# qo-100-gpsdo.net
KiCad netlist of a schematic drawn in EAGLE
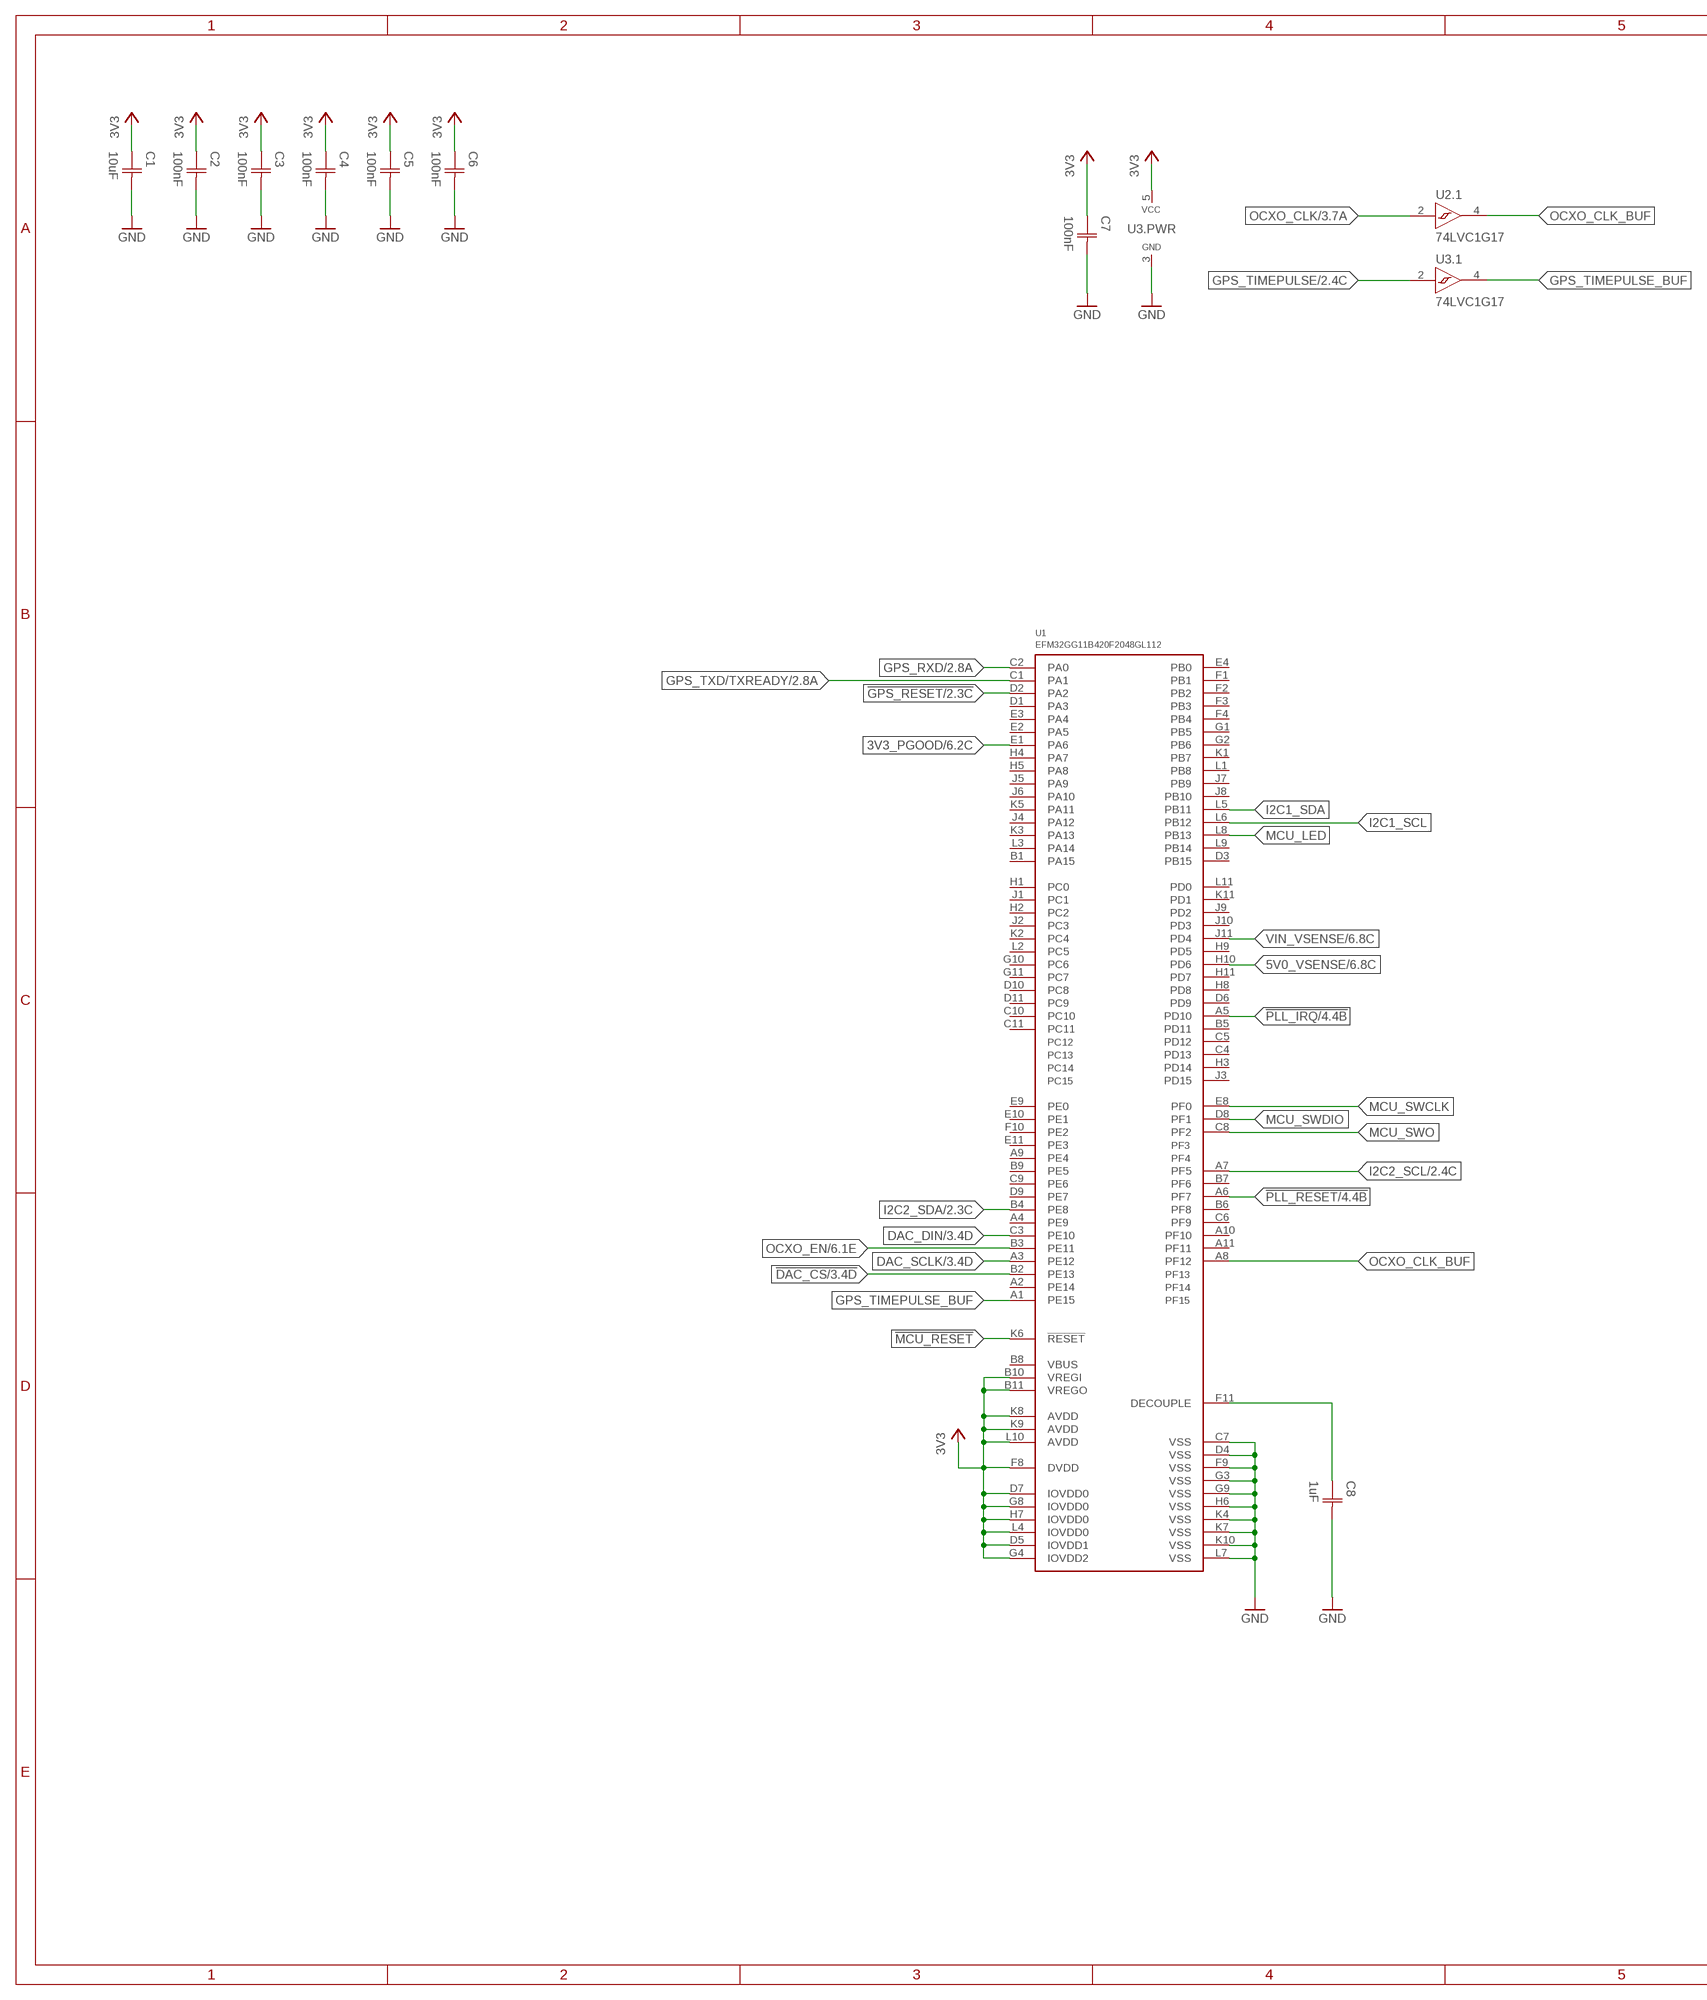
[diagram p0: schematic, sheet 1, part 1 of 2]
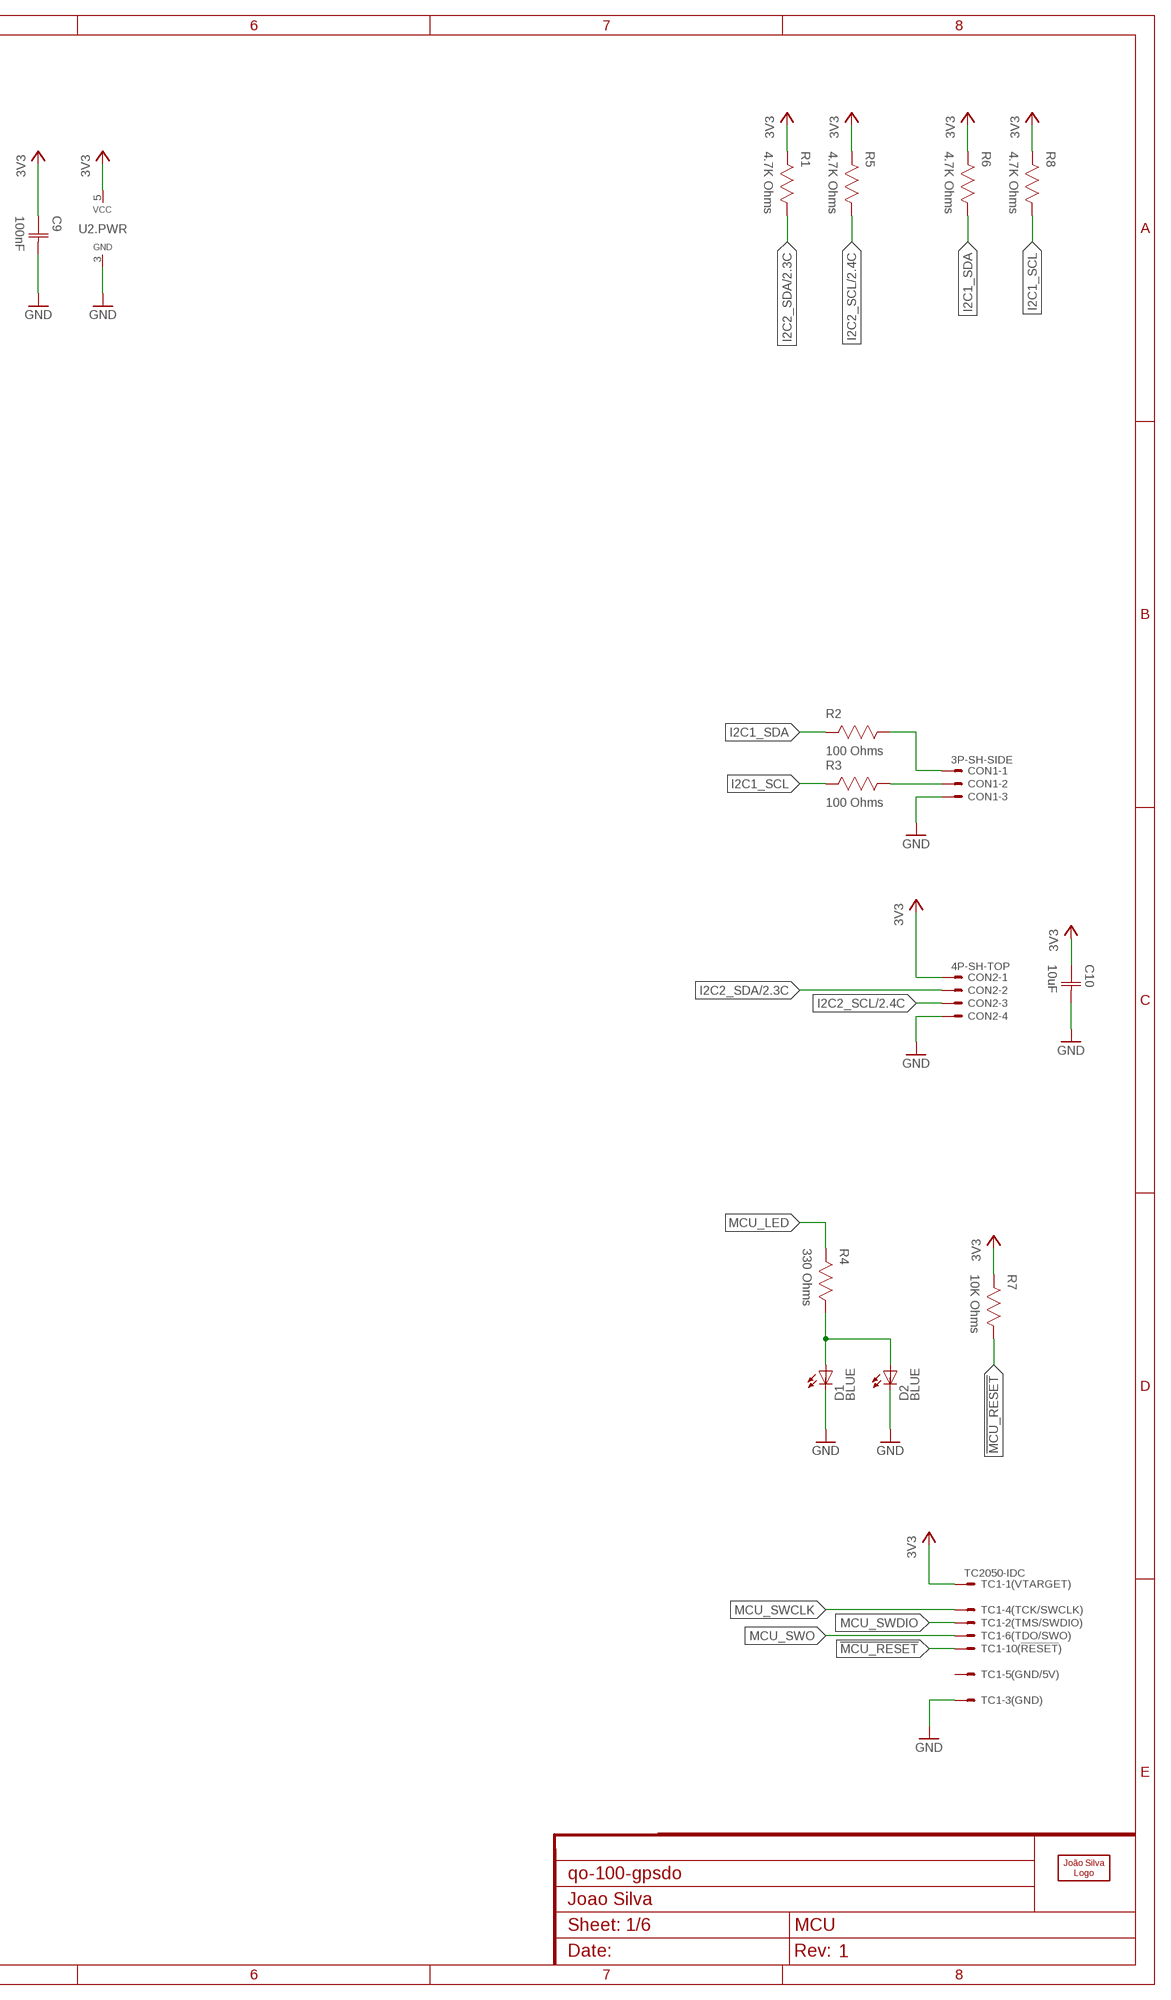
[diagram p1: schematic, sheet 1, part 2 of 2]
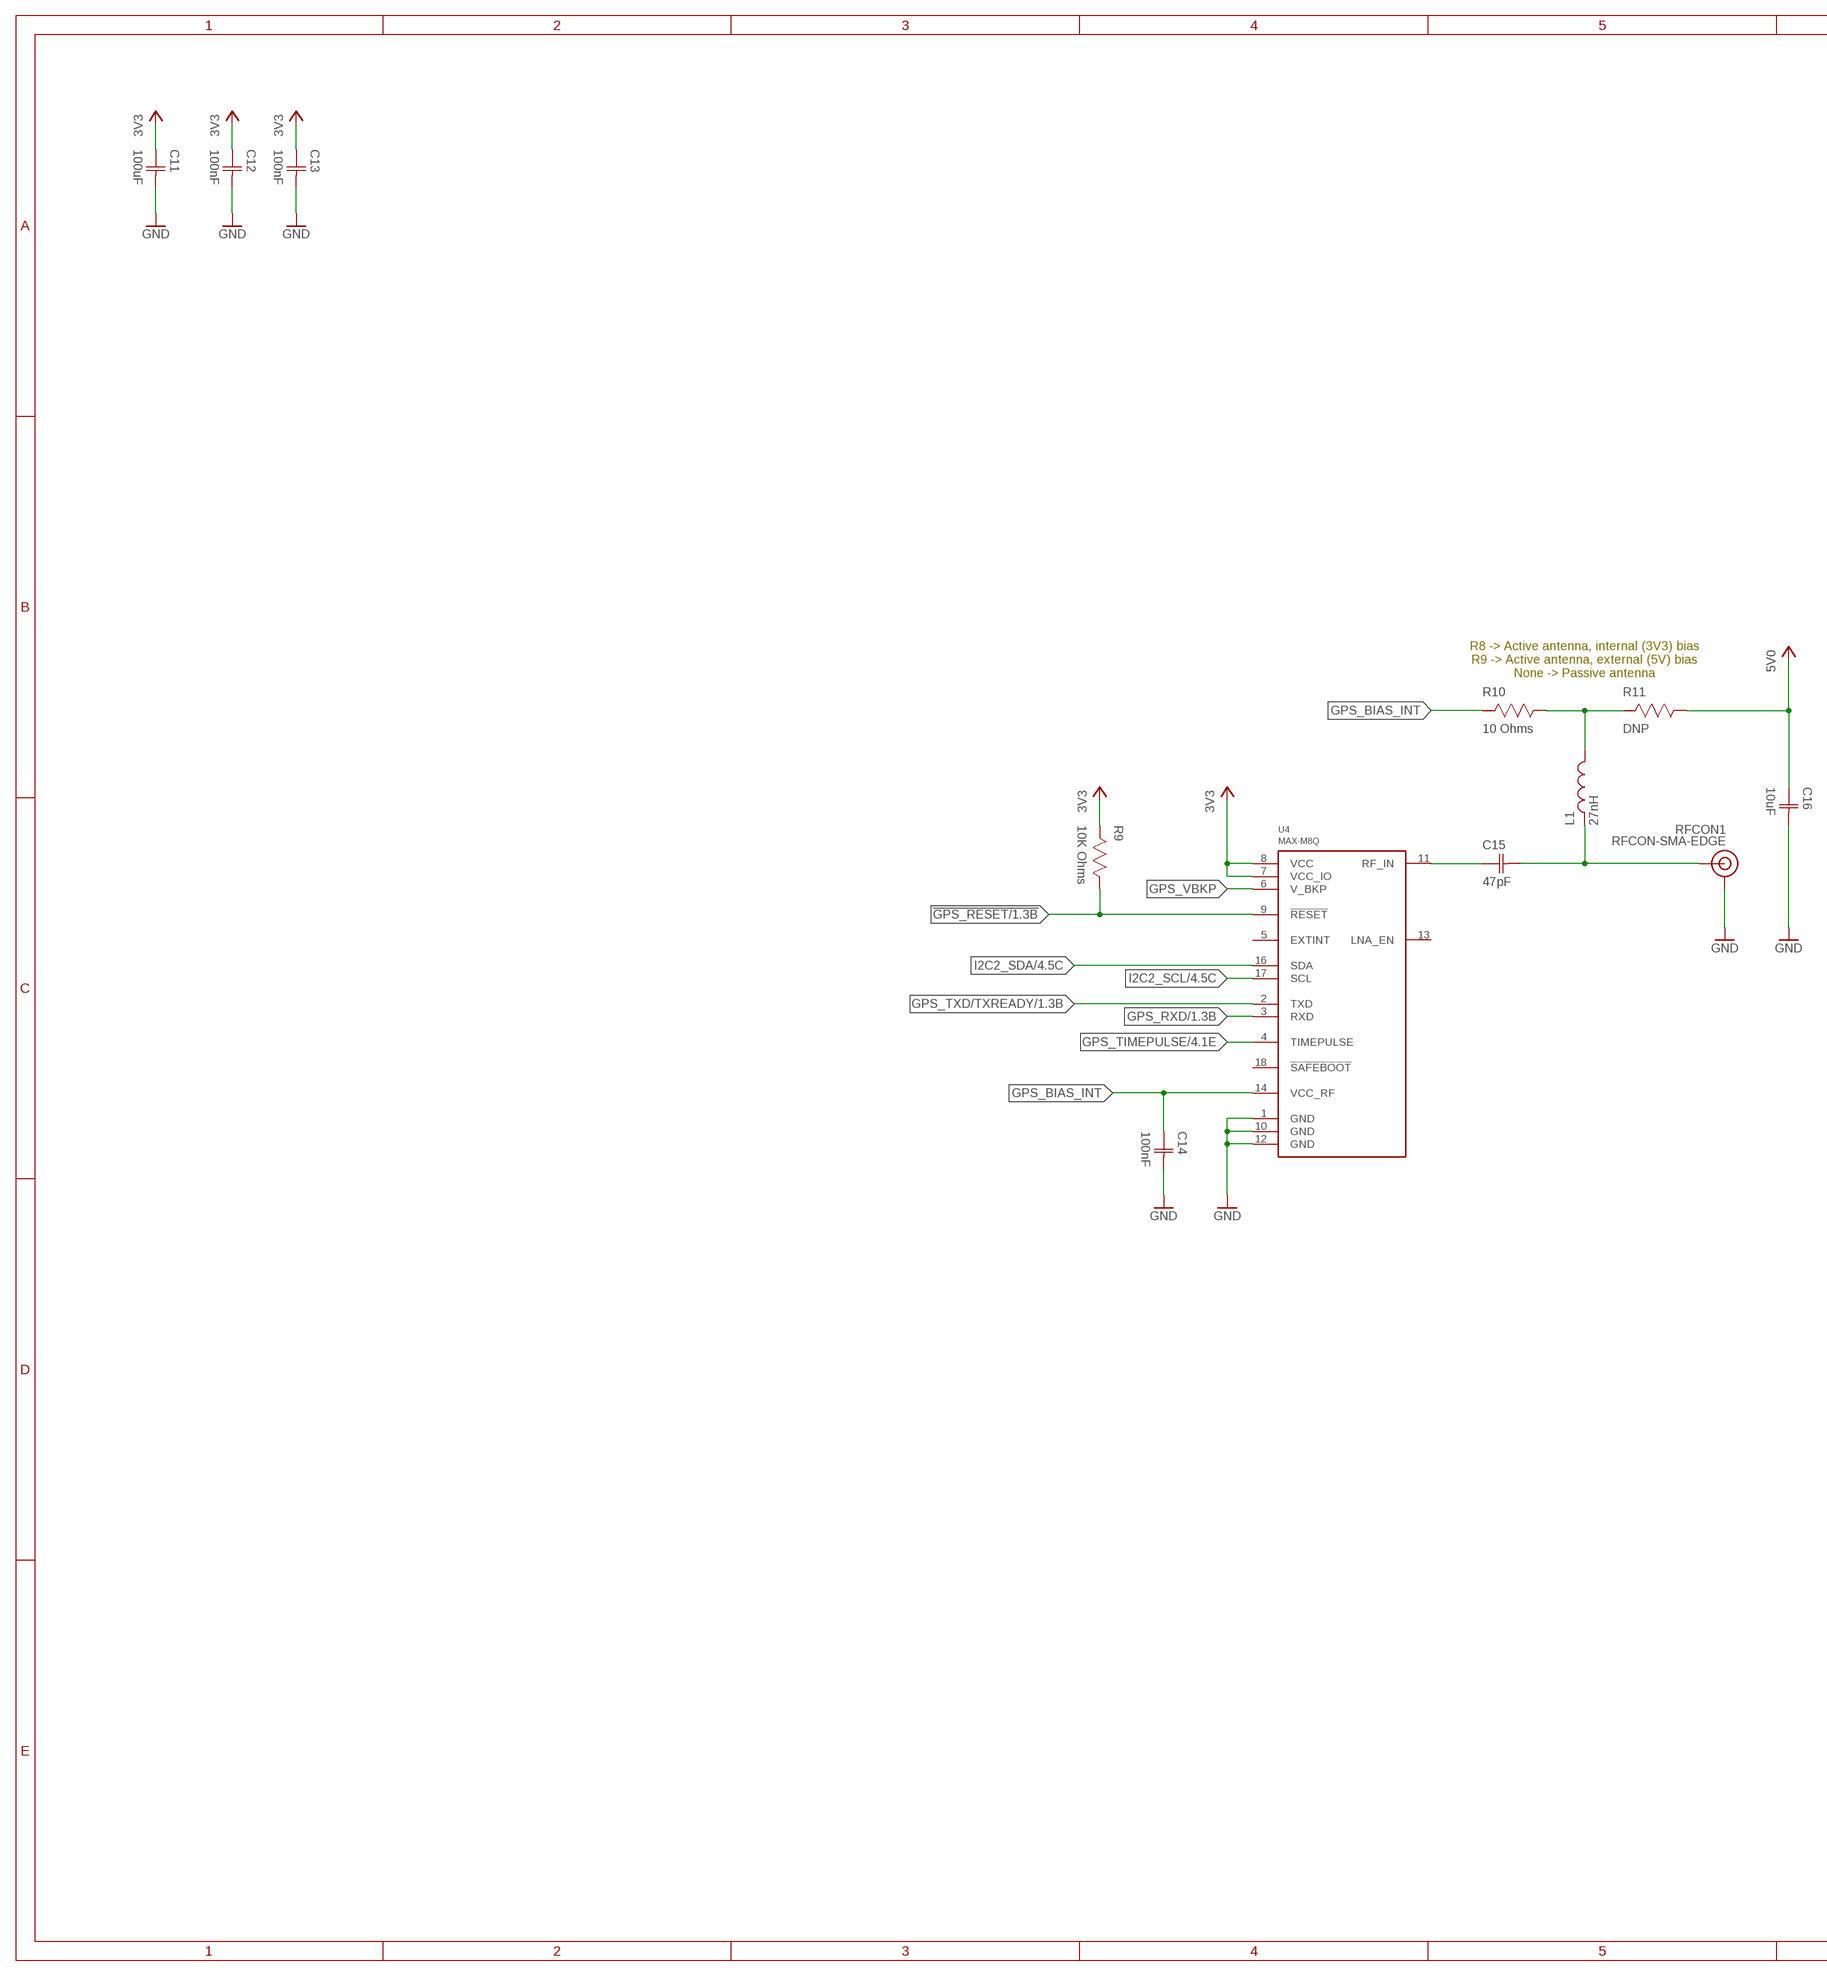
[diagram p2: schematic, sheet 2, part 1 of 2]
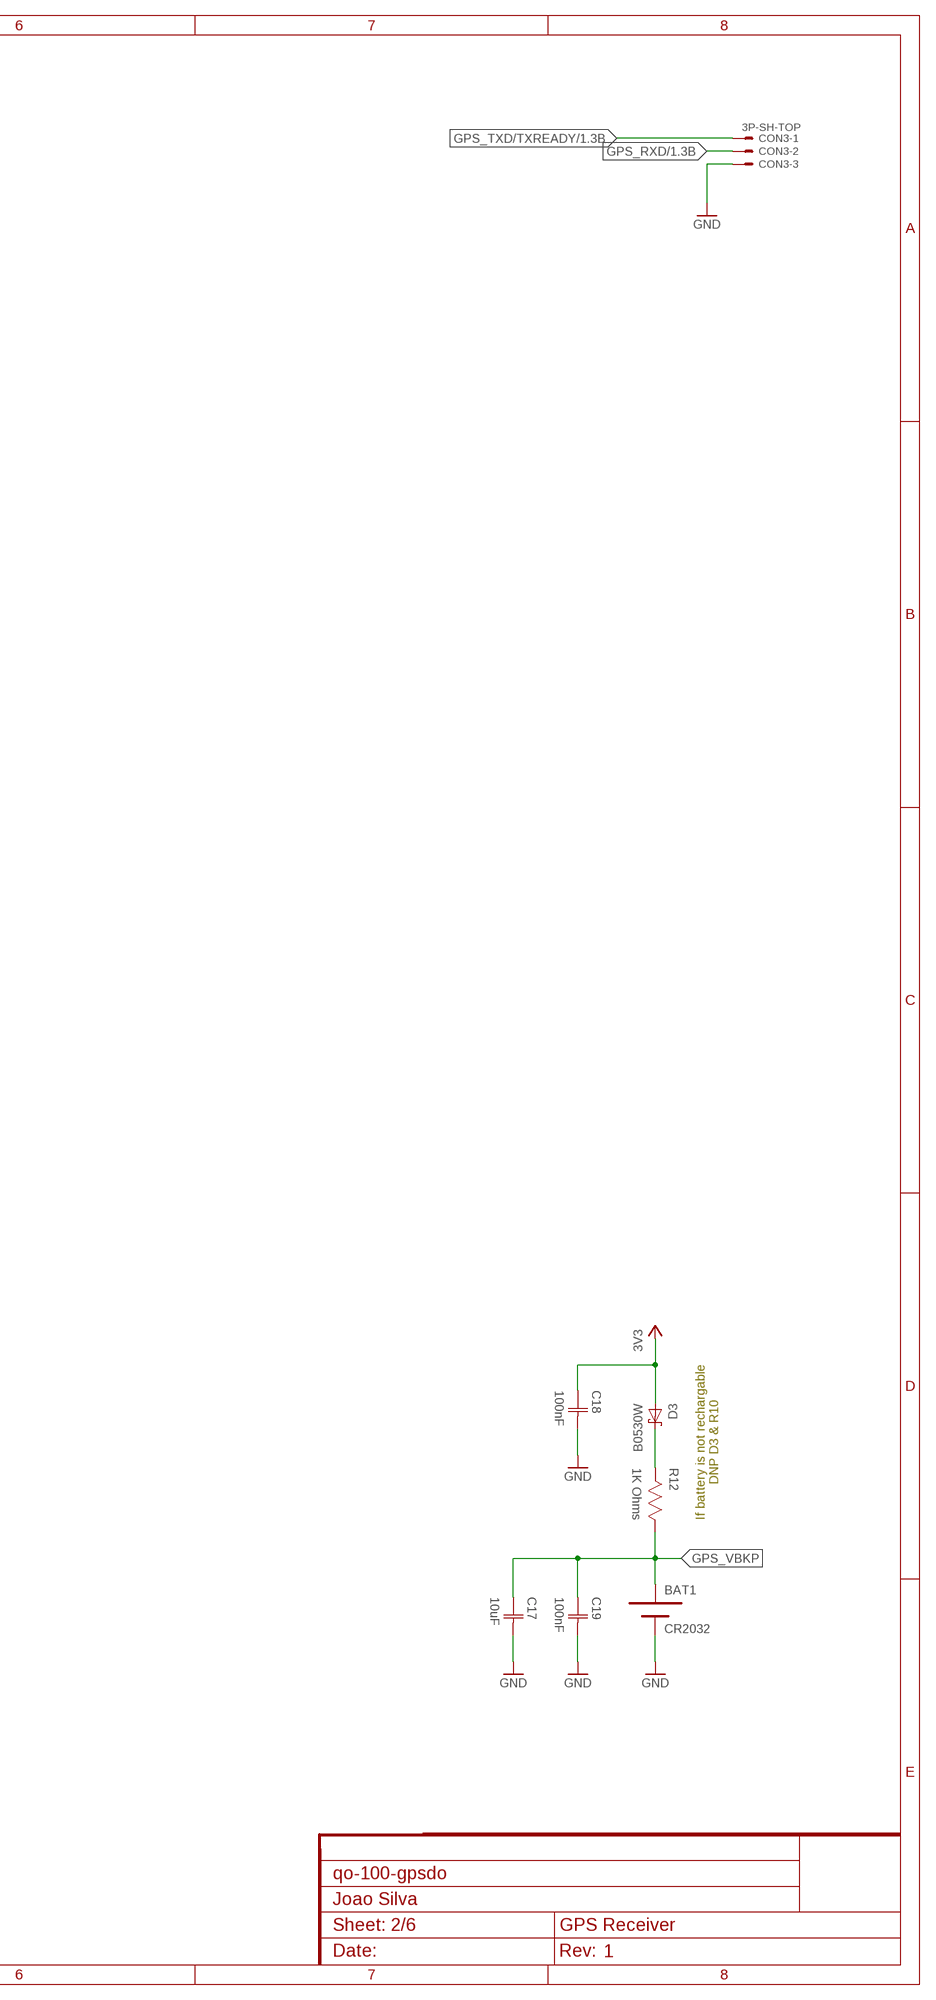
[diagram p3: schematic, sheet 2, part 2 of 2]
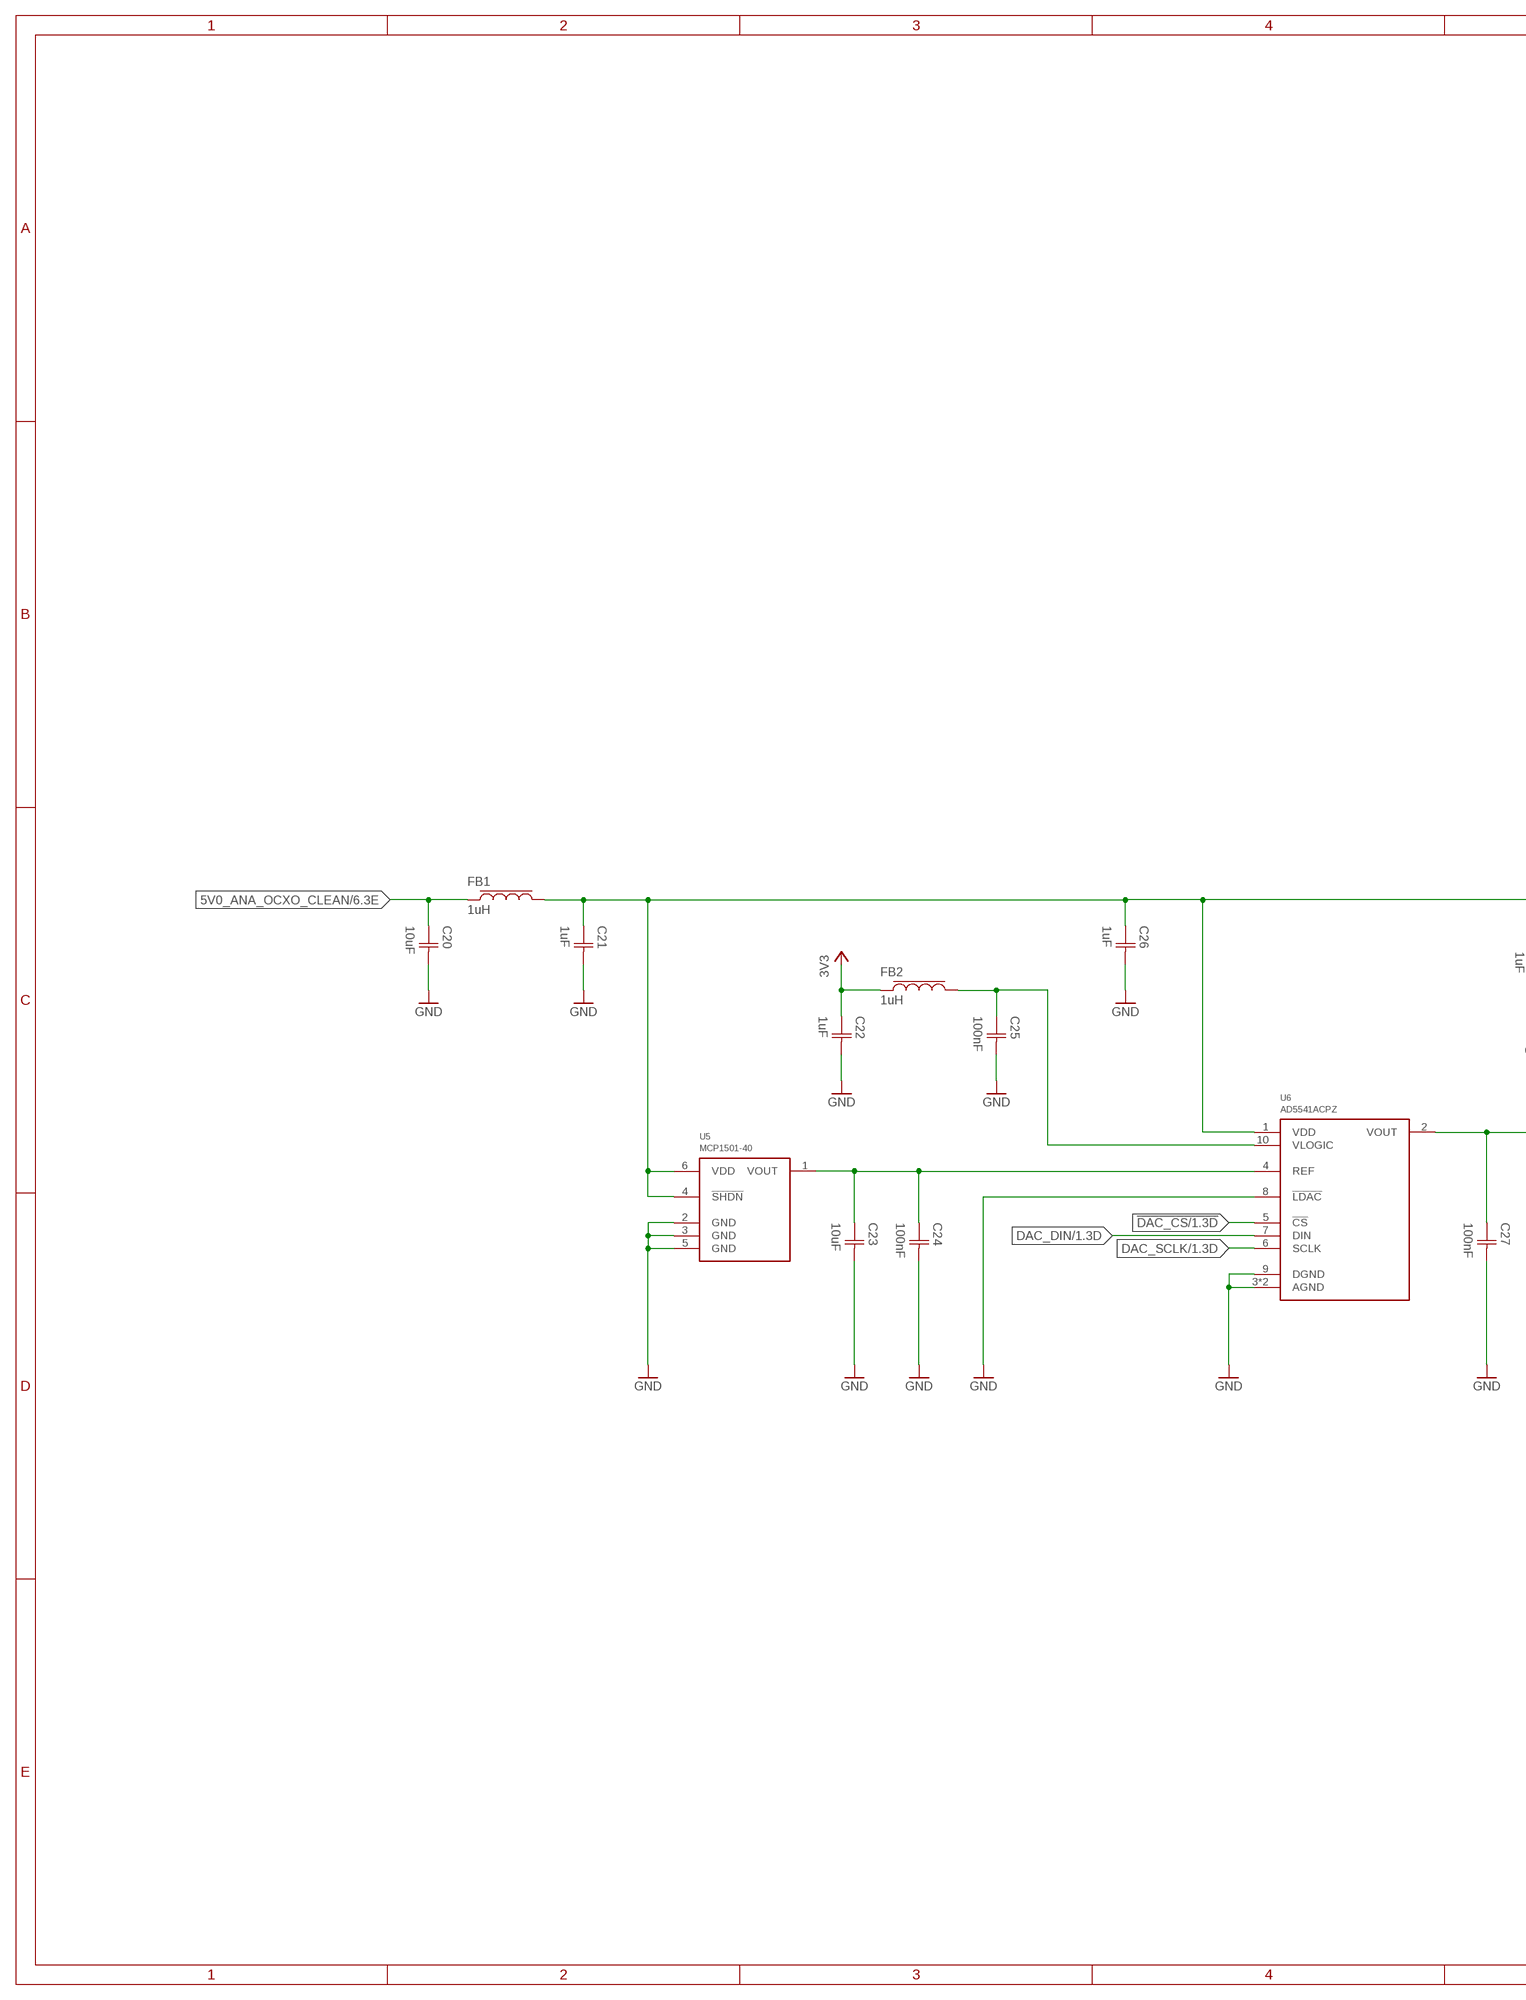
[diagram p4: schematic, sheet 3, part 1 of 2]
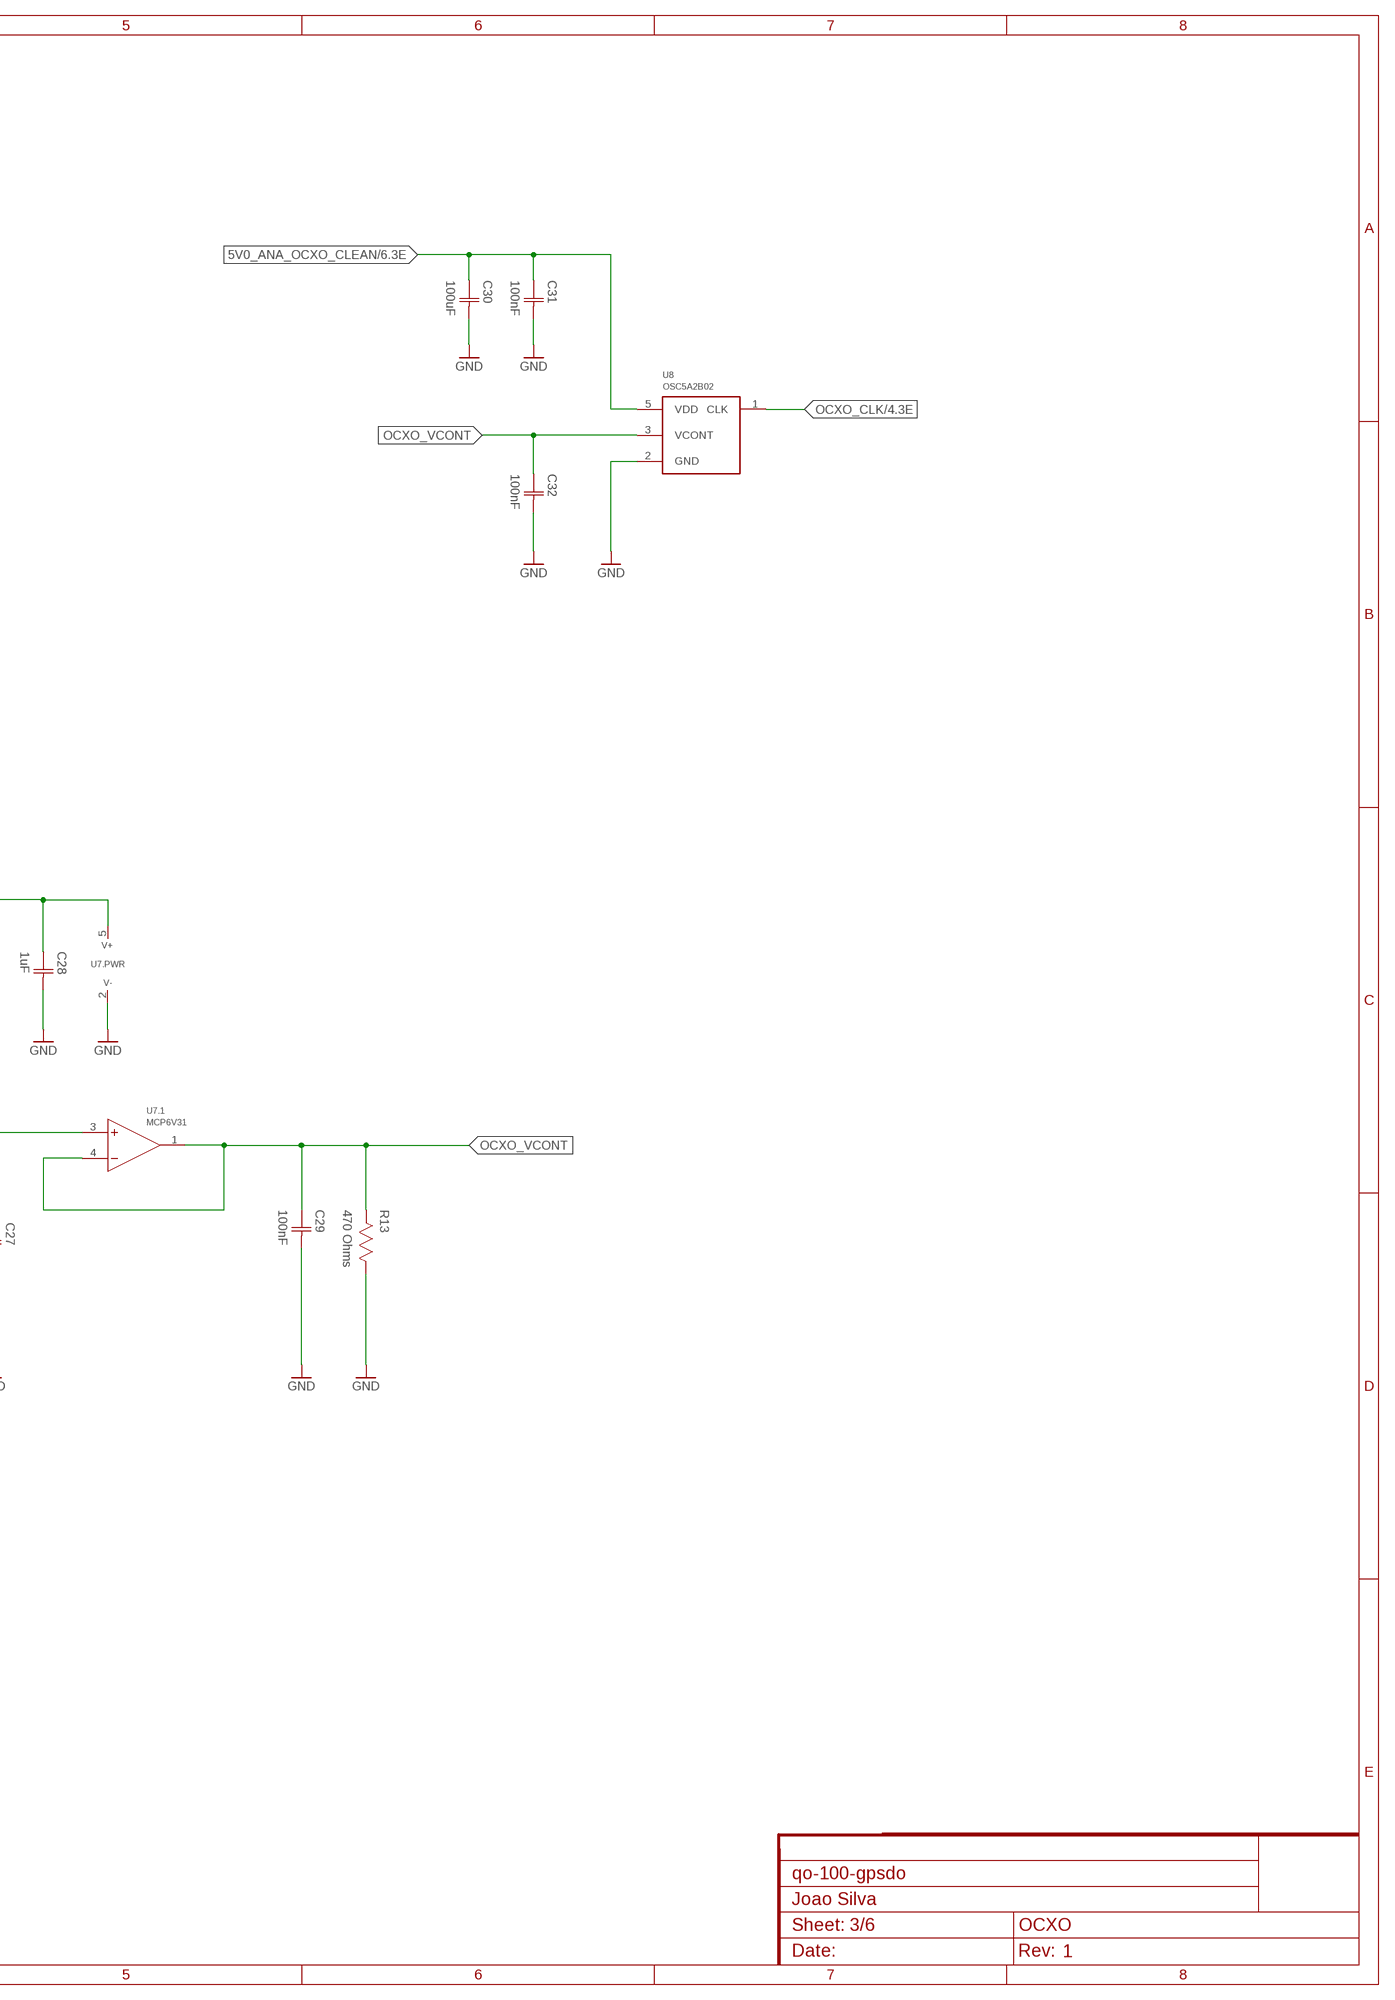
[diagram p5: schematic, sheet 3, part 2 of 2]
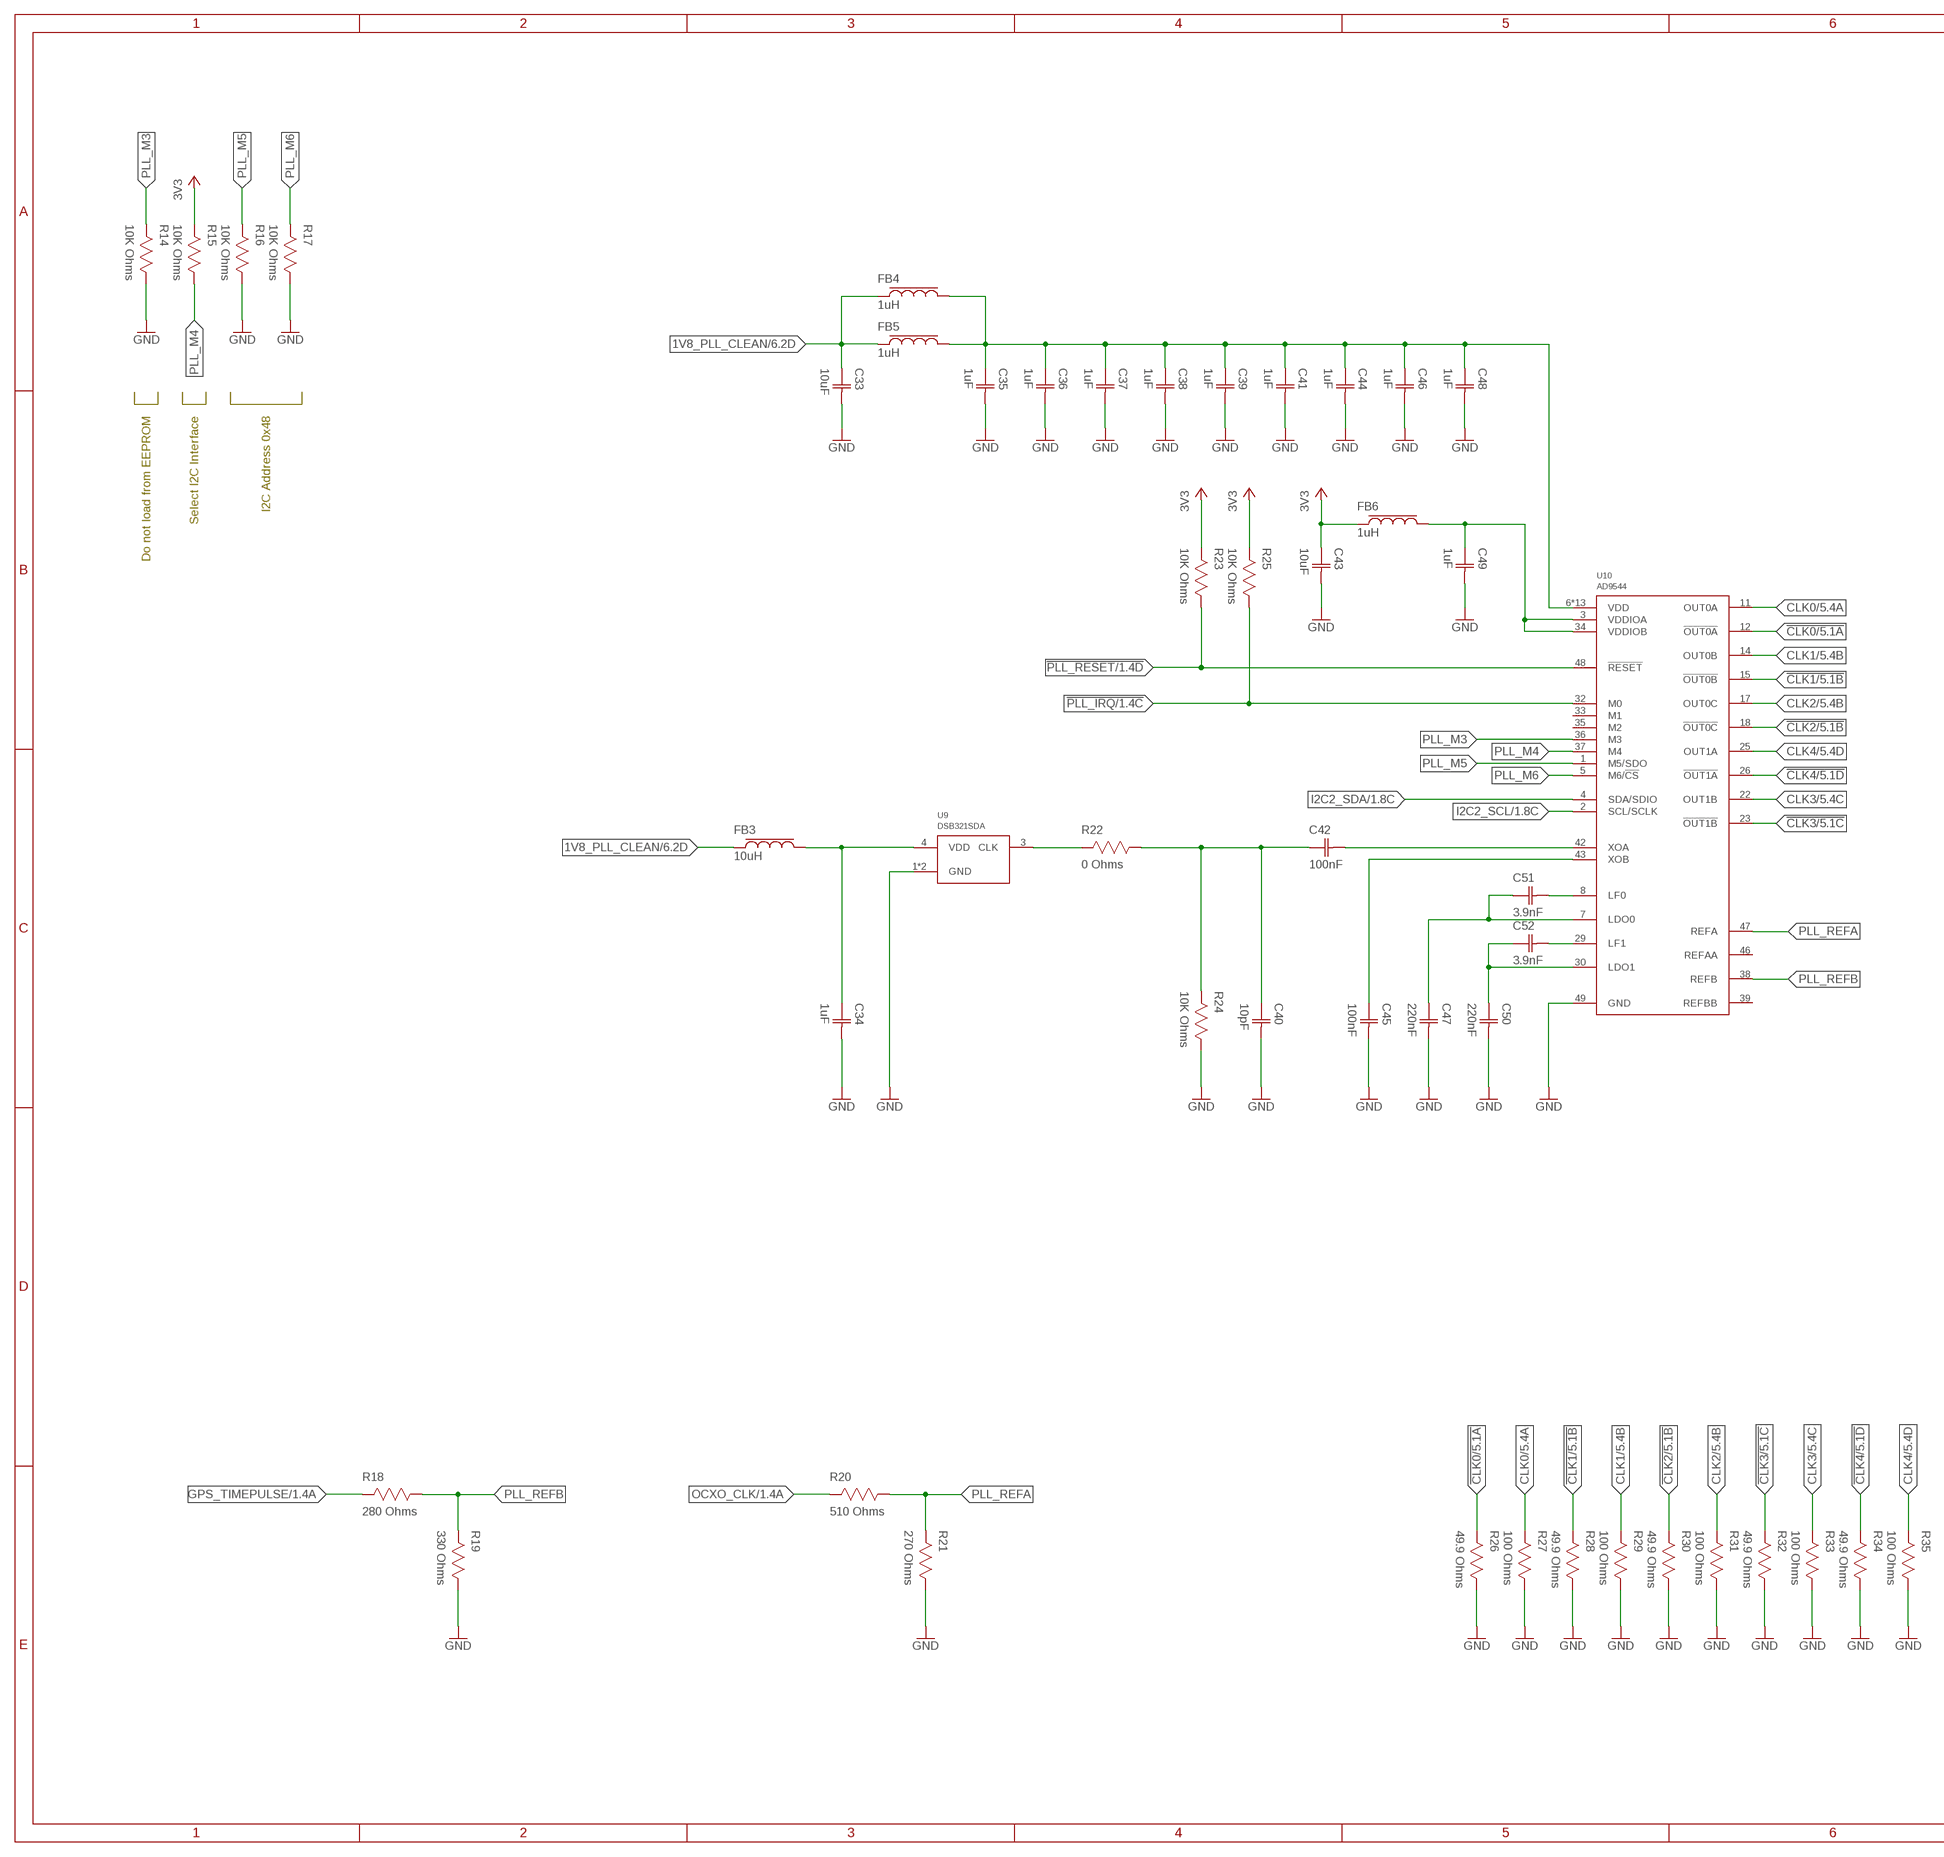
[diagram p6: schematic, sheet 4, part 1 of 2]
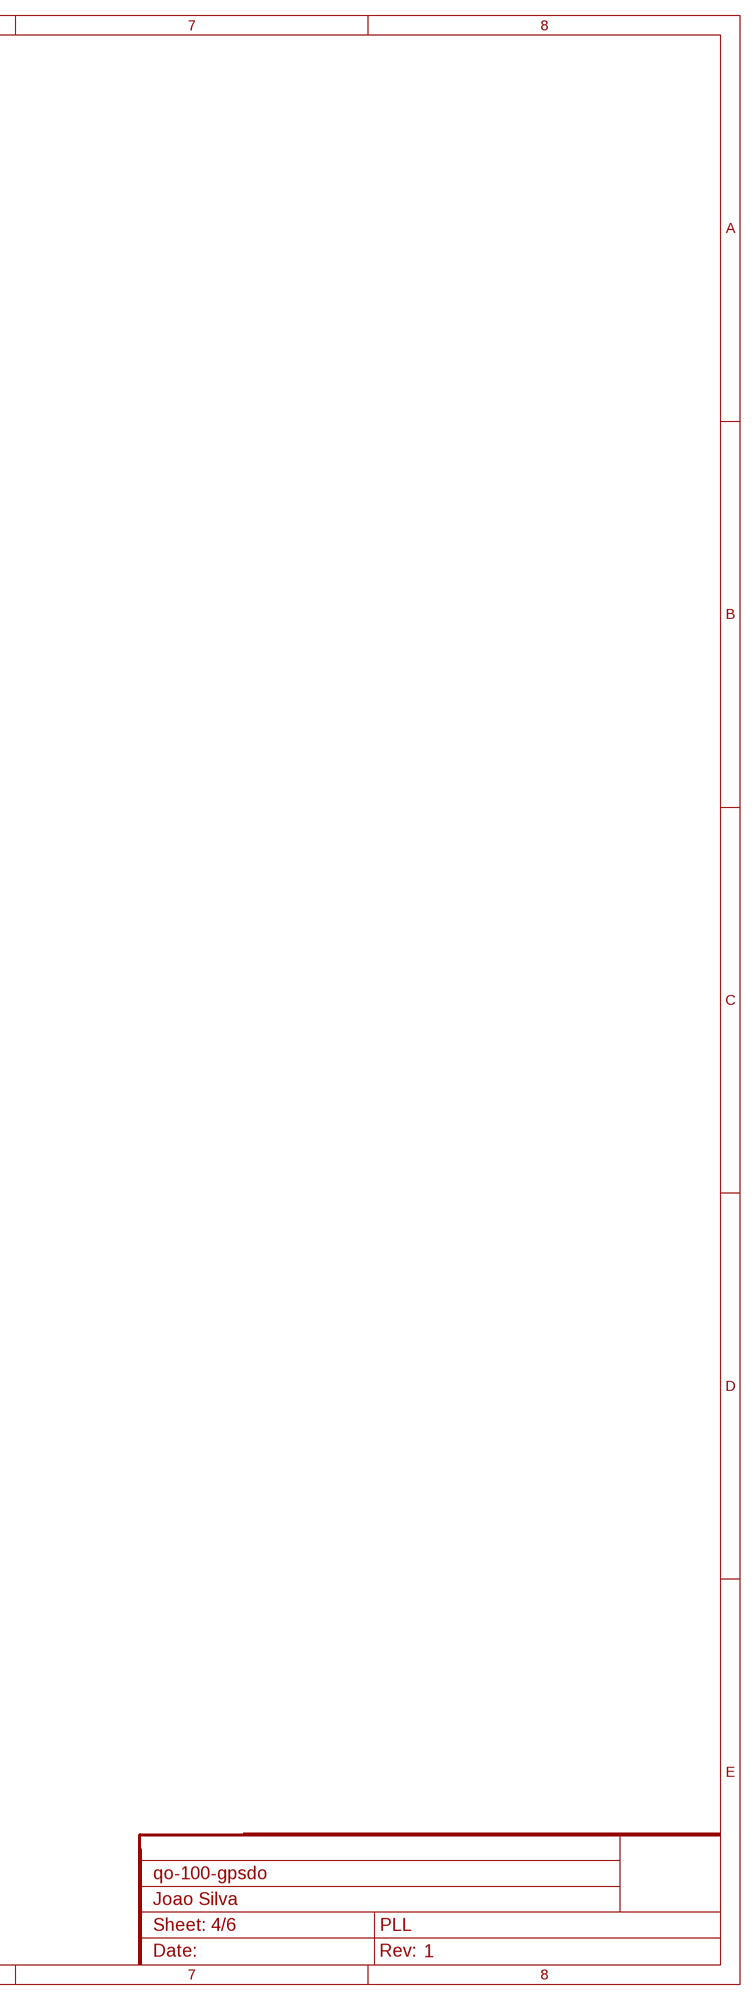
[diagram p7: schematic, sheet 4, part 2 of 2]
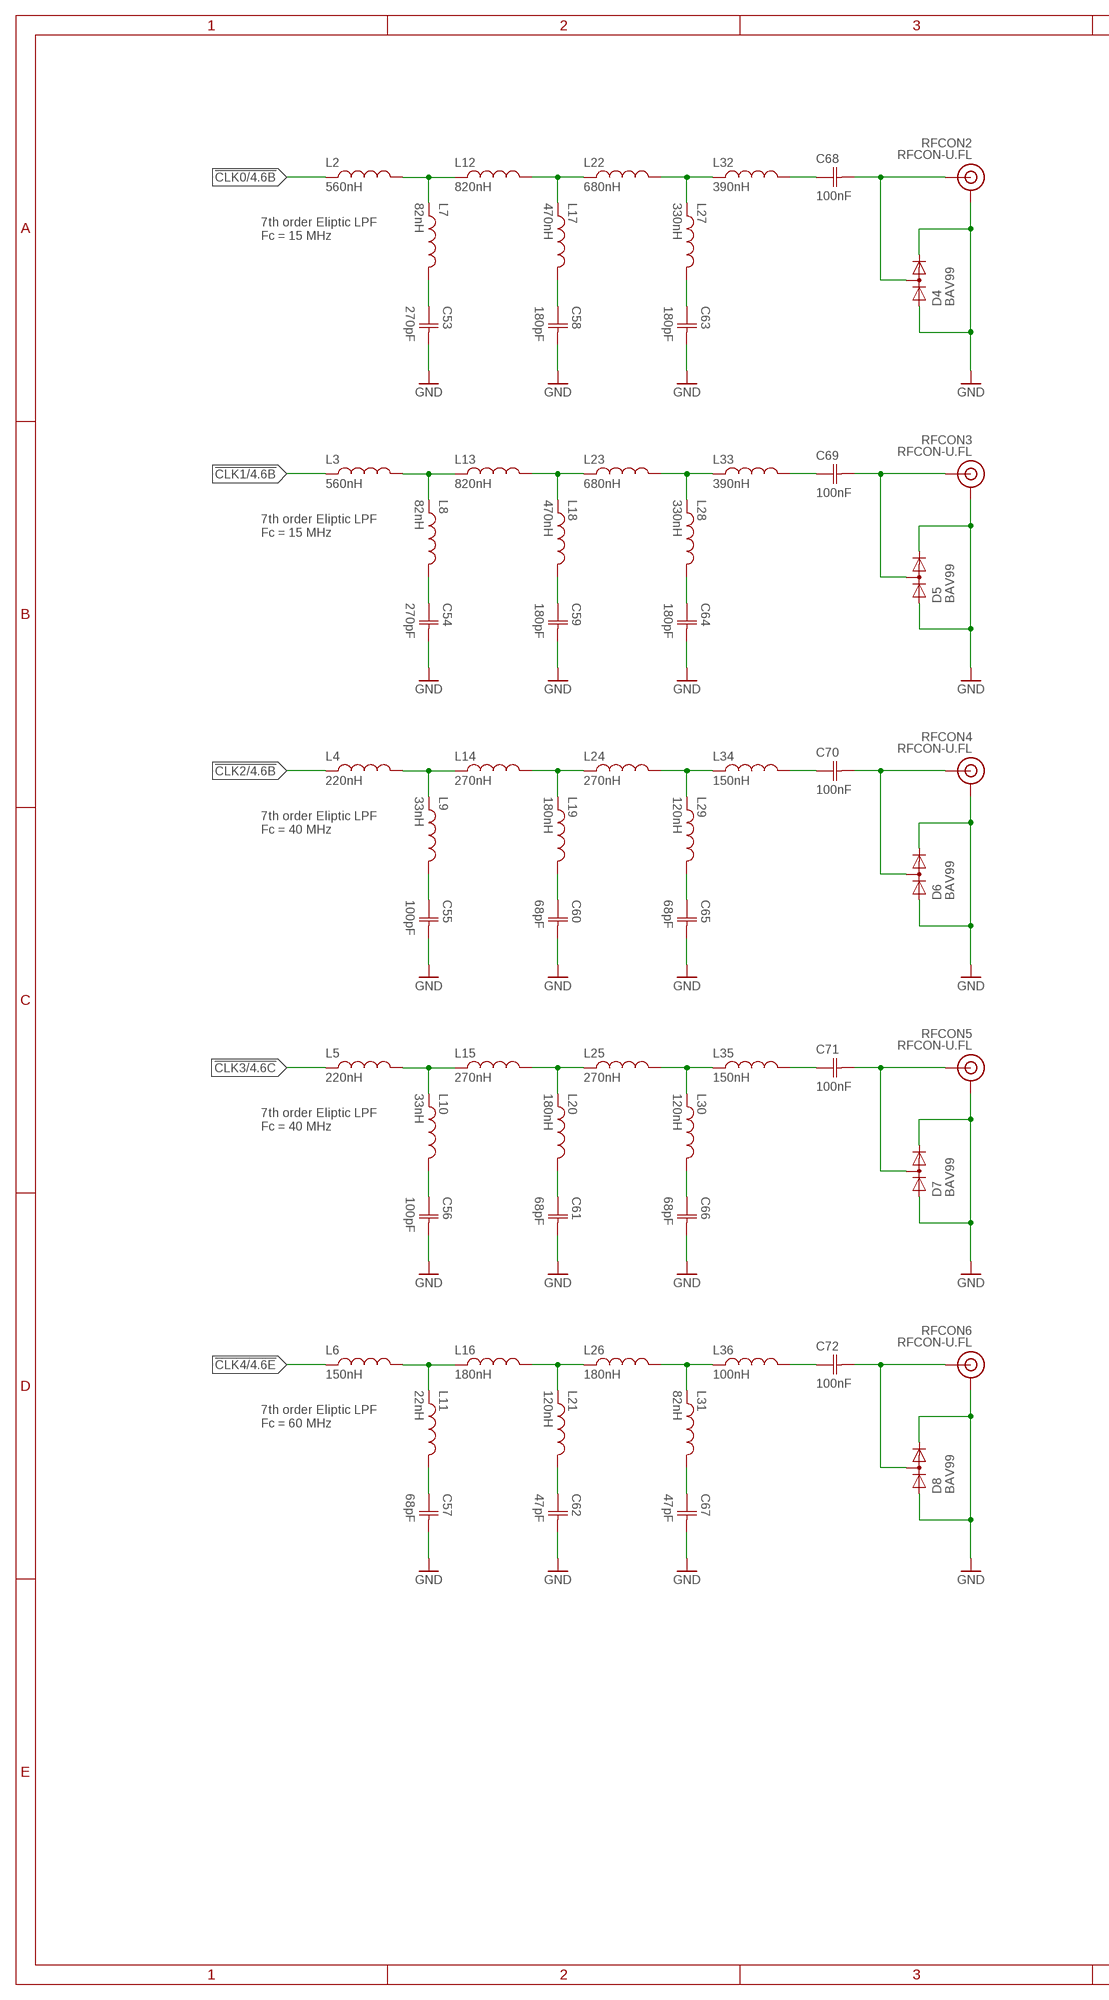
[diagram p8: schematic, sheet 5, part 1 of 2]
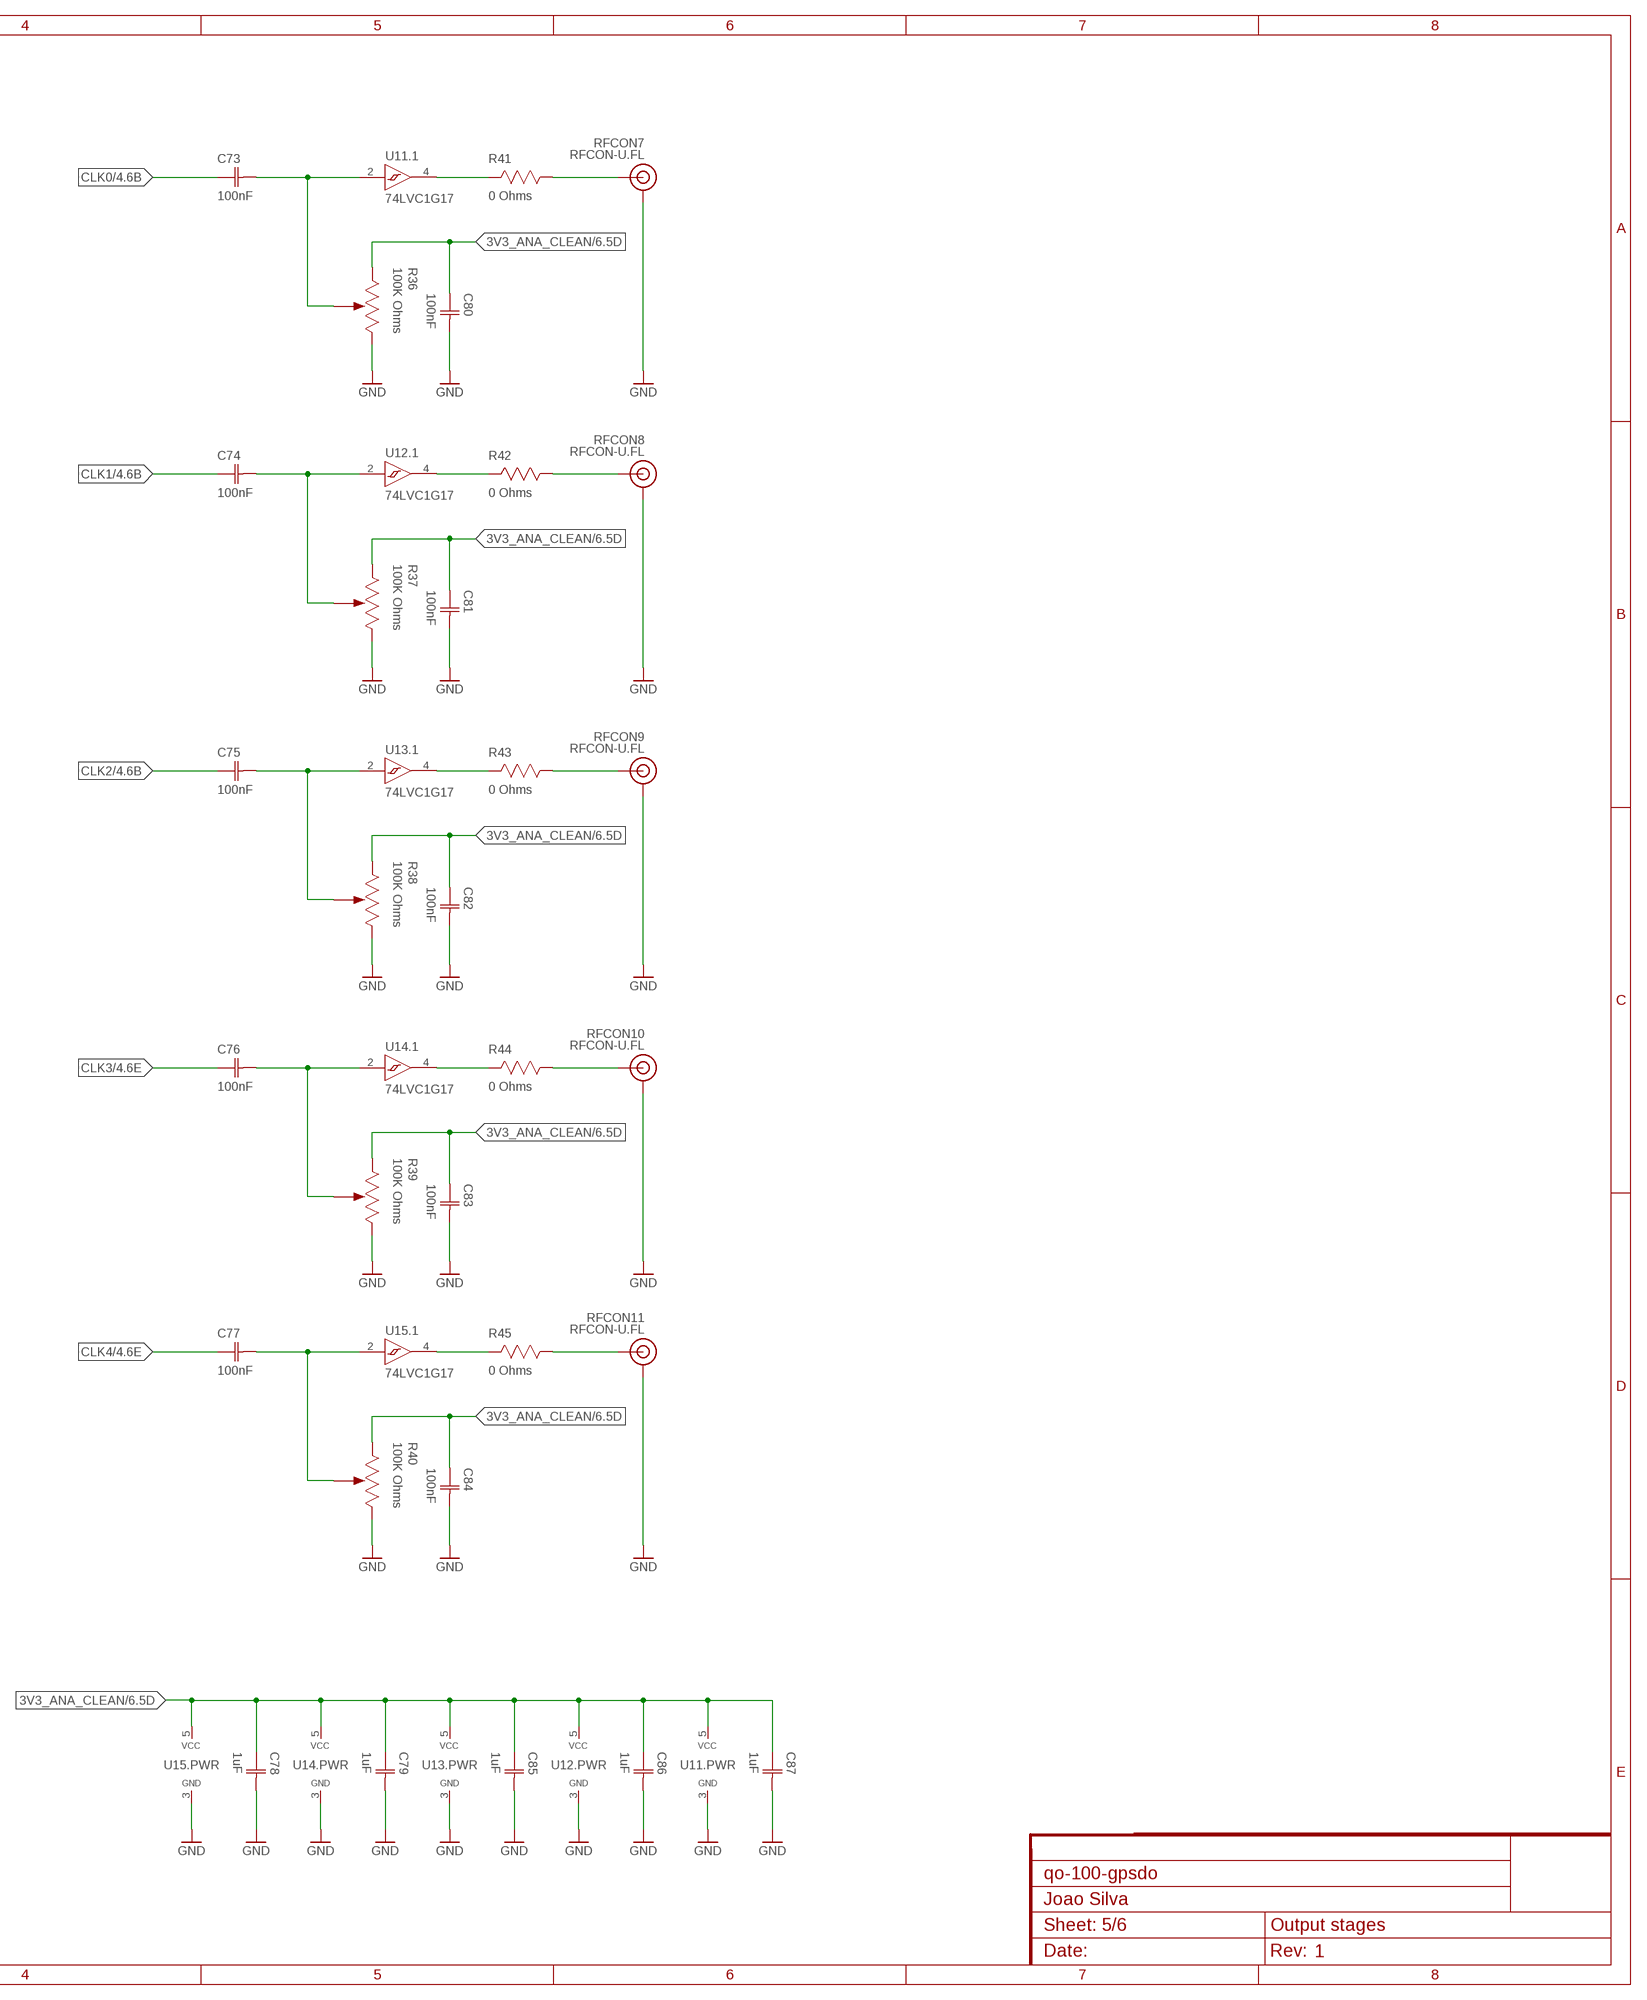
[diagram p9: schematic, sheet 5, part 2 of 2]
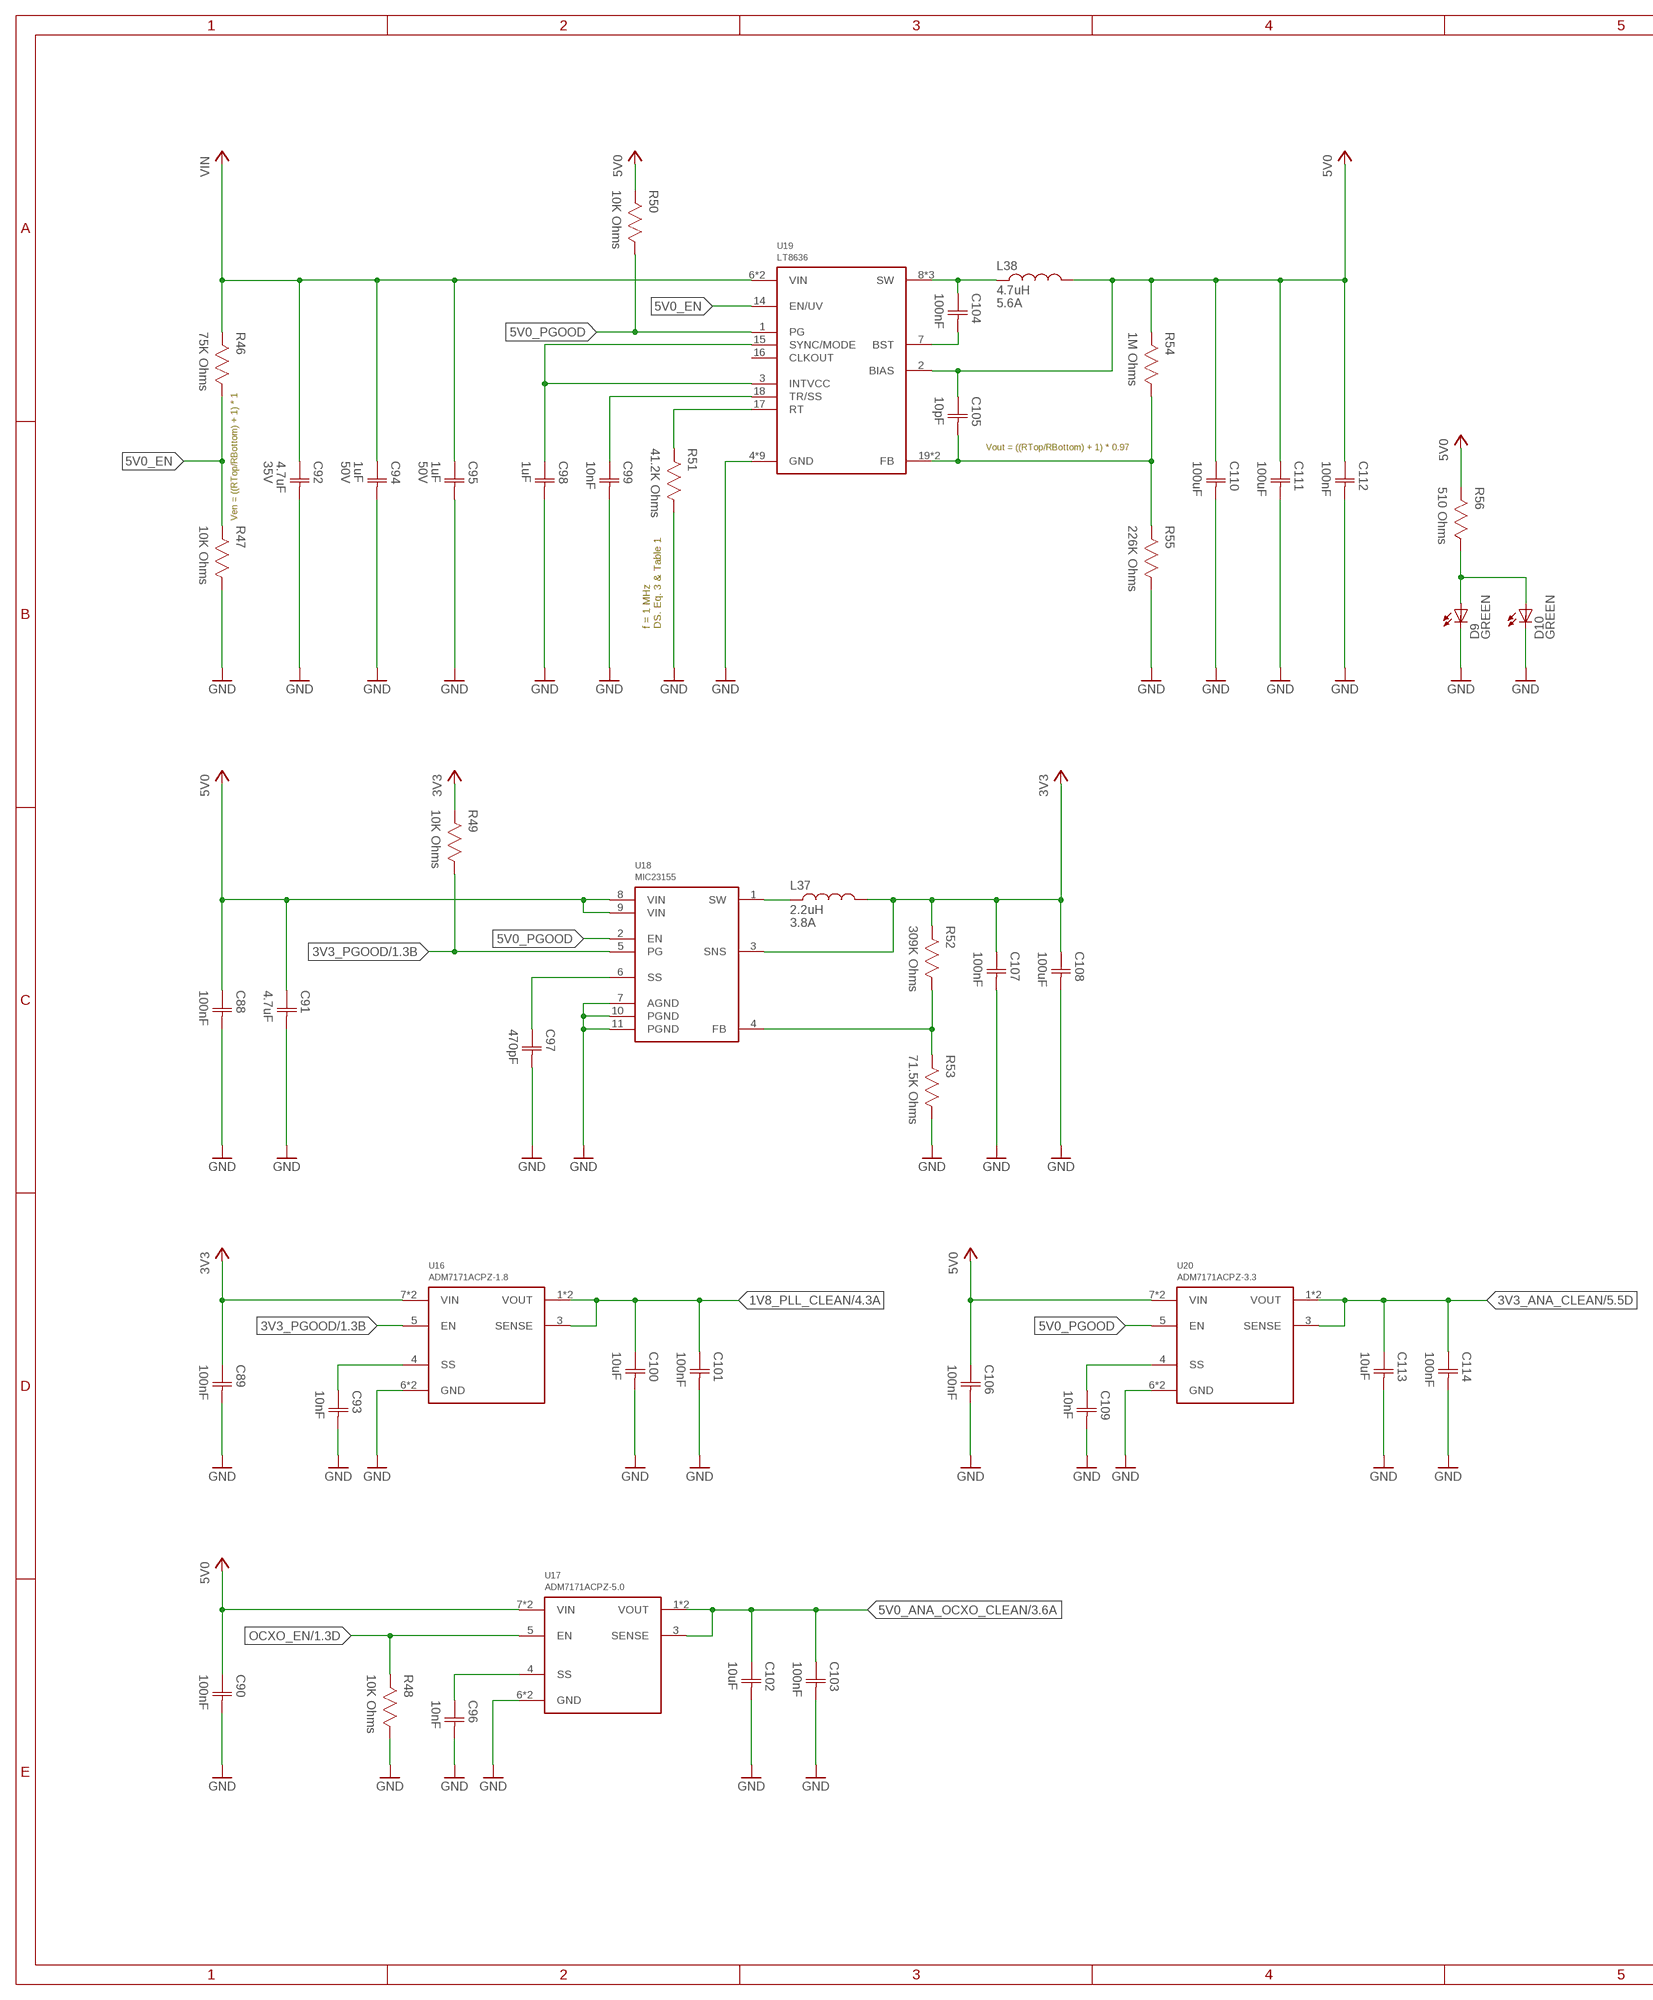
[diagram p10: schematic, sheet 6, part 1 of 2]
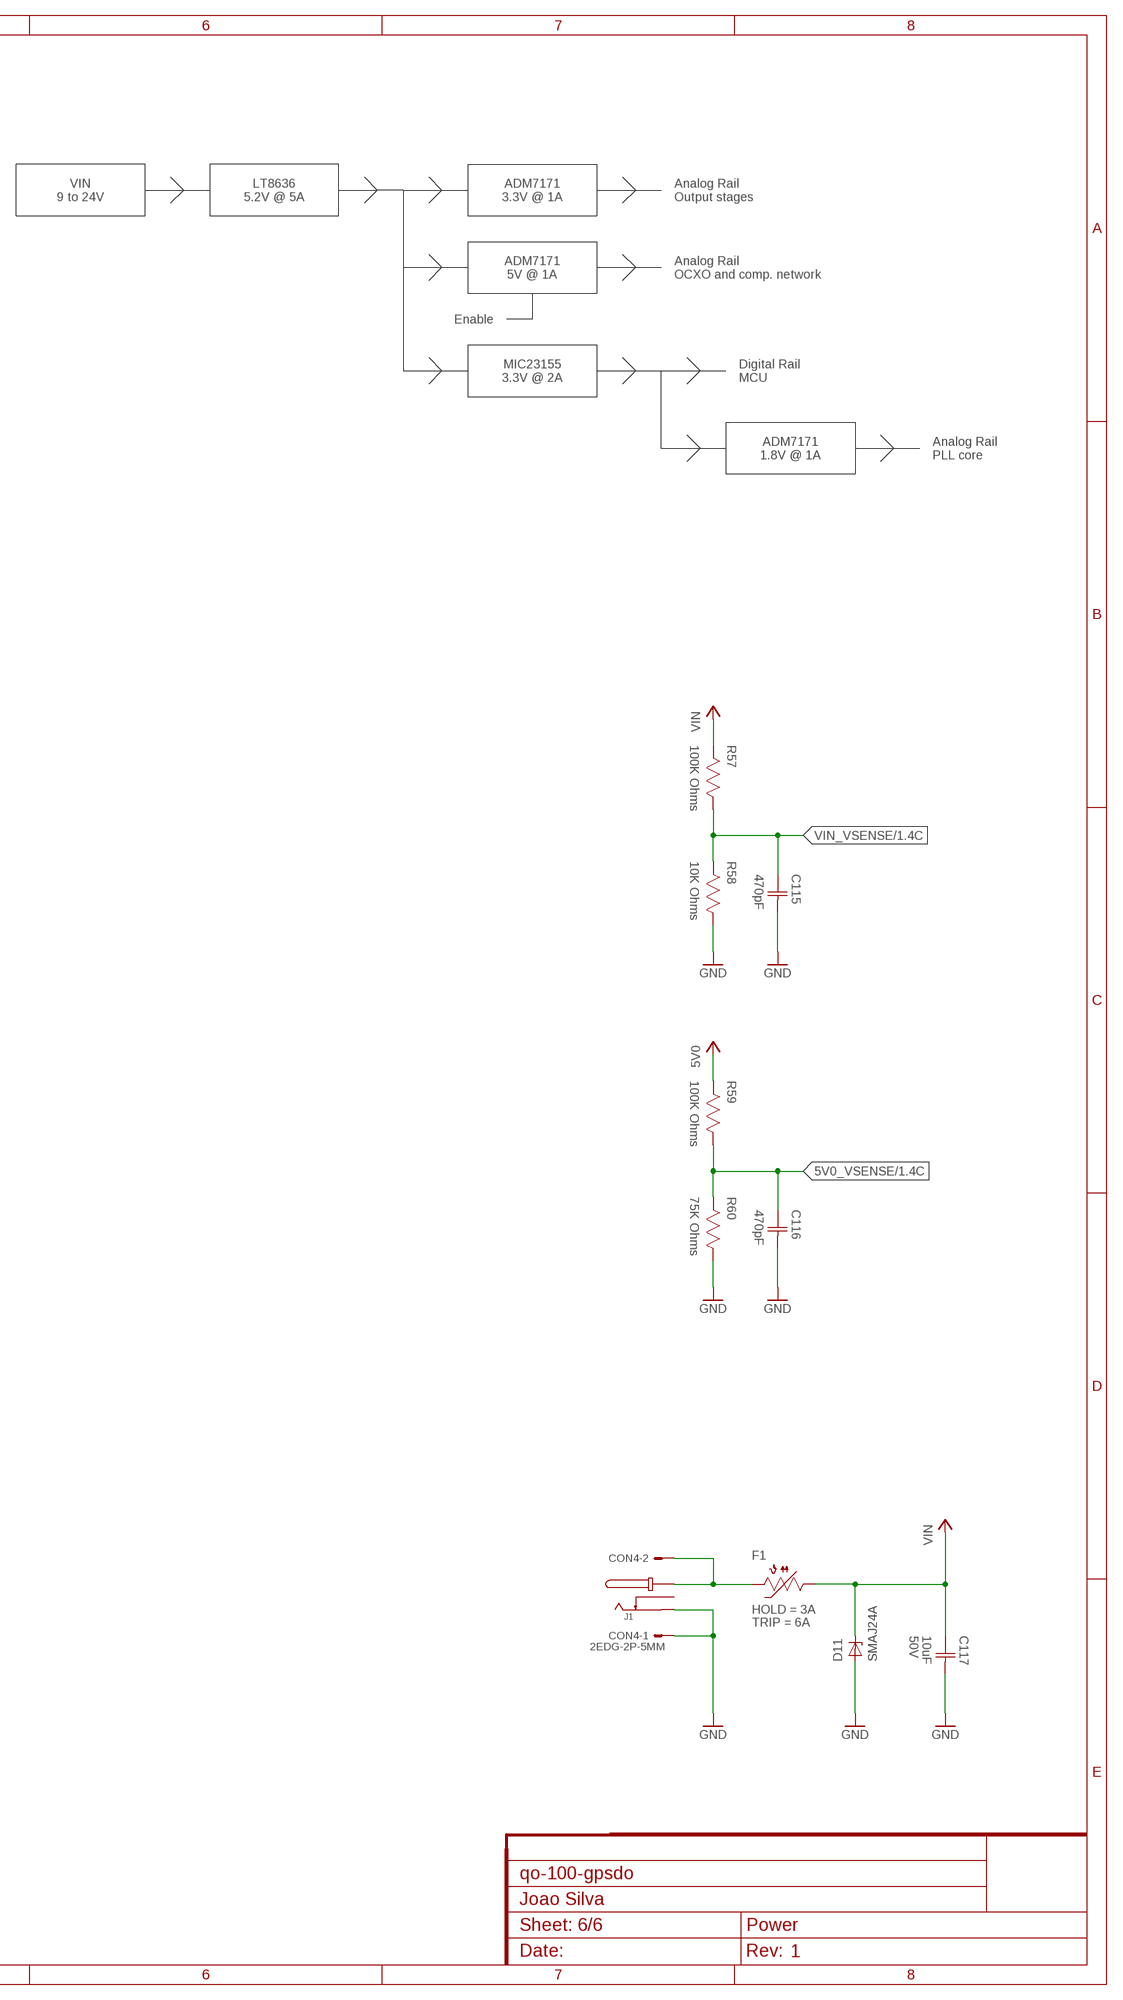
[diagram p11: schematic, sheet 6, part 2 of 2]

(export (version "E")
  (design (tool "Eeschema 10.0.6"))
  (components
    (comp (ref "C1")
      (value "10uF")
      (footprint "eagle-import:CAP0603")
      (libsource (lib "eagle-import") (part "CAPACITOR-0603"))
    )
    (comp (ref "C2")
      (value "100nF")
      (footprint "eagle-import:CAP0402")
      (libsource (lib "eagle-import") (part "CAPACITOR-0402"))
    )
    (comp (ref "C3")
      (value "100nF")
      (footprint "eagle-import:CAP0402")
      (libsource (lib "eagle-import") (part "CAPACITOR-0402"))
    )
    (comp (ref "C4")
      (value "100nF")
      (footprint "eagle-import:CAP0402")
      (libsource (lib "eagle-import") (part "CAPACITOR-0402"))
    )
    (comp (ref "C5")
      (value "100nF")
      (footprint "eagle-import:CAP0402")
      (libsource (lib "eagle-import") (part "CAPACITOR-0402"))
    )
    (comp (ref "C6")
      (value "100nF")
      (footprint "eagle-import:CAP0402")
      (libsource (lib "eagle-import") (part "CAPACITOR-0402"))
    )
    (comp (ref "C7")
      (value "100nF")
      (footprint "eagle-import:CAP0402")
      (libsource (lib "eagle-import") (part "CAPACITOR-0402"))
    )
    (comp (ref "C8")
      (value "1uF")
      (footprint "eagle-import:CAP0402")
      (libsource (lib "eagle-import") (part "CAPACITOR-0402"))
    )
    (comp (ref "C9")
      (value "100nF")
      (footprint "eagle-import:CAP0402")
      (libsource (lib "eagle-import") (part "CAPACITOR-0402"))
    )
    (comp (ref "C10")
      (value "10uF")
      (footprint "eagle-import:CAP0603")
      (libsource (lib "eagle-import") (part "CAPACITOR-0603"))
    )
    (comp (ref "CON1")
      (value "3P-SH-SIDE")
      (footprint "eagle-import:SH-03-SIDE")
      (libsource (lib "eagle-import") (part "3P-SH-SIDE"))
    )
    (comp (ref "CON2")
      (value "4P-SH-TOP")
      (footprint "eagle-import:SH-04-TOP")
      (libsource (lib "eagle-import") (part "4P-SH-TOP"))
    )
    (comp (ref "D1")
      (value "LED0603")
      (footprint "eagle-import:0603")
      (fields (field (name "COLOR") "BLUE"))
      (libsource (lib "eagle-import") (part "LED0603"))
    )
    (comp (ref "D2")
      (value "LEDTH3MM")
      (footprint "eagle-import:LED_3MM")
      (fields (field (name "COLOR") "BLUE"))
      (libsource (lib "eagle-import") (part "LEDTH3MM"))
    )
    (comp (ref "LOGO1")
      (value "JS-5MM")
      (footprint "eagle-import:JS_5MM")
      (libsource (lib "eagle-import") (part "JS-5MM"))
    )
    (comp (ref "R1")
      (value "4.7K Ohms")
      (footprint "eagle-import:RES0402")
      (libsource (lib "eagle-import") (part "RESISTOR-0402"))
    )
    (comp (ref "R2")
      (value "100 Ohms")
      (footprint "eagle-import:RES0402")
      (libsource (lib "eagle-import") (part "RESISTOR-0402"))
    )
    (comp (ref "R3")
      (value "100 Ohms")
      (footprint "eagle-import:RES0402")
      (libsource (lib "eagle-import") (part "RESISTOR-0402"))
    )
    (comp (ref "R4")
      (value "330 Ohms")
      (footprint "eagle-import:RES0402")
      (libsource (lib "eagle-import") (part "RESISTOR-0402"))
    )
    (comp (ref "R5")
      (value "4.7K Ohms")
      (footprint "eagle-import:RES0402")
      (libsource (lib "eagle-import") (part "RESISTOR-0402"))
    )
    (comp (ref "R6")
      (value "4.7K Ohms")
      (footprint "eagle-import:RES0402")
      (libsource (lib "eagle-import") (part "RESISTOR-0402"))
    )
    (comp (ref "R7")
      (value "10K Ohms")
      (footprint "eagle-import:RES0402")
      (libsource (lib "eagle-import") (part "RESISTOR-0402"))
    )
    (comp (ref "R8")
      (value "4.7K Ohms")
      (footprint "eagle-import:RES0402")
      (libsource (lib "eagle-import") (part "RESISTOR-0402"))
    )
    (comp (ref "TC1")
      (value "TC2050-IDC")
      (footprint "eagle-import:TC2050-IDC")
      (libsource (lib "eagle-import") (part "TC2050-IDC"))
    )
    (comp (ref "U1")
      (value "EFM32GG11B420F2048GL112")
      (footprint "eagle-import:BGA112")
      (libsource (lib "eagle-import") (part "EFM32GG11B4L11220F2048G"))
    )
    (comp (ref "U2")
      (value "74LVC1G17")
      (footprint "eagle-import:SC70-5")
      (libsource (lib "eagle-import") (part "74LVC1G17"))
    )
    (comp (ref "U3")
      (value "74LVC1G17")
      (footprint "eagle-import:SC70-5")
      (libsource (lib "eagle-import") (part "74LVC1G17"))
    )
    (comp (ref "C33")
      (value "10uF")
      (footprint "eagle-import:CAP0603")
      (libsource (lib "eagle-import") (part "CAPACITOR-0603"))
    )
    (comp (ref "C34")
      (value "1uF")
      (footprint "eagle-import:CAP0402")
      (libsource (lib "eagle-import") (part "CAPACITOR-0402"))
    )
    (comp (ref "C35")
      (value "1uF")
      (footprint "eagle-import:CAP0402")
      (libsource (lib "eagle-import") (part "CAPACITOR-0402"))
    )
    (comp (ref "C36")
      (value "1uF")
      (footprint "eagle-import:CAP0402")
      (libsource (lib "eagle-import") (part "CAPACITOR-0402"))
    )
    (comp (ref "C37")
      (value "1uF")
      (footprint "eagle-import:CAP0402")
      (libsource (lib "eagle-import") (part "CAPACITOR-0402"))
    )
    (comp (ref "C38")
      (value "1uF")
      (footprint "eagle-import:CAP0402")
      (libsource (lib "eagle-import") (part "CAPACITOR-0402"))
    )
    (comp (ref "C39")
      (value "1uF")
      (footprint "eagle-import:CAP0402")
      (libsource (lib "eagle-import") (part "CAPACITOR-0402"))
    )
    (comp (ref "C40")
      (value "10pF")
      (footprint "eagle-import:CAP0402")
      (libsource (lib "eagle-import") (part "CAPACITOR-0402"))
    )
    (comp (ref "C41")
      (value "1uF")
      (footprint "eagle-import:CAP0402")
      (libsource (lib "eagle-import") (part "CAPACITOR-0402"))
    )
    (comp (ref "C42")
      (value "100nF")
      (footprint "eagle-import:CAP0402")
      (libsource (lib "eagle-import") (part "CAPACITOR-0402"))
    )
    (comp (ref "C43")
      (value "10uF")
      (footprint "eagle-import:CAP0603")
      (libsource (lib "eagle-import") (part "CAPACITOR-0603"))
    )
    (comp (ref "C44")
      (value "1uF")
      (footprint "eagle-import:CAP0402")
      (libsource (lib "eagle-import") (part "CAPACITOR-0402"))
    )
    (comp (ref "C45")
      (value "100nF")
      (footprint "eagle-import:CAP0402")
      (libsource (lib "eagle-import") (part "CAPACITOR-0402"))
    )
    (comp (ref "C46")
      (value "1uF")
      (footprint "eagle-import:CAP0402")
      (libsource (lib "eagle-import") (part "CAPACITOR-0402"))
    )
    (comp (ref "C47")
      (value "220nF")
      (footprint "eagle-import:CAP0402")
      (libsource (lib "eagle-import") (part "CAPACITOR-0402"))
    )
    (comp (ref "C48")
      (value "1uF")
      (footprint "eagle-import:CAP0402")
      (libsource (lib "eagle-import") (part "CAPACITOR-0402"))
    )
    (comp (ref "C49")
      (value "1uF")
      (footprint "eagle-import:CAP0402")
      (libsource (lib "eagle-import") (part "CAPACITOR-0402"))
    )
    (comp (ref "C50")
      (value "220nF")
      (footprint "eagle-import:CAP0402")
      (libsource (lib "eagle-import") (part "CAPACITOR-0402"))
    )
    (comp (ref "C51")
      (value "3.9nF")
      (footprint "eagle-import:CAP0402")
      (libsource (lib "eagle-import") (part "CAPACITOR-0402"))
    )
    (comp (ref "C52")
      (value "3.9nF")
      (footprint "eagle-import:CAP0402")
      (libsource (lib "eagle-import") (part "CAPACITOR-0402"))
    )
    (comp (ref "FB3")
      (value "10uH")
      (footprint "eagle-import:IND0603")
      (libsource (lib "eagle-import") (part "FERRITE-0603"))
    )
    (comp (ref "FB4")
      (value "1uH")
      (footprint "eagle-import:IND0603")
      (libsource (lib "eagle-import") (part "FERRITE-0603"))
    )
    (comp (ref "FB5")
      (value "1uH")
      (footprint "eagle-import:IND0603")
      (libsource (lib "eagle-import") (part "FERRITE-0603"))
    )
    (comp (ref "FB6")
      (value "1uH")
      (footprint "eagle-import:IND0603")
      (libsource (lib "eagle-import") (part "FERRITE-0603"))
    )
    (comp (ref "R14")
      (value "10K Ohms")
      (footprint "eagle-import:RES0402")
      (libsource (lib "eagle-import") (part "RESISTOR-0402"))
    )
    (comp (ref "R15")
      (value "10K Ohms")
      (footprint "eagle-import:RES0402")
      (libsource (lib "eagle-import") (part "RESISTOR-0402"))
    )
    (comp (ref "R16")
      (value "10K Ohms")
      (footprint "eagle-import:RES0402")
      (libsource (lib "eagle-import") (part "RESISTOR-0402"))
    )
    (comp (ref "R17")
      (value "10K Ohms")
      (footprint "eagle-import:RES0402")
      (libsource (lib "eagle-import") (part "RESISTOR-0402"))
    )
    (comp (ref "R18")
      (value "280 Ohms")
      (footprint "eagle-import:RES0402")
      (libsource (lib "eagle-import") (part "RESISTOR-0402"))
    )
    (comp (ref "R19")
      (value "330 Ohms")
      (footprint "eagle-import:RES0402")
      (libsource (lib "eagle-import") (part "RESISTOR-0402"))
    )
    (comp (ref "R20")
      (value "510 Ohms")
      (footprint "eagle-import:RES0402")
      (libsource (lib "eagle-import") (part "RESISTOR-0402"))
    )
    (comp (ref "R21")
      (value "270 Ohms")
      (footprint "eagle-import:RES0402")
      (libsource (lib "eagle-import") (part "RESISTOR-0402"))
    )
    (comp (ref "R22")
      (value "0 Ohms")
      (footprint "eagle-import:RES0402")
      (libsource (lib "eagle-import") (part "RESISTOR-0402"))
    )
    (comp (ref "R23")
      (value "10K Ohms")
      (footprint "eagle-import:RES0402")
      (libsource (lib "eagle-import") (part "RESISTOR-0402"))
    )
    (comp (ref "R24")
      (value "10K Ohms")
      (footprint "eagle-import:RES0402")
      (libsource (lib "eagle-import") (part "RESISTOR-0402"))
    )
    (comp (ref "R25")
      (value "10K Ohms")
      (footprint "eagle-import:RES0402")
      (libsource (lib "eagle-import") (part "RESISTOR-0402"))
    )
    (comp (ref "R26")
      (value "49.9 Ohms")
      (footprint "eagle-import:RES0402")
      (libsource (lib "eagle-import") (part "RESISTOR-0402"))
    )
    (comp (ref "R27")
      (value "100 Ohms")
      (footprint "eagle-import:RES0402")
      (libsource (lib "eagle-import") (part "RESISTOR-0402"))
    )
    (comp (ref "R28")
      (value "49.9 Ohms")
      (footprint "eagle-import:RES0402")
      (libsource (lib "eagle-import") (part "RESISTOR-0402"))
    )
    (comp (ref "R29")
      (value "100 Ohms")
      (footprint "eagle-import:RES0402")
      (libsource (lib "eagle-import") (part "RESISTOR-0402"))
    )
    (comp (ref "R30")
      (value "49.9 Ohms")
      (footprint "eagle-import:RES0402")
      (libsource (lib "eagle-import") (part "RESISTOR-0402"))
    )
    (comp (ref "R31")
      (value "100 Ohms")
      (footprint "eagle-import:RES0402")
      (libsource (lib "eagle-import") (part "RESISTOR-0402"))
    )
    (comp (ref "R32")
      (value "49.9 Ohms")
      (footprint "eagle-import:RES0402")
      (libsource (lib "eagle-import") (part "RESISTOR-0402"))
    )
    (comp (ref "R33")
      (value "100 Ohms")
      (footprint "eagle-import:RES0402")
      (libsource (lib "eagle-import") (part "RESISTOR-0402"))
    )
    (comp (ref "R34")
      (value "49.9 Ohms")
      (footprint "eagle-import:RES0402")
      (libsource (lib "eagle-import") (part "RESISTOR-0402"))
    )
    (comp (ref "R35")
      (value "100 Ohms")
      (footprint "eagle-import:RES0402")
      (libsource (lib "eagle-import") (part "RESISTOR-0402"))
    )
    (comp (ref "U9")
      (value "DSB321SDA")
      (footprint "eagle-import:TCXO-3225")
      (libsource (lib "eagle-import") (part "DSB321SDA"))
    )
    (comp (ref "U10")
      (value "AD9544")
      (footprint "eagle-import:QFN48_2")
      (libsource (lib "eagle-import") (part "AD9544"))
    )
    (comp (ref "C53")
      (value "270pF")
      (footprint "eagle-import:CAP0402")
      (libsource (lib "eagle-import") (part "CAPACITOR-0402"))
    )
    (comp (ref "C54")
      (value "270pF")
      (footprint "eagle-import:CAP0402")
      (libsource (lib "eagle-import") (part "CAPACITOR-0402"))
    )
    (comp (ref "C55")
      (value "100pF")
      (footprint "eagle-import:CAP0402")
      (libsource (lib "eagle-import") (part "CAPACITOR-0402"))
    )
    (comp (ref "C56")
      (value "100pF")
      (footprint "eagle-import:CAP0402")
      (libsource (lib "eagle-import") (part "CAPACITOR-0402"))
    )
    (comp (ref "C57")
      (value "68pF")
      (footprint "eagle-import:CAP0402")
      (libsource (lib "eagle-import") (part "CAPACITOR-0402"))
    )
    (comp (ref "C58")
      (value "180pF")
      (footprint "eagle-import:CAP0402")
      (libsource (lib "eagle-import") (part "CAPACITOR-0402"))
    )
    (comp (ref "C59")
      (value "180pF")
      (footprint "eagle-import:CAP0402")
      (libsource (lib "eagle-import") (part "CAPACITOR-0402"))
    )
    (comp (ref "C60")
      (value "68pF")
      (footprint "eagle-import:CAP0402")
      (libsource (lib "eagle-import") (part "CAPACITOR-0402"))
    )
    (comp (ref "C61")
      (value "68pF")
      (footprint "eagle-import:CAP0402")
      (libsource (lib "eagle-import") (part "CAPACITOR-0402"))
    )
    (comp (ref "C62")
      (value "47pF")
      (footprint "eagle-import:CAP0402")
      (libsource (lib "eagle-import") (part "CAPACITOR-0402"))
    )
    (comp (ref "C63")
      (value "180pF")
      (footprint "eagle-import:CAP0402")
      (libsource (lib "eagle-import") (part "CAPACITOR-0402"))
    )
    (comp (ref "C64")
      (value "180pF")
      (footprint "eagle-import:CAP0402")
      (libsource (lib "eagle-import") (part "CAPACITOR-0402"))
    )
    (comp (ref "C65")
      (value "68pF")
      (footprint "eagle-import:CAP0402")
      (libsource (lib "eagle-import") (part "CAPACITOR-0402"))
    )
    (comp (ref "C66")
      (value "68pF")
      (footprint "eagle-import:CAP0402")
      (libsource (lib "eagle-import") (part "CAPACITOR-0402"))
    )
    (comp (ref "C67")
      (value "47pF")
      (footprint "eagle-import:CAP0402")
      (libsource (lib "eagle-import") (part "CAPACITOR-0402"))
    )
    (comp (ref "C68")
      (value "100nF")
      (footprint "eagle-import:CAP0402")
      (libsource (lib "eagle-import") (part "CAPACITOR-0402"))
    )
    (comp (ref "C69")
      (value "100nF")
      (footprint "eagle-import:CAP0402")
      (libsource (lib "eagle-import") (part "CAPACITOR-0402"))
    )
    (comp (ref "C70")
      (value "100nF")
      (footprint "eagle-import:CAP0402")
      (libsource (lib "eagle-import") (part "CAPACITOR-0402"))
    )
    (comp (ref "C71")
      (value "100nF")
      (footprint "eagle-import:CAP0402")
      (libsource (lib "eagle-import") (part "CAPACITOR-0402"))
    )
    (comp (ref "C72")
      (value "100nF")
      (footprint "eagle-import:CAP0402")
      (libsource (lib "eagle-import") (part "CAPACITOR-0402"))
    )
    (comp (ref "C73")
      (value "100nF")
      (footprint "eagle-import:CAP0402")
      (libsource (lib "eagle-import") (part "CAPACITOR-0402"))
    )
    (comp (ref "C74")
      (value "100nF")
      (footprint "eagle-import:CAP0402")
      (libsource (lib "eagle-import") (part "CAPACITOR-0402"))
    )
    (comp (ref "C75")
      (value "100nF")
      (footprint "eagle-import:CAP0402")
      (libsource (lib "eagle-import") (part "CAPACITOR-0402"))
    )
    (comp (ref "C76")
      (value "100nF")
      (footprint "eagle-import:CAP0402")
      (libsource (lib "eagle-import") (part "CAPACITOR-0402"))
    )
    (comp (ref "C77")
      (value "100nF")
      (footprint "eagle-import:CAP0402")
      (libsource (lib "eagle-import") (part "CAPACITOR-0402"))
    )
    (comp (ref "C78")
      (value "1uF")
      (footprint "eagle-import:CAP0402")
      (libsource (lib "eagle-import") (part "CAPACITOR-0402"))
    )
    (comp (ref "C79")
      (value "1uF")
      (footprint "eagle-import:CAP0402")
      (libsource (lib "eagle-import") (part "CAPACITOR-0402"))
    )
    (comp (ref "C80")
      (value "100nF")
      (footprint "eagle-import:CAP0402")
      (libsource (lib "eagle-import") (part "CAPACITOR-0402"))
    )
    (comp (ref "C81")
      (value "100nF")
      (footprint "eagle-import:CAP0402")
      (libsource (lib "eagle-import") (part "CAPACITOR-0402"))
    )
    (comp (ref "C82")
      (value "100nF")
      (footprint "eagle-import:CAP0402")
      (libsource (lib "eagle-import") (part "CAPACITOR-0402"))
    )
    (comp (ref "C83")
      (value "100nF")
      (footprint "eagle-import:CAP0402")
      (libsource (lib "eagle-import") (part "CAPACITOR-0402"))
    )
    (comp (ref "C84")
      (value "100nF")
      (footprint "eagle-import:CAP0402")
      (libsource (lib "eagle-import") (part "CAPACITOR-0402"))
    )
    (comp (ref "C85")
      (value "1uF")
      (footprint "eagle-import:CAP0402")
      (libsource (lib "eagle-import") (part "CAPACITOR-0402"))
    )
    (comp (ref "C86")
      (value "1uF")
      (footprint "eagle-import:CAP0402")
      (libsource (lib "eagle-import") (part "CAPACITOR-0402"))
    )
    (comp (ref "C87")
      (value "1uF")
      (footprint "eagle-import:CAP0402")
      (libsource (lib "eagle-import") (part "CAPACITOR-0402"))
    )
    (comp (ref "D4")
      (value "BAV99")
      (footprint "eagle-import:SOT23")
      (libsource (lib "eagle-import") (part "BAV99"))
    )
    (comp (ref "D5")
      (value "BAV99")
      (footprint "eagle-import:SOT23")
      (libsource (lib "eagle-import") (part "BAV99"))
    )
    (comp (ref "D6")
      (value "BAV99")
      (footprint "eagle-import:SOT23")
      (libsource (lib "eagle-import") (part "BAV99"))
    )
    (comp (ref "D7")
      (value "BAV99")
      (footprint "eagle-import:SOT23")
      (libsource (lib "eagle-import") (part "BAV99"))
    )
    (comp (ref "D8")
      (value "BAV99")
      (footprint "eagle-import:SOT23")
      (libsource (lib "eagle-import") (part "BAV99"))
    )
    (comp (ref "L2")
      (value "560nH")
      (footprint "eagle-import:IND0402")
      (libsource (lib "eagle-import") (part "INDUCTOR-0402"))
    )
    (comp (ref "L3")
      (value "560nH")
      (footprint "eagle-import:IND0402")
      (libsource (lib "eagle-import") (part "INDUCTOR-0402"))
    )
    (comp (ref "L4")
      (value "220nH")
      (footprint "eagle-import:IND0402")
      (libsource (lib "eagle-import") (part "INDUCTOR-0402"))
    )
    (comp (ref "L5")
      (value "220nH")
      (footprint "eagle-import:IND0402")
      (libsource (lib "eagle-import") (part "INDUCTOR-0402"))
    )
    (comp (ref "L6")
      (value "150nH")
      (footprint "eagle-import:IND0402")
      (libsource (lib "eagle-import") (part "INDUCTOR-0402"))
    )
    (comp (ref "L7")
      (value "82nH")
      (footprint "eagle-import:IND0402")
      (libsource (lib "eagle-import") (part "INDUCTOR-0402"))
    )
    (comp (ref "L8")
      (value "82nH")
      (footprint "eagle-import:IND0402")
      (libsource (lib "eagle-import") (part "INDUCTOR-0402"))
    )
    (comp (ref "L9")
      (value "33nH")
      (footprint "eagle-import:IND0402")
      (libsource (lib "eagle-import") (part "INDUCTOR-0402"))
    )
    (comp (ref "L10")
      (value "33nH")
      (footprint "eagle-import:IND0402")
      (libsource (lib "eagle-import") (part "INDUCTOR-0402"))
    )
    (comp (ref "L11")
      (value "22nH")
      (footprint "eagle-import:IND0402")
      (libsource (lib "eagle-import") (part "INDUCTOR-0402"))
    )
    (comp (ref "L12")
      (value "820nH")
      (footprint "eagle-import:IND0402")
      (libsource (lib "eagle-import") (part "INDUCTOR-0402"))
    )
    (comp (ref "L13")
      (value "820nH")
      (footprint "eagle-import:IND0402")
      (libsource (lib "eagle-import") (part "INDUCTOR-0402"))
    )
    (comp (ref "L14")
      (value "270nH")
      (footprint "eagle-import:IND0402")
      (libsource (lib "eagle-import") (part "INDUCTOR-0402"))
    )
    (comp (ref "L15")
      (value "270nH")
      (footprint "eagle-import:IND0402")
      (libsource (lib "eagle-import") (part "INDUCTOR-0402"))
    )
    (comp (ref "L16")
      (value "180nH")
      (footprint "eagle-import:IND0402")
      (libsource (lib "eagle-import") (part "INDUCTOR-0402"))
    )
    (comp (ref "L17")
      (value "470nH")
      (footprint "eagle-import:IND0402")
      (libsource (lib "eagle-import") (part "INDUCTOR-0402"))
    )
    (comp (ref "L18")
      (value "470nH")
      (footprint "eagle-import:IND0402")
      (libsource (lib "eagle-import") (part "INDUCTOR-0402"))
    )
    (comp (ref "L19")
      (value "180nH")
      (footprint "eagle-import:IND0402")
      (libsource (lib "eagle-import") (part "INDUCTOR-0402"))
    )
    (comp (ref "L20")
      (value "180nH")
      (footprint "eagle-import:IND0402")
      (libsource (lib "eagle-import") (part "INDUCTOR-0402"))
    )
    (comp (ref "L21")
      (value "120nH")
      (footprint "eagle-import:IND0402")
      (libsource (lib "eagle-import") (part "INDUCTOR-0402"))
    )
    (comp (ref "L22")
      (value "680nH")
      (footprint "eagle-import:IND0402")
      (libsource (lib "eagle-import") (part "INDUCTOR-0402"))
    )
    (comp (ref "L23")
      (value "680nH")
      (footprint "eagle-import:IND0402")
      (libsource (lib "eagle-import") (part "INDUCTOR-0402"))
    )
    (comp (ref "L24")
      (value "270nH")
      (footprint "eagle-import:IND0402")
      (libsource (lib "eagle-import") (part "INDUCTOR-0402"))
    )
    (comp (ref "L25")
      (value "270nH")
      (footprint "eagle-import:IND0402")
      (libsource (lib "eagle-import") (part "INDUCTOR-0402"))
    )
    (comp (ref "L26")
      (value "180nH")
      (footprint "eagle-import:IND0402")
      (libsource (lib "eagle-import") (part "INDUCTOR-0402"))
    )
    (comp (ref "L27")
      (value "330nH")
      (footprint "eagle-import:IND0402")
      (libsource (lib "eagle-import") (part "INDUCTOR-0402"))
    )
    (comp (ref "L28")
      (value "330nH")
      (footprint "eagle-import:IND0402")
      (libsource (lib "eagle-import") (part "INDUCTOR-0402"))
    )
    (comp (ref "L29")
      (value "120nH")
      (footprint "eagle-import:IND0402")
      (libsource (lib "eagle-import") (part "INDUCTOR-0402"))
    )
    (comp (ref "L30")
      (value "120nH")
      (footprint "eagle-import:IND0402")
      (libsource (lib "eagle-import") (part "INDUCTOR-0402"))
    )
    (comp (ref "L31")
      (value "82nH")
      (footprint "eagle-import:IND0402")
      (libsource (lib "eagle-import") (part "INDUCTOR-0402"))
    )
    (comp (ref "L32")
      (value "390nH")
      (footprint "eagle-import:IND0402")
      (libsource (lib "eagle-import") (part "INDUCTOR-0402"))
    )
    (comp (ref "L33")
      (value "390nH")
      (footprint "eagle-import:IND0402")
      (libsource (lib "eagle-import") (part "INDUCTOR-0402"))
    )
    (comp (ref "L34")
      (value "150nH")
      (footprint "eagle-import:IND0402")
      (libsource (lib "eagle-import") (part "INDUCTOR-0402"))
    )
    (comp (ref "L35")
      (value "150nH")
      (footprint "eagle-import:IND0402")
      (libsource (lib "eagle-import") (part "INDUCTOR-0402"))
    )
    (comp (ref "L36")
      (value "100nH")
      (footprint "eagle-import:IND0402")
      (libsource (lib "eagle-import") (part "INDUCTOR-0402"))
    )
    (comp (ref "R36")
      (value "100K Ohms")
      (footprint "eagle-import:POT3MM")
      (libsource (lib "eagle-import") (part "POTENTIOMETER-SMD-3X3"))
    )
    (comp (ref "R37")
      (value "100K Ohms")
      (footprint "eagle-import:POT3MM")
      (libsource (lib "eagle-import") (part "POTENTIOMETER-SMD-3X3"))
    )
    (comp (ref "R38")
      (value "100K Ohms")
      (footprint "eagle-import:POT3MM")
      (libsource (lib "eagle-import") (part "POTENTIOMETER-SMD-3X3"))
    )
    (comp (ref "R39")
      (value "100K Ohms")
      (footprint "eagle-import:POT3MM")
      (libsource (lib "eagle-import") (part "POTENTIOMETER-SMD-3X3"))
    )
    (comp (ref "R40")
      (value "100K Ohms")
      (footprint "eagle-import:POT3MM")
      (libsource (lib "eagle-import") (part "POTENTIOMETER-SMD-3X3"))
    )
    (comp (ref "R41")
      (value "0 Ohms")
      (footprint "eagle-import:RES0402")
      (libsource (lib "eagle-import") (part "RESISTOR-0402"))
    )
    (comp (ref "R42")
      (value "0 Ohms")
      (footprint "eagle-import:RES0402")
      (libsource (lib "eagle-import") (part "RESISTOR-0402"))
    )
    (comp (ref "R43")
      (value "0 Ohms")
      (footprint "eagle-import:RES0402")
      (libsource (lib "eagle-import") (part "RESISTOR-0402"))
    )
    (comp (ref "R44")
      (value "0 Ohms")
      (footprint "eagle-import:RES0402")
      (libsource (lib "eagle-import") (part "RESISTOR-0402"))
    )
    (comp (ref "R45")
      (value "0 Ohms")
      (footprint "eagle-import:RES0402")
      (libsource (lib "eagle-import") (part "RESISTOR-0402"))
    )
    (comp (ref "RFCON2")
      (value "RFCON-U.FL")
      (footprint "eagle-import:U.FL")
      (libsource (lib "eagle-import") (part "RFCON-U.FL"))
    )
    (comp (ref "RFCON3")
      (value "RFCON-U.FL")
      (footprint "eagle-import:U.FL")
      (libsource (lib "eagle-import") (part "RFCON-U.FL"))
    )
    (comp (ref "RFCON4")
      (value "RFCON-U.FL")
      (footprint "eagle-import:U.FL")
      (libsource (lib "eagle-import") (part "RFCON-U.FL"))
    )
    (comp (ref "RFCON5")
      (value "RFCON-U.FL")
      (footprint "eagle-import:U.FL")
      (libsource (lib "eagle-import") (part "RFCON-U.FL"))
    )
    (comp (ref "RFCON6")
      (value "RFCON-U.FL")
      (footprint "eagle-import:U.FL")
      (libsource (lib "eagle-import") (part "RFCON-U.FL"))
    )
    (comp (ref "RFCON7")
      (value "RFCON-U.FL")
      (footprint "eagle-import:U.FL")
      (libsource (lib "eagle-import") (part "RFCON-U.FL"))
    )
    (comp (ref "RFCON8")
      (value "RFCON-U.FL")
      (footprint "eagle-import:U.FL")
      (libsource (lib "eagle-import") (part "RFCON-U.FL"))
    )
    (comp (ref "RFCON9")
      (value "RFCON-U.FL")
      (footprint "eagle-import:U.FL")
      (libsource (lib "eagle-import") (part "RFCON-U.FL"))
    )
    (comp (ref "RFCON10")
      (value "RFCON-U.FL")
      (footprint "eagle-import:U.FL")
      (libsource (lib "eagle-import") (part "RFCON-U.FL"))
    )
    (comp (ref "RFCON11")
      (value "RFCON-U.FL")
      (footprint "eagle-import:U.FL")
      (libsource (lib "eagle-import") (part "RFCON-U.FL"))
    )
    (comp (ref "U11")
      (value "74LVC1G17")
      (footprint "eagle-import:SC70-5")
      (libsource (lib "eagle-import") (part "74LVC1G17"))
    )
    (comp (ref "U12")
      (value "74LVC1G17")
      (footprint "eagle-import:SC70-5")
      (libsource (lib "eagle-import") (part "74LVC1G17"))
    )
    (comp (ref "U13")
      (value "74LVC1G17")
      (footprint "eagle-import:SC70-5")
      (libsource (lib "eagle-import") (part "74LVC1G17"))
    )
    (comp (ref "U14")
      (value "74LVC1G17")
      (footprint "eagle-import:SC70-5")
      (libsource (lib "eagle-import") (part "74LVC1G17"))
    )
    (comp (ref "U15")
      (value "74LVC1G17")
      (footprint "eagle-import:SC70-5")
      (libsource (lib "eagle-import") (part "74LVC1G17"))
    )
    (comp (ref "C20")
      (value "10uF")
      (footprint "eagle-import:CAP0603")
      (libsource (lib "eagle-import") (part "CAPACITOR-0603"))
    )
    (comp (ref "C21")
      (value "1uF")
      (footprint "eagle-import:CAP0402")
      (libsource (lib "eagle-import") (part "CAPACITOR-0402"))
    )
    (comp (ref "C22")
      (value "1uF")
      (footprint "eagle-import:CAP0402")
      (libsource (lib "eagle-import") (part "CAPACITOR-0402"))
    )
    (comp (ref "C23")
      (value "10uF")
      (footprint "eagle-import:CAP0603")
      (libsource (lib "eagle-import") (part "CAPACITOR-0603"))
    )
    (comp (ref "C24")
      (value "100nF")
      (footprint "eagle-import:CAP0402")
      (libsource (lib "eagle-import") (part "CAPACITOR-0402"))
    )
    (comp (ref "C25")
      (value "100nF")
      (footprint "eagle-import:CAP0402")
      (libsource (lib "eagle-import") (part "CAPACITOR-0402"))
    )
    (comp (ref "C26")
      (value "1uF")
      (footprint "eagle-import:CAP0402")
      (libsource (lib "eagle-import") (part "CAPACITOR-0402"))
    )
    (comp (ref "C27")
      (value "100nF")
      (footprint "eagle-import:CAP0402")
      (libsource (lib "eagle-import") (part "CAPACITOR-0402"))
    )
    (comp (ref "C28")
      (value "1uF")
      (footprint "eagle-import:CAP0402")
      (libsource (lib "eagle-import") (part "CAPACITOR-0402"))
    )
    (comp (ref "C29")
      (value "100nF")
      (footprint "eagle-import:CAP0402")
      (libsource (lib "eagle-import") (part "CAPACITOR-0402"))
    )
    (comp (ref "C30")
      (value "100uF")
      (footprint "eagle-import:CAP1206")
      (libsource (lib "eagle-import") (part "CAPACITOR-1206"))
    )
    (comp (ref "C31")
      (value "100nF")
      (footprint "eagle-import:CAP0402")
      (libsource (lib "eagle-import") (part "CAPACITOR-0402"))
    )
    (comp (ref "C32")
      (value "100nF")
      (footprint "eagle-import:CAP0402")
      (libsource (lib "eagle-import") (part "CAPACITOR-0402"))
    )
    (comp (ref "FB1")
      (value "1uH")
      (footprint "eagle-import:IND0603")
      (libsource (lib "eagle-import") (part "FERRITE-0603"))
    )
    (comp (ref "FB2")
      (value "1uH")
      (footprint "eagle-import:IND0603")
      (libsource (lib "eagle-import") (part "FERRITE-0603"))
    )
    (comp (ref "R13")
      (value "470 Ohms")
      (footprint "eagle-import:RES0402")
      (libsource (lib "eagle-import") (part "RESISTOR-0402"))
    )
    (comp (ref "U5")
      (value "MCP1501-40")
      (footprint "eagle-import:SOT23-6")
      (libsource (lib "eagle-import") (part "MCP1501-40"))
    )
    (comp (ref "U6")
      (value "AD5541ACPZ")
      (footprint "eagle-import:DFN10")
      (libsource (lib "eagle-import") (part "AD5541A?CPZ"))
    )
    (comp (ref "U7")
      (value "MCP6V31")
      (footprint "eagle-import:SOT23-5")
      (libsource (lib "eagle-import") (part "MCP6V31"))
    )
    (comp (ref "U8")
      (value "OSC5A2B02")
      (footprint "eagle-import:OSC5A2B02")
      (libsource (lib "eagle-import") (part "OSC5A2B02"))
    )
    (comp (ref "BAT1")
      (value "CR2032")
      (footprint "eagle-import:CR2032")
      (libsource (lib "eagle-import") (part "CR2032"))
    )
    (comp (ref "C11")
      (value "100uF")
      (footprint "eagle-import:CAP1206")
      (libsource (lib "eagle-import") (part "CAPACITOR-1206"))
    )
    (comp (ref "C12")
      (value "100nF")
      (footprint "eagle-import:CAP0402")
      (libsource (lib "eagle-import") (part "CAPACITOR-0402"))
    )
    (comp (ref "C13")
      (value "100nF")
      (footprint "eagle-import:CAP0402")
      (libsource (lib "eagle-import") (part "CAPACITOR-0402"))
    )
    (comp (ref "C14")
      (value "100nF")
      (footprint "eagle-import:CAP0402")
      (libsource (lib "eagle-import") (part "CAPACITOR-0402"))
    )
    (comp (ref "C15")
      (value "47pF")
      (footprint "eagle-import:CAP0402")
      (libsource (lib "eagle-import") (part "CAPACITOR-0402"))
    )
    (comp (ref "C16")
      (value "10uF")
      (footprint "eagle-import:CAP0603")
      (libsource (lib "eagle-import") (part "CAPACITOR-0603"))
    )
    (comp (ref "C17")
      (value "10uF")
      (footprint "eagle-import:CAP0603")
      (libsource (lib "eagle-import") (part "CAPACITOR-0603"))
    )
    (comp (ref "C18")
      (value "100nF")
      (footprint "eagle-import:CAP0402")
      (libsource (lib "eagle-import") (part "CAPACITOR-0402"))
    )
    (comp (ref "C19")
      (value "100nF")
      (footprint "eagle-import:CAP0402")
      (libsource (lib "eagle-import") (part "CAPACITOR-0402"))
    )
    (comp (ref "CON3")
      (value "3P-SH-TOP")
      (footprint "eagle-import:SH-03-TOP")
      (libsource (lib "eagle-import") (part "3P-SH-TOP"))
    )
    (comp (ref "D3")
      (value "B0530W")
      (footprint "eagle-import:SOD-123")
      (libsource (lib "eagle-import") (part "B0530W"))
    )
    (comp (ref "L1")
      (value "27nH")
      (footprint "eagle-import:IND0805")
      (libsource (lib "eagle-import") (part "INDUCTOR-0805"))
    )
    (comp (ref "R9")
      (value "10K Ohms")
      (footprint "eagle-import:RES0402")
      (libsource (lib "eagle-import") (part "RESISTOR-0402"))
    )
    (comp (ref "R10")
      (value "10 Ohms")
      (footprint "eagle-import:RES0603")
      (libsource (lib "eagle-import") (part "RESISTOR-0603"))
    )
    (comp (ref "R11")
      (value "DNP")
      (footprint "eagle-import:RES0603")
      (libsource (lib "eagle-import") (part "RESISTOR-0603"))
    )
    (comp (ref "R12")
      (value "1K Ohms")
      (footprint "eagle-import:RES0402")
      (libsource (lib "eagle-import") (part "RESISTOR-0402"))
    )
    (comp (ref "RFCON1")
      (value "RFCON-SMA-EDGE")
      (footprint "eagle-import:SMA-EDGE")
      (libsource (lib "eagle-import") (part "RFCON-SMA-EDGE"))
    )
    (comp (ref "U4")
      (value "MAX-M8Q")
      (footprint "eagle-import:MAX-M8")
      (libsource (lib "eagle-import") (part "MAX-M8Q"))
    )
    (comp (ref "C88")
      (value "100nF")
      (footprint "eagle-import:CAP0402")
      (libsource (lib "eagle-import") (part "CAPACITOR-0402"))
    )
    (comp (ref "C89")
      (value "100nF")
      (footprint "eagle-import:CAP0402")
      (libsource (lib "eagle-import") (part "CAPACITOR-0402"))
    )
    (comp (ref "C90")
      (value "100nF")
      (footprint "eagle-import:CAP0402")
      (libsource (lib "eagle-import") (part "CAPACITOR-0402"))
    )
    (comp (ref "C91")
      (value "4.7uF")
      (footprint "eagle-import:CAP0603")
      (libsource (lib "eagle-import") (part "CAPACITOR-0603"))
    )
    (comp (ref "C92")
      (value "4.7uF")
      (footprint "eagle-import:CAP0603")
      (fields (field (name "VOLTAGE") "35V"))
      (libsource (lib "eagle-import") (part "CAPACITOR-0603"))
    )
    (comp (ref "C93")
      (value "10nF")
      (footprint "eagle-import:CAP0402")
      (libsource (lib "eagle-import") (part "CAPACITOR-0402"))
    )
    (comp (ref "C94")
      (value "1uF")
      (footprint "eagle-import:CAP0603")
      (fields (field (name "VOLTAGE") "50V"))
      (libsource (lib "eagle-import") (part "CAPACITOR-0603"))
    )
    (comp (ref "C95")
      (value "1uF")
      (footprint "eagle-import:CAP0603")
      (fields (field (name "VOLTAGE") "50V"))
      (libsource (lib "eagle-import") (part "CAPACITOR-0603"))
    )
    (comp (ref "C96")
      (value "10nF")
      (footprint "eagle-import:CAP0402")
      (libsource (lib "eagle-import") (part "CAPACITOR-0402"))
    )
    (comp (ref "C97")
      (value "470pF")
      (footprint "eagle-import:CAP0402")
      (libsource (lib "eagle-import") (part "CAPACITOR-0402"))
    )
    (comp (ref "C98")
      (value "1uF")
      (footprint "eagle-import:CAP0402")
      (libsource (lib "eagle-import") (part "CAPACITOR-0402"))
    )
    (comp (ref "C99")
      (value "10nF")
      (footprint "eagle-import:CAP0402")
      (libsource (lib "eagle-import") (part "CAPACITOR-0402"))
    )
    (comp (ref "C100")
      (value "10uF")
      (footprint "eagle-import:CAP0603")
      (libsource (lib "eagle-import") (part "CAPACITOR-0603"))
    )
    (comp (ref "C101")
      (value "100nF")
      (footprint "eagle-import:CAP0402")
      (libsource (lib "eagle-import") (part "CAPACITOR-0402"))
    )
    (comp (ref "C102")
      (value "10uF")
      (footprint "eagle-import:CAP0603")
      (libsource (lib "eagle-import") (part "CAPACITOR-0603"))
    )
    (comp (ref "C103")
      (value "100nF")
      (footprint "eagle-import:CAP0402")
      (libsource (lib "eagle-import") (part "CAPACITOR-0402"))
    )
    (comp (ref "C104")
      (value "100nF")
      (footprint "eagle-import:CAP0402")
      (libsource (lib "eagle-import") (part "CAPACITOR-0402"))
    )
    (comp (ref "C105")
      (value "10pF")
      (footprint "eagle-import:CAP0402")
      (libsource (lib "eagle-import") (part "CAPACITOR-0402"))
    )
    (comp (ref "C106")
      (value "100nF")
      (footprint "eagle-import:CAP0402")
      (libsource (lib "eagle-import") (part "CAPACITOR-0402"))
    )
    (comp (ref "C107")
      (value "100nF")
      (footprint "eagle-import:CAP0402")
      (libsource (lib "eagle-import") (part "CAPACITOR-0402"))
    )
    (comp (ref "C108")
      (value "100uF")
      (footprint "eagle-import:CAP1206")
      (libsource (lib "eagle-import") (part "CAPACITOR-1206"))
    )
    (comp (ref "C109")
      (value "10nF")
      (footprint "eagle-import:CAP0402")
      (libsource (lib "eagle-import") (part "CAPACITOR-0402"))
    )
    (comp (ref "C110")
      (value "100uF")
      (footprint "eagle-import:CAP1206")
      (libsource (lib "eagle-import") (part "CAPACITOR-1206"))
    )
    (comp (ref "C111")
      (value "100uF")
      (footprint "eagle-import:CAP1206")
      (libsource (lib "eagle-import") (part "CAPACITOR-1206"))
    )
    (comp (ref "C112")
      (value "100nF")
      (footprint "eagle-import:CAP0402")
      (libsource (lib "eagle-import") (part "CAPACITOR-0402"))
    )
    (comp (ref "C113")
      (value "10uF")
      (footprint "eagle-import:CAP0603")
      (libsource (lib "eagle-import") (part "CAPACITOR-0603"))
    )
    (comp (ref "C114")
      (value "100nF")
      (footprint "eagle-import:CAP0402")
      (libsource (lib "eagle-import") (part "CAPACITOR-0402"))
    )
    (comp (ref "C115")
      (value "470pF")
      (footprint "eagle-import:CAP0402")
      (libsource (lib "eagle-import") (part "CAPACITOR-0402"))
    )
    (comp (ref "C116")
      (value "470pF")
      (footprint "eagle-import:CAP0402")
      (libsource (lib "eagle-import") (part "CAPACITOR-0402"))
    )
    (comp (ref "C117")
      (value "10uF")
      (footprint "eagle-import:CAP1206")
      (fields (field (name "VOLTAGE") "50V"))
      (libsource (lib "eagle-import") (part "CAPACITOR-1206"))
    )
    (comp (ref "CON4")
      (value "2EDG-2P-5MM")
      (footprint "eagle-import:2EDG-2P-5MM")
      (libsource (lib "eagle-import") (part "2EDG-2P-5MM"))
    )
    (comp (ref "D9")
      (value "LED0603")
      (footprint "eagle-import:0603")
      (fields (field (name "COLOR") "GREEN"))
      (libsource (lib "eagle-import") (part "LED0603"))
    )
    (comp (ref "D10")
      (value "LEDTH3MM")
      (footprint "eagle-import:LED_3MM")
      (fields (field (name "COLOR") "GREEN"))
      (libsource (lib "eagle-import") (part "LEDTH3MM"))
    )
    (comp (ref "D11")
      (value "SMAJ24A")
      (footprint "eagle-import:DO214AC")
      (fields (field (name "MF") "Littelfuse"))
      (libsource (lib "eagle-import") (part "SMAJA24"))
    )
    (comp (ref "F1")
      (value "2.6A Hold")
      (footprint "eagle-import:1206")
      (fields (field (name "HOLD") "3A") (field (name "TRIP") "6A"))
      (libsource (lib "eagle-import") (part "PTC1206"))
    )
    (comp (ref "J1")
      (value "DCJACK")
      (footprint "eagle-import:DC-050")
      (libsource (lib "eagle-import") (part "DCJACK"))
    )
    (comp (ref "L37")
      (value "2.2uH")
      (footprint "eagle-import:IND3515")
      (fields (field (name "CURRENT") "3.8A"))
      (libsource (lib "eagle-import") (part "INDUCTOR-3.2X3.5X1.5MM"))
    )
    (comp (ref "L38")
      (value "4.7uH")
      (footprint "eagle-import:IND0404")
      (fields (field (name "CURRENT") "5.6A"))
      (libsource (lib "eagle-import") (part "INDUCTOR-4X4MM"))
    )
    (comp (ref "R46")
      (value "75K Ohms")
      (footprint "eagle-import:RES0402")
      (libsource (lib "eagle-import") (part "RESISTOR-0402"))
    )
    (comp (ref "R47")
      (value "10K Ohms")
      (footprint "eagle-import:RES0402")
      (libsource (lib "eagle-import") (part "RESISTOR-0402"))
    )
    (comp (ref "R48")
      (value "10K Ohms")
      (footprint "eagle-import:RES0402")
      (libsource (lib "eagle-import") (part "RESISTOR-0402"))
    )
    (comp (ref "R49")
      (value "10K Ohms")
      (footprint "eagle-import:RES0402")
      (libsource (lib "eagle-import") (part "RESISTOR-0402"))
    )
    (comp (ref "R50")
      (value "10K Ohms")
      (footprint "eagle-import:RES0402")
      (libsource (lib "eagle-import") (part "RESISTOR-0402"))
    )
    (comp (ref "R51")
      (value "41.2K Ohms")
      (footprint "eagle-import:RES0402")
      (libsource (lib "eagle-import") (part "RESISTOR-0402"))
    )
    (comp (ref "R52")
      (value "309K Ohms")
      (footprint "eagle-import:RES0402")
      (libsource (lib "eagle-import") (part "RESISTOR-0402"))
    )
    (comp (ref "R53")
      (value "71.5K Ohms")
      (footprint "eagle-import:RES0402")
      (libsource (lib "eagle-import") (part "RESISTOR-0402"))
    )
    (comp (ref "R54")
      (value "1M Ohms")
      (footprint "eagle-import:RES0402")
      (libsource (lib "eagle-import") (part "RESISTOR-0402"))
    )
    (comp (ref "R55")
      (value "226K Ohms")
      (footprint "eagle-import:RES0402")
      (libsource (lib "eagle-import") (part "RESISTOR-0402"))
    )
    (comp (ref "R56")
      (value "510 Ohms")
      (footprint "eagle-import:RES0402")
      (libsource (lib "eagle-import") (part "RESISTOR-0402"))
    )
    (comp (ref "R57")
      (value "100K Ohms")
      (footprint "eagle-import:RES0402")
      (libsource (lib "eagle-import") (part "RESISTOR-0402"))
    )
    (comp (ref "R58")
      (value "10K Ohms")
      (footprint "eagle-import:RES0402")
      (libsource (lib "eagle-import") (part "RESISTOR-0402"))
    )
    (comp (ref "R59")
      (value "100K Ohms")
      (footprint "eagle-import:RES0402")
      (libsource (lib "eagle-import") (part "RESISTOR-0402"))
    )
    (comp (ref "R60")
      (value "75K Ohms")
      (footprint "eagle-import:RES0402")
      (libsource (lib "eagle-import") (part "RESISTOR-0402"))
    )
    (comp (ref "U16")
      (value "ADM7171ACPZ-1.8")
      (footprint "eagle-import:LFCSP8_3X3")
      (libsource (lib "eagle-import") (part "ADM7171ACPZ-1.8"))
    )
    (comp (ref "U17")
      (value "ADM7171ACPZ-5.0")
      (footprint "eagle-import:LFCSP8_3X3")
      (libsource (lib "eagle-import") (part "ADM7171ACPZ-5.0"))
    )
    (comp (ref "U18")
      (value "MIC23155")
      (footprint "eagle-import:DFN10")
      (libsource (lib "eagle-import") (part "MIC23155"))
    )
    (comp (ref "U19")
      (value "LT8636")
      (footprint "eagle-import:QFN20_ASYM_3X4_CORNER")
      (libsource (lib "eagle-import") (part "LT8636"))
    )
    (comp (ref "U20")
      (value "ADM7171ACPZ-3.3")
      (footprint "eagle-import:LFCSP8_3X3")
      (libsource (lib "eagle-import") (part "ADM7171ACPZ-3.3"))
    )
  )
  (nets
    (net (code "1") (name "1V8_PLL_CLEAN") (class "Default")
      (node (ref "C100") (pin "1") (pinfunction "C1_1") (pintype "passive"))
      (node (ref "C101") (pin "1") (pinfunction "C1_1") (pintype "passive"))
      (node (ref "C33") (pin "1") (pinfunction "C1_1") (pintype "passive"))
      (node (ref "FB3") (pin "1") (pinfunction "1_1") (pintype "passive"))
      (node (ref "FB4") (pin "1") (pinfunction "1_1") (pintype "passive"))
      (node (ref "FB5") (pin "1") (pinfunction "1_1") (pintype "passive"))
      (node (ref "U16") (pin "1") (pinfunction "VOUT_1") (pintype "bidirectional"))
      (node (ref "U16") (pin "2") (pinfunction "VOUT_2") (pintype "bidirectional"))
      (node (ref "U16") (pin "3") (pinfunction "SENSE_3") (pintype "bidirectional"))
    )
    (net (code "2") (name "3V3") (class "Default")
      (node (ref "C1") (pin "1") (pinfunction "C1_1") (pintype "passive"))
      (node (ref "C10") (pin "1") (pinfunction "C1_1") (pintype "passive"))
      (node (ref "C107") (pin "1") (pinfunction "C1_1") (pintype "passive"))
      (node (ref "C108") (pin "1") (pinfunction "C1_1") (pintype "passive"))
      (node (ref "C11") (pin "1") (pinfunction "C1_1") (pintype "passive"))
      (node (ref "C12") (pin "1") (pinfunction "C1_1") (pintype "passive"))
      (node (ref "C13") (pin "1") (pinfunction "C1_1") (pintype "passive"))
      (node (ref "C18") (pin "1") (pinfunction "C1_1") (pintype "passive"))
      (node (ref "C2") (pin "1") (pinfunction "C1_1") (pintype "passive"))
      (node (ref "C22") (pin "1") (pinfunction "C1_1") (pintype "passive"))
      (node (ref "C3") (pin "1") (pinfunction "C1_1") (pintype "passive"))
      (node (ref "C4") (pin "1") (pinfunction "C1_1") (pintype "passive"))
      (node (ref "C43") (pin "1") (pinfunction "C1_1") (pintype "passive"))
      (node (ref "C5") (pin "1") (pinfunction "C1_1") (pintype "passive"))
      (node (ref "C6") (pin "1") (pinfunction "C1_1") (pintype "passive"))
      (node (ref "C7") (pin "1") (pinfunction "C1_1") (pintype "passive"))
      (node (ref "C89") (pin "1") (pinfunction "C1_1") (pintype "passive"))
      (node (ref "C9") (pin "1") (pinfunction "C1_1") (pintype "passive"))
      (node (ref "CON2") (pin "1") (pinfunction "S_1") (pintype "passive"))
      (node (ref "D3") (pin "A") (pinfunction "A_A") (pintype "passive"))
      (node (ref "FB2") (pin "1") (pinfunction "1_1") (pintype "passive"))
      (node (ref "FB6") (pin "1") (pinfunction "1_1") (pintype "passive"))
      (node (ref "L37") (pin "2") (pinfunction "2_2") (pintype "passive"))
      (node (ref "R1") (pin "2") (pinfunction "2_2") (pintype "passive"))
      (node (ref "R15") (pin "2") (pinfunction "2_2") (pintype "passive"))
      (node (ref "R23") (pin "2") (pinfunction "2_2") (pintype "passive"))
      (node (ref "R25") (pin "2") (pinfunction "2_2") (pintype "passive"))
      (node (ref "R49") (pin "2") (pinfunction "2_2") (pintype "passive"))
      (node (ref "R5") (pin "2") (pinfunction "2_2") (pintype "passive"))
      (node (ref "R52") (pin "2") (pinfunction "2_2") (pintype "passive"))
      (node (ref "R6") (pin "2") (pinfunction "2_2") (pintype "passive"))
      (node (ref "R7") (pin "2") (pinfunction "2_2") (pintype "passive"))
      (node (ref "R8") (pin "2") (pinfunction "2_2") (pintype "passive"))
      (node (ref "R9") (pin "2") (pinfunction "2_2") (pintype "passive"))
      (node (ref "TC1") (pin "1") (pinfunction "S_1") (pintype "passive"))
      (node (ref "U1") (pin "B10") (pinfunction "VREGI_B10") (pintype "bidirectional"))
      (node (ref "U1") (pin "B11") (pinfunction "VREGO_B11") (pintype "bidirectional"))
      (node (ref "U1") (pin "D5") (pinfunction "IOVDD1_D5") (pintype "bidirectional"))
      (node (ref "U1") (pin "D7") (pinfunction "IOVDD0_D7") (pintype "bidirectional"))
      (node (ref "U1") (pin "F8") (pinfunction "DVDD_F8") (pintype "bidirectional"))
      (node (ref "U1") (pin "G4") (pinfunction "IOVDD2_G4") (pintype "bidirectional"))
      (node (ref "U1") (pin "G8") (pinfunction "IOVDD0_G8") (pintype "bidirectional"))
      (node (ref "U1") (pin "H7") (pinfunction "IOVDD0_H7") (pintype "bidirectional"))
      (node (ref "U1") (pin "K8") (pinfunction "AVDD_K8") (pintype "bidirectional"))
      (node (ref "U1") (pin "K9") (pinfunction "AVDD_K9") (pintype "bidirectional"))
      (node (ref "U1") (pin "L10") (pinfunction "AVDD_L10") (pintype "bidirectional"))
      (node (ref "U1") (pin "L4") (pinfunction "IOVDD0_L4") (pintype "bidirectional"))
      (node (ref "U16") (pin "7") (pinfunction "VIN_7") (pintype "bidirectional"))
      (node (ref "U16") (pin "8") (pinfunction "VIN_8") (pintype "bidirectional"))
      (node (ref "U18") (pin "3") (pinfunction "SNS_3") (pintype "bidirectional"))
      (node (ref "U2") (pin "5") (pinfunction "VCC_5") (pintype "power_in"))
      (node (ref "U3") (pin "5") (pinfunction "VCC_5") (pintype "power_in"))
      (node (ref "U4") (pin "7") (pinfunction "VCC_IO_7") (pintype "bidirectional"))
      (node (ref "U4") (pin "8") (pinfunction "VCC_8") (pintype "bidirectional"))
    )
    (net (code "3") (name "3V3_ANA_CLEAN") (class "Default")
      (node (ref "C113") (pin "1") (pinfunction "C1_1") (pintype "passive"))
      (node (ref "C114") (pin "1") (pinfunction "C1_1") (pintype "passive"))
      (node (ref "C78") (pin "1") (pinfunction "C1_1") (pintype "passive"))
      (node (ref "C79") (pin "1") (pinfunction "C1_1") (pintype "passive"))
      (node (ref "C80") (pin "1") (pinfunction "C1_1") (pintype "passive"))
      (node (ref "C81") (pin "1") (pinfunction "C1_1") (pintype "passive"))
      (node (ref "C82") (pin "1") (pinfunction "C1_1") (pintype "passive"))
      (node (ref "C83") (pin "1") (pinfunction "C1_1") (pintype "passive"))
      (node (ref "C84") (pin "1") (pinfunction "C1_1") (pintype "passive"))
      (node (ref "C85") (pin "1") (pinfunction "C1_1") (pintype "passive"))
      (node (ref "C86") (pin "1") (pinfunction "C1_1") (pintype "passive"))
      (node (ref "C87") (pin "1") (pinfunction "C1_1") (pintype "passive"))
      (node (ref "R36") (pin "1") (pinfunction "CCW_1") (pintype "passive"))
      (node (ref "R37") (pin "1") (pinfunction "CCW_1") (pintype "passive"))
      (node (ref "R38") (pin "1") (pinfunction "CCW_1") (pintype "passive"))
      (node (ref "R39") (pin "1") (pinfunction "CCW_1") (pintype "passive"))
      (node (ref "R40") (pin "1") (pinfunction "CCW_1") (pintype "passive"))
      (node (ref "U11") (pin "5") (pinfunction "VCC_5") (pintype "power_in"))
      (node (ref "U12") (pin "5") (pinfunction "VCC_5") (pintype "power_in"))
      (node (ref "U13") (pin "5") (pinfunction "VCC_5") (pintype "power_in"))
      (node (ref "U14") (pin "5") (pinfunction "VCC_5") (pintype "power_in"))
      (node (ref "U15") (pin "5") (pinfunction "VCC_5") (pintype "power_in"))
      (node (ref "U20") (pin "1") (pinfunction "VOUT_1") (pintype "bidirectional"))
      (node (ref "U20") (pin "2") (pinfunction "VOUT_2") (pintype "bidirectional"))
      (node (ref "U20") (pin "3") (pinfunction "SENSE_3") (pintype "bidirectional"))
    )
    (net (code "4") (name "3V3_PGOOD") (class "Default")
      (node (ref "R49") (pin "1") (pinfunction "1_1") (pintype "passive"))
      (node (ref "U1") (pin "E1") (pinfunction "PA6_E1") (pintype "bidirectional"))
      (node (ref "U16") (pin "5") (pinfunction "EN_5") (pintype "bidirectional"))
      (node (ref "U18") (pin "5") (pinfunction "PG_5") (pintype "bidirectional"))
    )
    (net (code "5") (name "5V0") (class "Default")
      (node (ref "C105") (pin "1") (pinfunction "C1_1") (pintype "passive"))
      (node (ref "C106") (pin "1") (pinfunction "C1_1") (pintype "passive"))
      (node (ref "C110") (pin "1") (pinfunction "C1_1") (pintype "passive"))
      (node (ref "C111") (pin "1") (pinfunction "C1_1") (pintype "passive"))
      (node (ref "C112") (pin "1") (pinfunction "C1_1") (pintype "passive"))
      (node (ref "C16") (pin "1") (pinfunction "C1_1") (pintype "passive"))
      (node (ref "C88") (pin "1") (pinfunction "C1_1") (pintype "passive"))
      (node (ref "C90") (pin "1") (pinfunction "C1_1") (pintype "passive"))
      (node (ref "C91") (pin "1") (pinfunction "C1_1") (pintype "passive"))
      (node (ref "L38") (pin "2") (pinfunction "2_2") (pintype "passive"))
      (node (ref "R11") (pin "1") (pinfunction "1_1") (pintype "passive"))
      (node (ref "R50") (pin "2") (pinfunction "2_2") (pintype "passive"))
      (node (ref "R54") (pin "2") (pinfunction "2_2") (pintype "passive"))
      (node (ref "R56") (pin "2") (pinfunction "2_2") (pintype "passive"))
      (node (ref "R59") (pin "2") (pinfunction "2_2") (pintype "passive"))
      (node (ref "U17") (pin "7") (pinfunction "VIN_7") (pintype "bidirectional"))
      (node (ref "U17") (pin "8") (pinfunction "VIN_8") (pintype "bidirectional"))
      (node (ref "U18") (pin "8") (pinfunction "VIN_8") (pintype "bidirectional"))
      (node (ref "U18") (pin "9") (pinfunction "VIN_9") (pintype "bidirectional"))
      (node (ref "U19") (pin "2") (pinfunction "BIAS_2") (pintype "bidirectional"))
      (node (ref "U20") (pin "7") (pinfunction "VIN_7") (pintype "bidirectional"))
      (node (ref "U20") (pin "8") (pinfunction "VIN_8") (pintype "bidirectional"))
    )
    (net (code "6") (name "5V0_ANA_OCXO_CLEAN") (class "Default")
      (node (ref "C102") (pin "1") (pinfunction "C1_1") (pintype "passive"))
      (node (ref "C103") (pin "1") (pinfunction "C1_1") (pintype "passive"))
      (node (ref "C20") (pin "1") (pinfunction "C1_1") (pintype "passive"))
      (node (ref "C30") (pin "1") (pinfunction "C1_1") (pintype "passive"))
      (node (ref "C31") (pin "1") (pinfunction "C1_1") (pintype "passive"))
      (node (ref "FB1") (pin "1") (pinfunction "1_1") (pintype "passive"))
      (node (ref "U17") (pin "1") (pinfunction "VOUT_1") (pintype "bidirectional"))
      (node (ref "U17") (pin "2") (pinfunction "VOUT_2") (pintype "bidirectional"))
      (node (ref "U17") (pin "3") (pinfunction "SENSE_3") (pintype "bidirectional"))
      (node (ref "U8") (pin "5") (pinfunction "VDD_5") (pintype "power_in"))
    )
    (net (code "7") (name "5V0_EN") (class "Default")
      (node (ref "R46") (pin "1") (pinfunction "1_1") (pintype "passive"))
      (node (ref "R47") (pin "2") (pinfunction "2_2") (pintype "passive"))
      (node (ref "U19") (pin "14") (pinfunction "EN/UV_14") (pintype "bidirectional"))
    )
    (net (code "8") (name "5V0_PGOOD") (class "Default")
      (node (ref "R50") (pin "1") (pinfunction "1_1") (pintype "passive"))
      (node (ref "U18") (pin "2") (pinfunction "EN_2") (pintype "bidirectional"))
      (node (ref "U19") (pin "1") (pinfunction "PG_1") (pintype "bidirectional"))
      (node (ref "U20") (pin "5") (pinfunction "EN_5") (pintype "bidirectional"))
    )
    (net (code "9") (name "5V0_VSENSE") (class "Default")
      (node (ref "C116") (pin "1") (pinfunction "C1_1") (pintype "passive"))
      (node (ref "R59") (pin "1") (pinfunction "1_1") (pintype "passive"))
      (node (ref "R60") (pin "2") (pinfunction "2_2") (pintype "passive"))
      (node (ref "U1") (pin "H10") (pinfunction "PD6_H10") (pintype "bidirectional"))
    )
    (net (code "10") (name "CLK0") (class "Default")
      (node (ref "C73") (pin "1") (pinfunction "C1_1") (pintype "passive"))
      (node (ref "R27") (pin "2") (pinfunction "2_2") (pintype "passive"))
      (node (ref "U10") (pin "11") (pinfunction "OUT0A_11") (pintype "bidirectional"))
    )
    (net (code "11") (name "CLK1") (class "Default")
      (node (ref "C74") (pin "1") (pinfunction "C1_1") (pintype "passive"))
      (node (ref "R29") (pin "2") (pinfunction "2_2") (pintype "passive"))
      (node (ref "U10") (pin "14") (pinfunction "OUT0B_14") (pintype "bidirectional"))
    )
    (net (code "12") (name "CLK2") (class "Default")
      (node (ref "C75") (pin "1") (pinfunction "C1_1") (pintype "passive"))
      (node (ref "R31") (pin "2") (pinfunction "2_2") (pintype "passive"))
      (node (ref "U10") (pin "17") (pinfunction "OUT0C_17") (pintype "bidirectional"))
    )
    (net (code "13") (name "CLK3") (class "Default")
      (node (ref "C76") (pin "1") (pinfunction "C1_1") (pintype "passive"))
      (node (ref "R33") (pin "2") (pinfunction "2_2") (pintype "passive"))
      (node (ref "U10") (pin "22") (pinfunction "OUT1B_22") (pintype "bidirectional"))
    )
    (net (code "14") (name "CLK4") (class "Default")
      (node (ref "C77") (pin "1") (pinfunction "C1_1") (pintype "passive"))
      (node (ref "R35") (pin "2") (pinfunction "2_2") (pintype "passive"))
      (node (ref "U10") (pin "25") (pinfunction "OUT1A_25") (pintype "bidirectional"))
    )
    (net (code "15") (name "DAC_DIN") (class "Default")
      (node (ref "U1") (pin "C3") (pinfunction "PE10_C3") (pintype "bidirectional"))
      (node (ref "U6") (pin "7") (pinfunction "DIN_7") (pintype "bidirectional"))
    )
    (net (code "16") (name "DAC_SCLK") (class "Default")
      (node (ref "U1") (pin "A3") (pinfunction "PE12_A3") (pintype "bidirectional"))
      (node (ref "U6") (pin "6") (pinfunction "SCLK_6") (pintype "bidirectional"))
    )
    (net (code "17") (name "GND") (class "Default")
      (node (ref "BAT1") (pin "-") (pinfunction "-_-") (pintype "power_in"))
      (node (ref "C1") (pin "2") (pinfunction "C2_2") (pintype "passive"))
      (node (ref "C10") (pin "2") (pinfunction "C2_2") (pintype "passive"))
      (node (ref "C100") (pin "2") (pinfunction "C2_2") (pintype "passive"))
      (node (ref "C101") (pin "2") (pinfunction "C2_2") (pintype "passive"))
      (node (ref "C102") (pin "2") (pinfunction "C2_2") (pintype "passive"))
      (node (ref "C103") (pin "2") (pinfunction "C2_2") (pintype "passive"))
      (node (ref "C106") (pin "2") (pinfunction "C2_2") (pintype "passive"))
      (node (ref "C107") (pin "2") (pinfunction "C2_2") (pintype "passive"))
      (node (ref "C108") (pin "2") (pinfunction "C2_2") (pintype "passive"))
      (node (ref "C109") (pin "2") (pinfunction "C2_2") (pintype "passive"))
      (node (ref "C11") (pin "2") (pinfunction "C2_2") (pintype "passive"))
      (node (ref "C110") (pin "2") (pinfunction "C2_2") (pintype "passive"))
      (node (ref "C111") (pin "2") (pinfunction "C2_2") (pintype "passive"))
      (node (ref "C112") (pin "2") (pinfunction "C2_2") (pintype "passive"))
      (node (ref "C113") (pin "2") (pinfunction "C2_2") (pintype "passive"))
      (node (ref "C114") (pin "2") (pinfunction "C2_2") (pintype "passive"))
      (node (ref "C115") (pin "2") (pinfunction "C2_2") (pintype "passive"))
      (node (ref "C116") (pin "2") (pinfunction "C2_2") (pintype "passive"))
      (node (ref "C117") (pin "2") (pinfunction "C2_2") (pintype "passive"))
      (node (ref "C12") (pin "2") (pinfunction "C2_2") (pintype "passive"))
      (node (ref "C13") (pin "2") (pinfunction "C2_2") (pintype "passive"))
      (node (ref "C14") (pin "2") (pinfunction "C2_2") (pintype "passive"))
      (node (ref "C16") (pin "2") (pinfunction "C2_2") (pintype "passive"))
      (node (ref "C17") (pin "2") (pinfunction "C2_2") (pintype "passive"))
      (node (ref "C18") (pin "2") (pinfunction "C2_2") (pintype "passive"))
      (node (ref "C19") (pin "2") (pinfunction "C2_2") (pintype "passive"))
      (node (ref "C2") (pin "2") (pinfunction "C2_2") (pintype "passive"))
      (node (ref "C20") (pin "2") (pinfunction "C2_2") (pintype "passive"))
      (node (ref "C21") (pin "2") (pinfunction "C2_2") (pintype "passive"))
      (node (ref "C22") (pin "2") (pinfunction "C2_2") (pintype "passive"))
      (node (ref "C23") (pin "2") (pinfunction "C2_2") (pintype "passive"))
      (node (ref "C24") (pin "2") (pinfunction "C2_2") (pintype "passive"))
      (node (ref "C25") (pin "2") (pinfunction "C2_2") (pintype "passive"))
      (node (ref "C26") (pin "2") (pinfunction "C2_2") (pintype "passive"))
      (node (ref "C27") (pin "2") (pinfunction "C2_2") (pintype "passive"))
      (node (ref "C28") (pin "2") (pinfunction "C2_2") (pintype "passive"))
      (node (ref "C29") (pin "2") (pinfunction "C2_2") (pintype "passive"))
      (node (ref "C3") (pin "2") (pinfunction "C2_2") (pintype "passive"))
      (node (ref "C30") (pin "2") (pinfunction "C2_2") (pintype "passive"))
      (node (ref "C31") (pin "2") (pinfunction "C2_2") (pintype "passive"))
      (node (ref "C32") (pin "2") (pinfunction "C2_2") (pintype "passive"))
      (node (ref "C33") (pin "2") (pinfunction "C2_2") (pintype "passive"))
      (node (ref "C34") (pin "2") (pinfunction "C2_2") (pintype "passive"))
      (node (ref "C35") (pin "2") (pinfunction "C2_2") (pintype "passive"))
      (node (ref "C36") (pin "2") (pinfunction "C2_2") (pintype "passive"))
      (node (ref "C37") (pin "2") (pinfunction "C2_2") (pintype "passive"))
      (node (ref "C38") (pin "2") (pinfunction "C2_2") (pintype "passive"))
      (node (ref "C39") (pin "2") (pinfunction "C2_2") (pintype "passive"))
      (node (ref "C4") (pin "2") (pinfunction "C2_2") (pintype "passive"))
      (node (ref "C40") (pin "2") (pinfunction "C2_2") (pintype "passive"))
      (node (ref "C41") (pin "2") (pinfunction "C2_2") (pintype "passive"))
      (node (ref "C43") (pin "2") (pinfunction "C2_2") (pintype "passive"))
      (node (ref "C44") (pin "2") (pinfunction "C2_2") (pintype "passive"))
      (node (ref "C45") (pin "2") (pinfunction "C2_2") (pintype "passive"))
      (node (ref "C46") (pin "2") (pinfunction "C2_2") (pintype "passive"))
      (node (ref "C47") (pin "2") (pinfunction "C2_2") (pintype "passive"))
      (node (ref "C48") (pin "2") (pinfunction "C2_2") (pintype "passive"))
      (node (ref "C49") (pin "2") (pinfunction "C2_2") (pintype "passive"))
      (node (ref "C5") (pin "2") (pinfunction "C2_2") (pintype "passive"))
      (node (ref "C50") (pin "2") (pinfunction "C2_2") (pintype "passive"))
      (node (ref "C53") (pin "2") (pinfunction "C2_2") (pintype "passive"))
      (node (ref "C54") (pin "2") (pinfunction "C2_2") (pintype "passive"))
      (node (ref "C55") (pin "2") (pinfunction "C2_2") (pintype "passive"))
      (node (ref "C56") (pin "2") (pinfunction "C2_2") (pintype "passive"))
      (node (ref "C57") (pin "2") (pinfunction "C2_2") (pintype "passive"))
      (node (ref "C58") (pin "2") (pinfunction "C2_2") (pintype "passive"))
      (node (ref "C59") (pin "2") (pinfunction "C2_2") (pintype "passive"))
      (node (ref "C6") (pin "2") (pinfunction "C2_2") (pintype "passive"))
      (node (ref "C60") (pin "2") (pinfunction "C2_2") (pintype "passive"))
      (node (ref "C61") (pin "2") (pinfunction "C2_2") (pintype "passive"))
      (node (ref "C62") (pin "2") (pinfunction "C2_2") (pintype "passive"))
      (node (ref "C63") (pin "2") (pinfunction "C2_2") (pintype "passive"))
      (node (ref "C64") (pin "2") (pinfunction "C2_2") (pintype "passive"))
      (node (ref "C65") (pin "2") (pinfunction "C2_2") (pintype "passive"))
      (node (ref "C66") (pin "2") (pinfunction "C2_2") (pintype "passive"))
      (node (ref "C67") (pin "2") (pinfunction "C2_2") (pintype "passive"))
      (node (ref "C7") (pin "2") (pinfunction "C2_2") (pintype "passive"))
      (node (ref "C78") (pin "2") (pinfunction "C2_2") (pintype "passive"))
      (node (ref "C79") (pin "2") (pinfunction "C2_2") (pintype "passive"))
      (node (ref "C8") (pin "2") (pinfunction "C2_2") (pintype "passive"))
      (node (ref "C80") (pin "2") (pinfunction "C2_2") (pintype "passive"))
      (node (ref "C81") (pin "2") (pinfunction "C2_2") (pintype "passive"))
      (node (ref "C82") (pin "2") (pinfunction "C2_2") (pintype "passive"))
      (node (ref "C83") (pin "2") (pinfunction "C2_2") (pintype "passive"))
      (node (ref "C84") (pin "2") (pinfunction "C2_2") (pintype "passive"))
      (node (ref "C85") (pin "2") (pinfunction "C2_2") (pintype "passive"))
      (node (ref "C86") (pin "2") (pinfunction "C2_2") (pintype "passive"))
      (node (ref "C87") (pin "2") (pinfunction "C2_2") (pintype "passive"))
      (node (ref "C88") (pin "2") (pinfunction "C2_2") (pintype "passive"))
      (node (ref "C89") (pin "2") (pinfunction "C2_2") (pintype "passive"))
      (node (ref "C9") (pin "2") (pinfunction "C2_2") (pintype "passive"))
      (node (ref "C90") (pin "2") (pinfunction "C2_2") (pintype "passive"))
      (node (ref "C91") (pin "2") (pinfunction "C2_2") (pintype "passive"))
      (node (ref "C92") (pin "2") (pinfunction "C2_2") (pintype "passive"))
      (node (ref "C93") (pin "2") (pinfunction "C2_2") (pintype "passive"))
      (node (ref "C94") (pin "2") (pinfunction "C2_2") (pintype "passive"))
      (node (ref "C95") (pin "2") (pinfunction "C2_2") (pintype "passive"))
      (node (ref "C96") (pin "2") (pinfunction "C2_2") (pintype "passive"))
      (node (ref "C97") (pin "2") (pinfunction "C2_2") (pintype "passive"))
      (node (ref "C98") (pin "2") (pinfunction "C2_2") (pintype "passive"))
      (node (ref "C99") (pin "2") (pinfunction "C2_2") (pintype "passive"))
      (node (ref "CON1") (pin "3") (pinfunction "S_3") (pintype "passive"))
      (node (ref "CON2") (pin "4") (pinfunction "S_4") (pintype "passive"))
      (node (ref "CON3") (pin "3") (pinfunction "S_3") (pintype "passive"))
      (node (ref "CON4") (pin "P$1") (pinfunction "S_P$1") (pintype "passive"))
      (node (ref "D1") (pin "C") (pinfunction "C_C") (pintype "passive"))
      (node (ref "D10") (pin "K") (pinfunction "C_K") (pintype "passive"))
      (node (ref "D11") (pin "A") (pinfunction "A_A") (pintype "passive"))
      (node (ref "D2") (pin "K") (pinfunction "C_K") (pintype "passive"))
      (node (ref "D4") (pin "1") (pinfunction "A_1") (pintype "passive"))
      (node (ref "D4") (pin "2") (pinfunction "C_2") (pintype "passive"))
      (node (ref "D5") (pin "1") (pinfunction "A_1") (pintype "passive"))
      (node (ref "D5") (pin "2") (pinfunction "C_2") (pintype "passive"))
      (node (ref "D6") (pin "1") (pinfunction "A_1") (pintype "passive"))
      (node (ref "D6") (pin "2") (pinfunction "C_2") (pintype "passive"))
      (node (ref "D7") (pin "1") (pinfunction "A_1") (pintype "passive"))
      (node (ref "D7") (pin "2") (pinfunction "C_2") (pintype "passive"))
      (node (ref "D8") (pin "1") (pinfunction "A_1") (pintype "passive"))
      (node (ref "D8") (pin "2") (pinfunction "C_2") (pintype "passive"))
      (node (ref "D9") (pin "C") (pinfunction "C_C") (pintype "passive"))
      (node (ref "J1") (pin "O") (pinfunction "O_O") (pintype "bidirectional"))
      (node (ref "R13") (pin "1") (pinfunction "1_1") (pintype "passive"))
      (node (ref "R14") (pin "1") (pinfunction "1_1") (pintype "passive"))
      (node (ref "R16") (pin "1") (pinfunction "1_1") (pintype "passive"))
      (node (ref "R17") (pin "1") (pinfunction "1_1") (pintype "passive"))
      (node (ref "R19") (pin "1") (pinfunction "1_1") (pintype "passive"))
      (node (ref "R21") (pin "1") (pinfunction "1_1") (pintype "passive"))
      (node (ref "R24") (pin "1") (pinfunction "1_1") (pintype "passive"))
      (node (ref "R26") (pin "1") (pinfunction "1_1") (pintype "passive"))
      (node (ref "R27") (pin "1") (pinfunction "1_1") (pintype "passive"))
      (node (ref "R28") (pin "1") (pinfunction "1_1") (pintype "passive"))
      (node (ref "R29") (pin "1") (pinfunction "1_1") (pintype "passive"))
      (node (ref "R30") (pin "1") (pinfunction "1_1") (pintype "passive"))
      (node (ref "R31") (pin "1") (pinfunction "1_1") (pintype "passive"))
      (node (ref "R32") (pin "1") (pinfunction "1_1") (pintype "passive"))
      (node (ref "R33") (pin "1") (pinfunction "1_1") (pintype "passive"))
      (node (ref "R34") (pin "1") (pinfunction "1_1") (pintype "passive"))
      (node (ref "R35") (pin "1") (pinfunction "1_1") (pintype "passive"))
      (node (ref "R36") (pin "3") (pinfunction "CW_3") (pintype "passive"))
      (node (ref "R37") (pin "3") (pinfunction "CW_3") (pintype "passive"))
      (node (ref "R38") (pin "3") (pinfunction "CW_3") (pintype "passive"))
      (node (ref "R39") (pin "3") (pinfunction "CW_3") (pintype "passive"))
      (node (ref "R40") (pin "3") (pinfunction "CW_3") (pintype "passive"))
      (node (ref "R47") (pin "1") (pinfunction "1_1") (pintype "passive"))
      (node (ref "R48") (pin "1") (pinfunction "1_1") (pintype "passive"))
      (node (ref "R51") (pin "1") (pinfunction "1_1") (pintype "passive"))
      (node (ref "R53") (pin "1") (pinfunction "1_1") (pintype "passive"))
      (node (ref "R55") (pin "1") (pinfunction "1_1") (pintype "passive"))
      (node (ref "R58") (pin "1") (pinfunction "1_1") (pintype "passive"))
      (node (ref "R60") (pin "1") (pinfunction "1_1") (pintype "passive"))
      (node (ref "RFCON1") (pin "GND@0") (pinfunction "GND_GND@0") (pintype "bidirectional"))
      (node (ref "RFCON1") (pin "GND@1") (pinfunction "GND_GND@1") (pintype "bidirectional"))
      (node (ref "RFCON1") (pin "GND@2") (pinfunction "GND_GND@2") (pintype "bidirectional"))
      (node (ref "RFCON1") (pin "GND@3") (pinfunction "GND_GND@3") (pintype "bidirectional"))
      (node (ref "RFCON10") (pin "P$1") (pinfunction "GND_P$1") (pintype "bidirectional"))
      (node (ref "RFCON10") (pin "P$2") (pinfunction "GND_P$2") (pintype "bidirectional"))
      (node (ref "RFCON11") (pin "P$1") (pinfunction "GND_P$1") (pintype "bidirectional"))
      (node (ref "RFCON11") (pin "P$2") (pinfunction "GND_P$2") (pintype "bidirectional"))
      (node (ref "RFCON2") (pin "P$1") (pinfunction "GND_P$1") (pintype "bidirectional"))
      (node (ref "RFCON2") (pin "P$2") (pinfunction "GND_P$2") (pintype "bidirectional"))
      (node (ref "RFCON3") (pin "P$1") (pinfunction "GND_P$1") (pintype "bidirectional"))
      (node (ref "RFCON3") (pin "P$2") (pinfunction "GND_P$2") (pintype "bidirectional"))
      (node (ref "RFCON4") (pin "P$1") (pinfunction "GND_P$1") (pintype "bidirectional"))
      (node (ref "RFCON4") (pin "P$2") (pinfunction "GND_P$2") (pintype "bidirectional"))
      (node (ref "RFCON5") (pin "P$1") (pinfunction "GND_P$1") (pintype "bidirectional"))
      (node (ref "RFCON5") (pin "P$2") (pinfunction "GND_P$2") (pintype "bidirectional"))
      (node (ref "RFCON6") (pin "P$1") (pinfunction "GND_P$1") (pintype "bidirectional"))
      (node (ref "RFCON6") (pin "P$2") (pinfunction "GND_P$2") (pintype "bidirectional"))
      (node (ref "RFCON7") (pin "P$1") (pinfunction "GND_P$1") (pintype "bidirectional"))
      (node (ref "RFCON7") (pin "P$2") (pinfunction "GND_P$2") (pintype "bidirectional"))
      (node (ref "RFCON8") (pin "P$1") (pinfunction "GND_P$1") (pintype "bidirectional"))
      (node (ref "RFCON8") (pin "P$2") (pinfunction "GND_P$2") (pintype "bidirectional"))
      (node (ref "RFCON9") (pin "P$1") (pinfunction "GND_P$1") (pintype "bidirectional"))
      (node (ref "RFCON9") (pin "P$2") (pinfunction "GND_P$2") (pintype "bidirectional"))
      (node (ref "TC1") (pin "3") (pinfunction "S_3") (pintype "passive"))
      (node (ref "U1") (pin "C7") (pinfunction "VSS_C7") (pintype "bidirectional"))
      (node (ref "U1") (pin "D4") (pinfunction "VSS_D4") (pintype "bidirectional"))
      (node (ref "U1") (pin "F9") (pinfunction "VSS_F9") (pintype "bidirectional"))
      (node (ref "U1") (pin "G3") (pinfunction "VSS_G3") (pintype "bidirectional"))
      (node (ref "U1") (pin "G9") (pinfunction "VSS_G9") (pintype "bidirectional"))
      (node (ref "U1") (pin "H6") (pinfunction "VSS_H6") (pintype "bidirectional"))
      (node (ref "U1") (pin "K10") (pinfunction "VSS_K10") (pintype "bidirectional"))
      (node (ref "U1") (pin "K4") (pinfunction "VSS_K4") (pintype "bidirectional"))
      (node (ref "U1") (pin "K7") (pinfunction "VSS_K7") (pintype "bidirectional"))
      (node (ref "U1") (pin "L7") (pinfunction "VSS_L7") (pintype "bidirectional"))
      (node (ref "U10") (pin "49") (pinfunction "GND_49") (pintype "bidirectional"))
      (node (ref "U11") (pin "3") (pinfunction "GND_3") (pintype "power_in"))
      (node (ref "U12") (pin "3") (pinfunction "GND_3") (pintype "power_in"))
      (node (ref "U13") (pin "3") (pinfunction "GND_3") (pintype "power_in"))
      (node (ref "U14") (pin "3") (pinfunction "GND_3") (pintype "power_in"))
      (node (ref "U15") (pin "3") (pinfunction "GND_3") (pintype "power_in"))
      (node (ref "U16") (pin "6") (pinfunction "GND_6") (pintype "bidirectional"))
      (node (ref "U16") (pin "9") (pinfunction "GND_9") (pintype "bidirectional"))
      (node (ref "U17") (pin "6") (pinfunction "GND_6") (pintype "bidirectional"))
      (node (ref "U17") (pin "9") (pinfunction "GND_9") (pintype "bidirectional"))
      (node (ref "U18") (pin "10") (pinfunction "PGND_10") (pintype "bidirectional"))
      (node (ref "U18") (pin "11") (pinfunction "PGND_11") (pintype "bidirectional"))
      (node (ref "U18") (pin "7") (pinfunction "AGND_7") (pintype "bidirectional"))
      (node (ref "U19") (pin "12") (pinfunction "GND_12") (pintype "bidirectional"))
      (node (ref "U19") (pin "13") (pinfunction "GND_13") (pintype "bidirectional"))
      (node (ref "U19") (pin "21") (pinfunction "GND_21") (pintype "bidirectional"))
      (node (ref "U19") (pin "4") (pinfunction "GND_4") (pintype "bidirectional"))
      (node (ref "U19") (pin "5") (pinfunction "GND_5") (pintype "bidirectional"))
      (node (ref "U19") (pin "M1") (pinfunction "GND_M1") (pintype "bidirectional"))
      (node (ref "U19") (pin "M2") (pinfunction "GND_M2") (pintype "bidirectional"))
      (node (ref "U19") (pin "M3") (pinfunction "GND_M3") (pintype "bidirectional"))
      (node (ref "U19") (pin "M4") (pinfunction "GND_M4") (pintype "bidirectional"))
      (node (ref "U2") (pin "3") (pinfunction "GND_3") (pintype "power_in"))
      (node (ref "U20") (pin "6") (pinfunction "GND_6") (pintype "bidirectional"))
      (node (ref "U20") (pin "9") (pinfunction "GND_9") (pintype "bidirectional"))
      (node (ref "U3") (pin "3") (pinfunction "GND_3") (pintype "power_in"))
      (node (ref "U4") (pin "1") (pinfunction "GND_1") (pintype "bidirectional"))
      (node (ref "U4") (pin "10") (pinfunction "GND_10") (pintype "bidirectional"))
      (node (ref "U4") (pin "12") (pinfunction "GND_12") (pintype "bidirectional"))
      (node (ref "U5") (pin "2") (pinfunction "GND_2") (pintype "bidirectional"))
      (node (ref "U5") (pin "3") (pinfunction "GND_3") (pintype "bidirectional"))
      (node (ref "U5") (pin "5") (pinfunction "GND_5") (pintype "bidirectional"))
      (node (ref "U6") (pin "11") (pinfunction "AGND_11") (pintype "bidirectional"))
      (node (ref "U6") (pin "3") (pinfunction "AGND_3") (pintype "bidirectional"))
      (node (ref "U6") (pin "8") (pinfunction "~{LDAC}_8") (pintype "bidirectional"))
      (node (ref "U6") (pin "9") (pinfunction "DGND_9") (pintype "bidirectional"))
      (node (ref "U7") (pin "2") (pinfunction "V-_2") (pintype "power_in"))
      (node (ref "U8") (pin "2") (pinfunction "GND_2") (pintype "power_in"))
      (node (ref "U9") (pin "1") (pinfunction "GND_1") (pintype "power_in"))
      (node (ref "U9") (pin "2") (pinfunction "GND_2") (pintype "power_in"))
    )
    (net (code "18") (name "GPS_BIAS_INT") (class "Default")
      (node (ref "C14") (pin "1") (pinfunction "C1_1") (pintype "passive"))
      (node (ref "R10") (pin "2") (pinfunction "2_2") (pintype "passive"))
      (node (ref "U4") (pin "14") (pinfunction "VCC_RF_14") (pintype "bidirectional"))
    )
    (net (code "19") (name "GPS_RXD") (class "Default")
      (node (ref "CON3") (pin "2") (pinfunction "S_2") (pintype "passive"))
      (node (ref "U1") (pin "C2") (pinfunction "PA0_C2") (pintype "bidirectional"))
      (node (ref "U4") (pin "3") (pinfunction "RXD_3") (pintype "bidirectional"))
    )
    (net (code "20") (name "GPS_TIMEPULSE") (class "Default")
      (node (ref "R18") (pin "2") (pinfunction "2_2") (pintype "passive"))
      (node (ref "U3") (pin "2") (pinfunction "A_2") (pintype "input"))
      (node (ref "U4") (pin "4") (pinfunction "TIMEPULSE_4") (pintype "bidirectional"))
    )
    (net (code "21") (name "GPS_TIMEPULSE_BUF") (class "Default")
      (node (ref "U1") (pin "A1") (pinfunction "PE15_A1") (pintype "bidirectional"))
      (node (ref "U3") (pin "4") (pinfunction "Y_4") (pintype "output"))
    )
    (net (code "22") (name "GPS_TXD{slash}TXREADY") (class "Default")
      (node (ref "CON3") (pin "1") (pinfunction "S_1") (pintype "passive"))
      (node (ref "U1") (pin "C1") (pinfunction "PA1_C1") (pintype "bidirectional"))
      (node (ref "U4") (pin "2") (pinfunction "TXD_2") (pintype "bidirectional"))
    )
    (net (code "23") (name "GPS_VBKP") (class "Default")
      (node (ref "BAT1") (pin "+") (pinfunction "+_+") (pintype "power_in"))
      (node (ref "C17") (pin "1") (pinfunction "C1_1") (pintype "passive"))
      (node (ref "C19") (pin "1") (pinfunction "C1_1") (pintype "passive"))
      (node (ref "R12") (pin "1") (pinfunction "1_1") (pintype "passive"))
      (node (ref "U4") (pin "6") (pinfunction "V_BKP_6") (pintype "bidirectional"))
    )
    (net (code "24") (name "I2C1_SCL") (class "Default")
      (node (ref "R3") (pin "2") (pinfunction "2_2") (pintype "passive"))
      (node (ref "R8") (pin "1") (pinfunction "1_1") (pintype "passive"))
      (node (ref "U1") (pin "L6") (pinfunction "PB12_L6") (pintype "bidirectional"))
    )
    (net (code "25") (name "I2C1_SDA") (class "Default")
      (node (ref "R2") (pin "2") (pinfunction "2_2") (pintype "passive"))
      (node (ref "R6") (pin "1") (pinfunction "1_1") (pintype "passive"))
      (node (ref "U1") (pin "L5") (pinfunction "PB11_L5") (pintype "bidirectional"))
    )
    (net (code "26") (name "I2C2_SCL") (class "Default")
      (node (ref "CON2") (pin "3") (pinfunction "S_3") (pintype "passive"))
      (node (ref "R5") (pin "1") (pinfunction "1_1") (pintype "passive"))
      (node (ref "U1") (pin "A7") (pinfunction "PF5_A7") (pintype "bidirectional"))
      (node (ref "U10") (pin "2") (pinfunction "SCL/SCLK_2") (pintype "bidirectional"))
      (node (ref "U4") (pin "17") (pinfunction "SCL_17") (pintype "bidirectional"))
    )
    (net (code "27") (name "I2C2_SDA") (class "Default")
      (node (ref "CON2") (pin "2") (pinfunction "S_2") (pintype "passive"))
      (node (ref "R1") (pin "1") (pinfunction "1_1") (pintype "passive"))
      (node (ref "U1") (pin "B4") (pinfunction "PE8_B4") (pintype "bidirectional"))
      (node (ref "U10") (pin "4") (pinfunction "SDA/SDIO_4") (pintype "bidirectional"))
      (node (ref "U4") (pin "16") (pinfunction "SDA_16") (pintype "bidirectional"))
    )
    (net (code "28") (name "MCU_LED") (class "Default")
      (node (ref "R4") (pin "2") (pinfunction "2_2") (pintype "passive"))
      (node (ref "U1") (pin "L8") (pinfunction "PB13_L8") (pintype "bidirectional"))
    )
    (net (code "29") (name "MCU_SWCLK") (class "Default")
      (node (ref "TC1") (pin "4") (pinfunction "S_4") (pintype "passive"))
      (node (ref "U1") (pin "E8") (pinfunction "PF0_E8") (pintype "bidirectional"))
    )
    (net (code "30") (name "MCU_SWDIO") (class "Default")
      (node (ref "TC1") (pin "2") (pinfunction "S_2") (pintype "passive"))
      (node (ref "U1") (pin "D8") (pinfunction "PF1_D8") (pintype "bidirectional"))
    )
    (net (code "31") (name "MCU_SWO") (class "Default")
      (node (ref "TC1") (pin "6") (pinfunction "S_6") (pintype "passive"))
      (node (ref "U1") (pin "C8") (pinfunction "PF2_C8") (pintype "bidirectional"))
    )
    (net (code "32") (name "Net-(C8-C1)") (class "Default")
      (node (ref "C8") (pin "1") (pinfunction "C1_1") (pintype "passive"))
      (node (ref "U1") (pin "F11") (pinfunction "DECOUPLE_F11") (pintype "bidirectional"))
    )
    (net (code "33") (name "Net-(C15-C1)") (class "Default")
      (node (ref "C15") (pin "1") (pinfunction "C1_1") (pintype "passive"))
      (node (ref "U4") (pin "11") (pinfunction "RF_IN_11") (pintype "bidirectional"))
    )
    (net (code "34") (name "Net-(C15-C2)") (class "Default")
      (node (ref "C15") (pin "2") (pinfunction "C2_2") (pintype "passive"))
      (node (ref "L1") (pin "1") (pinfunction "1_1") (pintype "passive"))
      (node (ref "RFCON1") (pin "SIG") (pinfunction "SIGNAL_SIG") (pintype "bidirectional"))
    )
    (net (code "35") (name "Net-(C21-C1)") (class "Default")
      (node (ref "C21") (pin "1") (pinfunction "C1_1") (pintype "passive"))
      (node (ref "C26") (pin "1") (pinfunction "C1_1") (pintype "passive"))
      (node (ref "C28") (pin "1") (pinfunction "C1_1") (pintype "passive"))
      (node (ref "FB1") (pin "2") (pinfunction "2_2") (pintype "passive"))
      (node (ref "U5") (pin "4") (pinfunction "~{SHDN}_4") (pintype "bidirectional"))
      (node (ref "U5") (pin "6") (pinfunction "VDD_6") (pintype "bidirectional"))
      (node (ref "U6") (pin "1") (pinfunction "VDD_1") (pintype "bidirectional"))
      (node (ref "U7") (pin "5") (pinfunction "V+_5") (pintype "power_in"))
    )
    (net (code "36") (name "Net-(C23-C1)") (class "Default")
      (node (ref "C23") (pin "1") (pinfunction "C1_1") (pintype "passive"))
      (node (ref "C24") (pin "1") (pinfunction "C1_1") (pintype "passive"))
      (node (ref "U5") (pin "1") (pinfunction "VOUT_1") (pintype "bidirectional"))
      (node (ref "U6") (pin "4") (pinfunction "REF_4") (pintype "bidirectional"))
    )
    (net (code "37") (name "Net-(C25-C1)") (class "Default")
      (node (ref "C25") (pin "1") (pinfunction "C1_1") (pintype "passive"))
      (node (ref "FB2") (pin "2") (pinfunction "2_2") (pintype "passive"))
      (node (ref "U6") (pin "10") (pinfunction "VLOGIC_10") (pintype "bidirectional"))
    )
    (net (code "38") (name "Net-(C27-C1)") (class "Default")
      (node (ref "C27") (pin "1") (pinfunction "C1_1") (pintype "passive"))
      (node (ref "U6") (pin "2") (pinfunction "VOUT_2") (pintype "bidirectional"))
      (node (ref "U7") (pin "3") (pinfunction "+IN_3") (pintype "input"))
    )
    (net (code "39") (name "Net-(C34-C1)") (class "Default")
      (node (ref "C34") (pin "1") (pinfunction "C1_1") (pintype "passive"))
      (node (ref "FB3") (pin "2") (pinfunction "2_2") (pintype "passive"))
      (node (ref "U9") (pin "4") (pinfunction "VDD_4") (pintype "power_in"))
    )
    (net (code "40") (name "Net-(C35-C1)") (class "Default")
      (node (ref "C35") (pin "1") (pinfunction "C1_1") (pintype "passive"))
      (node (ref "C36") (pin "1") (pinfunction "C1_1") (pintype "passive"))
      (node (ref "C37") (pin "1") (pinfunction "C1_1") (pintype "passive"))
      (node (ref "C38") (pin "1") (pinfunction "C1_1") (pintype "passive"))
      (node (ref "C39") (pin "1") (pinfunction "C1_1") (pintype "passive"))
      (node (ref "C41") (pin "1") (pinfunction "C1_1") (pintype "passive"))
      (node (ref "C44") (pin "1") (pinfunction "C1_1") (pintype "passive"))
      (node (ref "C46") (pin "1") (pinfunction "C1_1") (pintype "passive"))
      (node (ref "C48") (pin "1") (pinfunction "C1_1") (pintype "passive"))
      (node (ref "FB4") (pin "2") (pinfunction "2_2") (pintype "passive"))
      (node (ref "FB5") (pin "2") (pinfunction "2_2") (pintype "passive"))
      (node (ref "U10") (pin "10") (pinfunction "VDD_10") (pintype "bidirectional"))
      (node (ref "U10") (pin "13") (pinfunction "VDD_13") (pintype "bidirectional"))
      (node (ref "U10") (pin "19") (pinfunction "VDD_19") (pintype "bidirectional"))
      (node (ref "U10") (pin "20") (pinfunction "VDD_20") (pintype "bidirectional"))
      (node (ref "U10") (pin "24") (pinfunction "VDD_24") (pintype "bidirectional"))
      (node (ref "U10") (pin "27") (pinfunction "VDD_27") (pintype "bidirectional"))
      (node (ref "U10") (pin "28") (pinfunction "VDD_28") (pintype "bidirectional"))
      (node (ref "U10") (pin "31") (pinfunction "VDD_31") (pintype "bidirectional"))
      (node (ref "U10") (pin "40") (pinfunction "VDD_40") (pintype "bidirectional"))
      (node (ref "U10") (pin "41") (pinfunction "VDD_41") (pintype "bidirectional"))
      (node (ref "U10") (pin "45") (pinfunction "VDD_45") (pintype "bidirectional"))
      (node (ref "U10") (pin "6") (pinfunction "VDD_6") (pintype "bidirectional"))
      (node (ref "U10") (pin "9") (pinfunction "VDD_9") (pintype "bidirectional"))
    )
    (net (code "41") (name "Net-(C40-C1)") (class "Default")
      (node (ref "C40") (pin "1") (pinfunction "C1_1") (pintype "passive"))
      (node (ref "C42") (pin "1") (pinfunction "C1_1") (pintype "passive"))
      (node (ref "R22") (pin "1") (pinfunction "1_1") (pintype "passive"))
      (node (ref "R24") (pin "2") (pinfunction "2_2") (pintype "passive"))
    )
    (net (code "42") (name "Net-(C42-C2)") (class "Default")
      (node (ref "C42") (pin "2") (pinfunction "C2_2") (pintype "passive"))
      (node (ref "U10") (pin "42") (pinfunction "XOA_42") (pintype "bidirectional"))
    )
    (net (code "43") (name "Net-(C45-C1)") (class "Default")
      (node (ref "C45") (pin "1") (pinfunction "C1_1") (pintype "passive"))
      (node (ref "U10") (pin "43") (pinfunction "XOB_43") (pintype "bidirectional"))
    )
    (net (code "44") (name "Net-(C47-C1)") (class "Default")
      (node (ref "C47") (pin "1") (pinfunction "C1_1") (pintype "passive"))
      (node (ref "C51") (pin "1") (pinfunction "C1_1") (pintype "passive"))
      (node (ref "U10") (pin "7") (pinfunction "LDO0_7") (pintype "bidirectional"))
    )
    (net (code "45") (name "Net-(C49-C1)") (class "Default")
      (node (ref "C49") (pin "1") (pinfunction "C1_1") (pintype "passive"))
      (node (ref "FB6") (pin "2") (pinfunction "2_2") (pintype "passive"))
      (node (ref "U10") (pin "3") (pinfunction "VDDIOA_3") (pintype "bidirectional"))
      (node (ref "U10") (pin "34") (pinfunction "VDDIOB_34") (pintype "bidirectional"))
    )
    (net (code "46") (name "Net-(C50-C1)") (class "Default")
      (node (ref "C50") (pin "1") (pinfunction "C1_1") (pintype "passive"))
      (node (ref "C52") (pin "1") (pinfunction "C1_1") (pintype "passive"))
      (node (ref "U10") (pin "30") (pinfunction "LDO1_30") (pintype "bidirectional"))
    )
    (net (code "47") (name "Net-(C51-C2)") (class "Default")
      (node (ref "C51") (pin "2") (pinfunction "C2_2") (pintype "passive"))
      (node (ref "U10") (pin "8") (pinfunction "LF0_8") (pintype "bidirectional"))
    )
    (net (code "48") (name "Net-(C52-C2)") (class "Default")
      (node (ref "C52") (pin "2") (pinfunction "C2_2") (pintype "passive"))
      (node (ref "U10") (pin "29") (pinfunction "LF1_29") (pintype "bidirectional"))
    )
    (net (code "49") (name "Net-(C53-C1)") (class "Default")
      (node (ref "C53") (pin "1") (pinfunction "C1_1") (pintype "passive"))
      (node (ref "L7") (pin "2") (pinfunction "2_2") (pintype "passive"))
    )
    (net (code "50") (name "Net-(C54-C1)") (class "Default")
      (node (ref "C54") (pin "1") (pinfunction "C1_1") (pintype "passive"))
      (node (ref "L8") (pin "2") (pinfunction "2_2") (pintype "passive"))
    )
    (net (code "51") (name "Net-(C55-C1)") (class "Default")
      (node (ref "C55") (pin "1") (pinfunction "C1_1") (pintype "passive"))
      (node (ref "L9") (pin "2") (pinfunction "2_2") (pintype "passive"))
    )
    (net (code "52") (name "Net-(C56-C1)") (class "Default")
      (node (ref "C56") (pin "1") (pinfunction "C1_1") (pintype "passive"))
      (node (ref "L10") (pin "2") (pinfunction "2_2") (pintype "passive"))
    )
    (net (code "53") (name "Net-(C57-C1)") (class "Default")
      (node (ref "C57") (pin "1") (pinfunction "C1_1") (pintype "passive"))
      (node (ref "L11") (pin "2") (pinfunction "2_2") (pintype "passive"))
    )
    (net (code "54") (name "Net-(C58-C1)") (class "Default")
      (node (ref "C58") (pin "1") (pinfunction "C1_1") (pintype "passive"))
      (node (ref "L17") (pin "2") (pinfunction "2_2") (pintype "passive"))
    )
    (net (code "55") (name "Net-(C59-C1)") (class "Default")
      (node (ref "C59") (pin "1") (pinfunction "C1_1") (pintype "passive"))
      (node (ref "L18") (pin "2") (pinfunction "2_2") (pintype "passive"))
    )
    (net (code "56") (name "Net-(C60-C1)") (class "Default")
      (node (ref "C60") (pin "1") (pinfunction "C1_1") (pintype "passive"))
      (node (ref "L19") (pin "2") (pinfunction "2_2") (pintype "passive"))
    )
    (net (code "57") (name "Net-(C61-C1)") (class "Default")
      (node (ref "C61") (pin "1") (pinfunction "C1_1") (pintype "passive"))
      (node (ref "L20") (pin "2") (pinfunction "2_2") (pintype "passive"))
    )
    (net (code "58") (name "Net-(C62-C1)") (class "Default")
      (node (ref "C62") (pin "1") (pinfunction "C1_1") (pintype "passive"))
      (node (ref "L21") (pin "2") (pinfunction "2_2") (pintype "passive"))
    )
    (net (code "59") (name "Net-(C63-C1)") (class "Default")
      (node (ref "C63") (pin "1") (pinfunction "C1_1") (pintype "passive"))
      (node (ref "L27") (pin "2") (pinfunction "2_2") (pintype "passive"))
    )
    (net (code "60") (name "Net-(C64-C1)") (class "Default")
      (node (ref "C64") (pin "1") (pinfunction "C1_1") (pintype "passive"))
      (node (ref "L28") (pin "2") (pinfunction "2_2") (pintype "passive"))
    )
    (net (code "61") (name "Net-(C65-C1)") (class "Default")
      (node (ref "C65") (pin "1") (pinfunction "C1_1") (pintype "passive"))
      (node (ref "L29") (pin "2") (pinfunction "2_2") (pintype "passive"))
    )
    (net (code "62") (name "Net-(C66-C1)") (class "Default")
      (node (ref "C66") (pin "1") (pinfunction "C1_1") (pintype "passive"))
      (node (ref "L30") (pin "2") (pinfunction "2_2") (pintype "passive"))
    )
    (net (code "63") (name "Net-(C67-C1)") (class "Default")
      (node (ref "C67") (pin "1") (pinfunction "C1_1") (pintype "passive"))
      (node (ref "L31") (pin "2") (pinfunction "2_2") (pintype "passive"))
    )
    (net (code "64") (name "Net-(C68-C1)") (class "Default")
      (node (ref "C68") (pin "1") (pinfunction "C1_1") (pintype "passive"))
      (node (ref "L32") (pin "2") (pinfunction "2_2") (pintype "passive"))
    )
    (net (code "65") (name "Net-(C68-C2)") (class "Default")
      (node (ref "C68") (pin "2") (pinfunction "C2_2") (pintype "passive"))
      (node (ref "D4") (pin "3") (pinfunction "MID_3") (pintype "passive"))
      (node (ref "RFCON2") (pin "P$3") (pinfunction "SIGNAL_P$3") (pintype "bidirectional"))
    )
    (net (code "66") (name "Net-(C69-C1)") (class "Default")
      (node (ref "C69") (pin "1") (pinfunction "C1_1") (pintype "passive"))
      (node (ref "L33") (pin "2") (pinfunction "2_2") (pintype "passive"))
    )
    (net (code "67") (name "Net-(C69-C2)") (class "Default")
      (node (ref "C69") (pin "2") (pinfunction "C2_2") (pintype "passive"))
      (node (ref "D5") (pin "3") (pinfunction "MID_3") (pintype "passive"))
      (node (ref "RFCON3") (pin "P$3") (pinfunction "SIGNAL_P$3") (pintype "bidirectional"))
    )
    (net (code "68") (name "Net-(C70-C1)") (class "Default")
      (node (ref "C70") (pin "1") (pinfunction "C1_1") (pintype "passive"))
      (node (ref "L34") (pin "2") (pinfunction "2_2") (pintype "passive"))
    )
    (net (code "69") (name "Net-(C70-C2)") (class "Default")
      (node (ref "C70") (pin "2") (pinfunction "C2_2") (pintype "passive"))
      (node (ref "D6") (pin "3") (pinfunction "MID_3") (pintype "passive"))
      (node (ref "RFCON4") (pin "P$3") (pinfunction "SIGNAL_P$3") (pintype "bidirectional"))
    )
    (net (code "70") (name "Net-(C71-C1)") (class "Default")
      (node (ref "C71") (pin "1") (pinfunction "C1_1") (pintype "passive"))
      (node (ref "L35") (pin "2") (pinfunction "2_2") (pintype "passive"))
    )
    (net (code "71") (name "Net-(C71-C2)") (class "Default")
      (node (ref "C71") (pin "2") (pinfunction "C2_2") (pintype "passive"))
      (node (ref "D7") (pin "3") (pinfunction "MID_3") (pintype "passive"))
      (node (ref "RFCON5") (pin "P$3") (pinfunction "SIGNAL_P$3") (pintype "bidirectional"))
    )
    (net (code "72") (name "Net-(C72-C1)") (class "Default")
      (node (ref "C72") (pin "1") (pinfunction "C1_1") (pintype "passive"))
      (node (ref "L36") (pin "2") (pinfunction "2_2") (pintype "passive"))
    )
    (net (code "73") (name "Net-(C72-C2)") (class "Default")
      (node (ref "C72") (pin "2") (pinfunction "C2_2") (pintype "passive"))
      (node (ref "D8") (pin "3") (pinfunction "MID_3") (pintype "passive"))
      (node (ref "RFCON6") (pin "P$3") (pinfunction "SIGNAL_P$3") (pintype "bidirectional"))
    )
    (net (code "74") (name "Net-(C73-C2)") (class "Default")
      (node (ref "C73") (pin "2") (pinfunction "C2_2") (pintype "passive"))
      (node (ref "R36") (pin "2") (pinfunction "WIPER_2") (pintype "passive"))
      (node (ref "U11") (pin "2") (pinfunction "A_2") (pintype "input"))
    )
    (net (code "75") (name "Net-(C74-C2)") (class "Default")
      (node (ref "C74") (pin "2") (pinfunction "C2_2") (pintype "passive"))
      (node (ref "R37") (pin "2") (pinfunction "WIPER_2") (pintype "passive"))
      (node (ref "U12") (pin "2") (pinfunction "A_2") (pintype "input"))
    )
    (net (code "76") (name "Net-(C75-C2)") (class "Default")
      (node (ref "C75") (pin "2") (pinfunction "C2_2") (pintype "passive"))
      (node (ref "R38") (pin "2") (pinfunction "WIPER_2") (pintype "passive"))
      (node (ref "U13") (pin "2") (pinfunction "A_2") (pintype "input"))
    )
    (net (code "77") (name "Net-(C76-C2)") (class "Default")
      (node (ref "C76") (pin "2") (pinfunction "C2_2") (pintype "passive"))
      (node (ref "R39") (pin "2") (pinfunction "WIPER_2") (pintype "passive"))
      (node (ref "U14") (pin "2") (pinfunction "A_2") (pintype "input"))
    )
    (net (code "78") (name "Net-(C77-C2)") (class "Default")
      (node (ref "C77") (pin "2") (pinfunction "C2_2") (pintype "passive"))
      (node (ref "R40") (pin "2") (pinfunction "WIPER_2") (pintype "passive"))
      (node (ref "U15") (pin "2") (pinfunction "A_2") (pintype "input"))
    )
    (net (code "79") (name "Net-(C93-C1)") (class "Default")
      (node (ref "C93") (pin "1") (pinfunction "C1_1") (pintype "passive"))
      (node (ref "U16") (pin "4") (pinfunction "SS_4") (pintype "bidirectional"))
    )
    (net (code "80") (name "Net-(C96-C1)") (class "Default")
      (node (ref "C96") (pin "1") (pinfunction "C1_1") (pintype "passive"))
      (node (ref "U17") (pin "4") (pinfunction "SS_4") (pintype "bidirectional"))
    )
    (net (code "81") (name "Net-(C97-C1)") (class "Default")
      (node (ref "C97") (pin "1") (pinfunction "C1_1") (pintype "passive"))
      (node (ref "U18") (pin "6") (pinfunction "SS_6") (pintype "bidirectional"))
    )
    (net (code "82") (name "Net-(C98-C1)") (class "Default")
      (node (ref "C98") (pin "1") (pinfunction "C1_1") (pintype "passive"))
      (node (ref "U19") (pin "15") (pinfunction "SYNC/MODE_15") (pintype "bidirectional"))
      (node (ref "U19") (pin "3") (pinfunction "INTVCC_3") (pintype "bidirectional"))
    )
    (net (code "83") (name "Net-(C99-C1)") (class "Default")
      (node (ref "C99") (pin "1") (pinfunction "C1_1") (pintype "passive"))
      (node (ref "U19") (pin "18") (pinfunction "TR/SS_18") (pintype "bidirectional"))
    )
    (net (code "84") (name "Net-(C104-C1)") (class "Default")
      (node (ref "C104") (pin "1") (pinfunction "C1_1") (pintype "passive"))
      (node (ref "L38") (pin "1") (pinfunction "1_1") (pintype "passive"))
      (node (ref "U19") (pin "10") (pinfunction "SW_10") (pintype "bidirectional"))
      (node (ref "U19") (pin "8") (pinfunction "SW_8") (pintype "bidirectional"))
      (node (ref "U19") (pin "9") (pinfunction "SW_9") (pintype "bidirectional"))
    )
    (net (code "85") (name "Net-(C104-C2)") (class "Default")
      (node (ref "C104") (pin "2") (pinfunction "C2_2") (pintype "passive"))
      (node (ref "U19") (pin "7") (pinfunction "BST_7") (pintype "bidirectional"))
    )
    (net (code "86") (name "Net-(C105-C2)") (class "Default")
      (node (ref "C105") (pin "2") (pinfunction "C2_2") (pintype "passive"))
      (node (ref "R54") (pin "1") (pinfunction "1_1") (pintype "passive"))
      (node (ref "R55") (pin "2") (pinfunction "2_2") (pintype "passive"))
      (node (ref "U19") (pin "19") (pinfunction "FB_19") (pintype "bidirectional"))
      (node (ref "U19") (pin "20") (pinfunction "FB_20") (pintype "bidirectional"))
    )
    (net (code "87") (name "Net-(C109-C1)") (class "Default")
      (node (ref "C109") (pin "1") (pinfunction "C1_1") (pintype "passive"))
      (node (ref "U20") (pin "4") (pinfunction "SS_4") (pintype "bidirectional"))
    )
    (net (code "88") (name "Net-(CON1A-S)") (class "Default")
      (node (ref "CON1") (pin "1") (pinfunction "S_1") (pintype "passive"))
      (node (ref "R2") (pin "1") (pinfunction "1_1") (pintype "passive"))
    )
    (net (code "89") (name "Net-(CON1B-S)") (class "Default")
      (node (ref "CON1") (pin "2") (pinfunction "S_2") (pintype "passive"))
      (node (ref "R3") (pin "1") (pinfunction "1_1") (pintype "passive"))
    )
    (net (code "90") (name "Net-(CON4B-S)") (class "Default")
      (node (ref "CON4") (pin "P$2") (pinfunction "S_P$2") (pintype "passive"))
      (node (ref "F1") (pin "2") (pinfunction "2_2") (pintype "passive"))
      (node (ref "J1") (pin "C") (pinfunction "C_C") (pintype "bidirectional"))
      (node (ref "J1") (pin "C'") (pinfunction "C_C'") (pintype "bidirectional"))
    )
    (net (code "91") (name "Net-(D1-PadA)") (class "Default")
      (node (ref "D1") (pin "A") (pinfunction "A_A") (pintype "passive"))
      (node (ref "D2") (pin "A") (pinfunction "A_A") (pintype "passive"))
      (node (ref "R4") (pin "1") (pinfunction "1_1") (pintype "passive"))
    )
    (net (code "92") (name "Net-(D3-PadC)") (class "Default")
      (node (ref "D3") (pin "C") (pinfunction "C_C") (pintype "passive"))
      (node (ref "R12") (pin "2") (pinfunction "2_2") (pintype "passive"))
    )
    (net (code "93") (name "Net-(D10-PadA)") (class "Default")
      (node (ref "D10") (pin "A") (pinfunction "A_A") (pintype "passive"))
      (node (ref "D9") (pin "A") (pinfunction "A_A") (pintype "passive"))
      (node (ref "R56") (pin "1") (pinfunction "1_1") (pintype "passive"))
    )
    (net (code "94") (name "Net-(L1-Pad2)") (class "Default")
      (node (ref "L1") (pin "2") (pinfunction "2_2") (pintype "passive"))
      (node (ref "R10") (pin "1") (pinfunction "1_1") (pintype "passive"))
      (node (ref "R11") (pin "2") (pinfunction "2_2") (pintype "passive"))
    )
    (net (code "95") (name "Net-(L10-Pad1)") (class "Default")
      (node (ref "L10") (pin "1") (pinfunction "1_1") (pintype "passive"))
      (node (ref "L15") (pin "1") (pinfunction "1_1") (pintype "passive"))
      (node (ref "L5") (pin "2") (pinfunction "2_2") (pintype "passive"))
    )
    (net (code "96") (name "Net-(L11-Pad1)") (class "Default")
      (node (ref "L11") (pin "1") (pinfunction "1_1") (pintype "passive"))
      (node (ref "L16") (pin "1") (pinfunction "1_1") (pintype "passive"))
      (node (ref "L6") (pin "2") (pinfunction "2_2") (pintype "passive"))
    )
    (net (code "97") (name "Net-(L12-Pad1)") (class "Default")
      (node (ref "L12") (pin "1") (pinfunction "1_1") (pintype "passive"))
      (node (ref "L2") (pin "2") (pinfunction "2_2") (pintype "passive"))
      (node (ref "L7") (pin "1") (pinfunction "1_1") (pintype "passive"))
    )
    (net (code "98") (name "Net-(L12-Pad2)") (class "Default")
      (node (ref "L12") (pin "2") (pinfunction "2_2") (pintype "passive"))
      (node (ref "L17") (pin "1") (pinfunction "1_1") (pintype "passive"))
      (node (ref "L22") (pin "1") (pinfunction "1_1") (pintype "passive"))
    )
    (net (code "99") (name "Net-(L13-Pad1)") (class "Default")
      (node (ref "L13") (pin "1") (pinfunction "1_1") (pintype "passive"))
      (node (ref "L3") (pin "2") (pinfunction "2_2") (pintype "passive"))
      (node (ref "L8") (pin "1") (pinfunction "1_1") (pintype "passive"))
    )
    (net (code "100") (name "Net-(L13-Pad2)") (class "Default")
      (node (ref "L13") (pin "2") (pinfunction "2_2") (pintype "passive"))
      (node (ref "L18") (pin "1") (pinfunction "1_1") (pintype "passive"))
      (node (ref "L23") (pin "1") (pinfunction "1_1") (pintype "passive"))
    )
    (net (code "101") (name "Net-(L14-Pad1)") (class "Default")
      (node (ref "L14") (pin "1") (pinfunction "1_1") (pintype "passive"))
      (node (ref "L4") (pin "2") (pinfunction "2_2") (pintype "passive"))
      (node (ref "L9") (pin "1") (pinfunction "1_1") (pintype "passive"))
    )
    (net (code "102") (name "Net-(L14-Pad2)") (class "Default")
      (node (ref "L14") (pin "2") (pinfunction "2_2") (pintype "passive"))
      (node (ref "L19") (pin "1") (pinfunction "1_1") (pintype "passive"))
      (node (ref "L24") (pin "1") (pinfunction "1_1") (pintype "passive"))
    )
    (net (code "103") (name "Net-(L15-Pad2)") (class "Default")
      (node (ref "L15") (pin "2") (pinfunction "2_2") (pintype "passive"))
      (node (ref "L20") (pin "1") (pinfunction "1_1") (pintype "passive"))
      (node (ref "L25") (pin "1") (pinfunction "1_1") (pintype "passive"))
    )
    (net (code "104") (name "Net-(L16-Pad2)") (class "Default")
      (node (ref "L16") (pin "2") (pinfunction "2_2") (pintype "passive"))
      (node (ref "L21") (pin "1") (pinfunction "1_1") (pintype "passive"))
      (node (ref "L26") (pin "1") (pinfunction "1_1") (pintype "passive"))
    )
    (net (code "105") (name "Net-(L22-Pad2)") (class "Default")
      (node (ref "L22") (pin "2") (pinfunction "2_2") (pintype "passive"))
      (node (ref "L27") (pin "1") (pinfunction "1_1") (pintype "passive"))
      (node (ref "L32") (pin "1") (pinfunction "1_1") (pintype "passive"))
    )
    (net (code "106") (name "Net-(L23-Pad2)") (class "Default")
      (node (ref "L23") (pin "2") (pinfunction "2_2") (pintype "passive"))
      (node (ref "L28") (pin "1") (pinfunction "1_1") (pintype "passive"))
      (node (ref "L33") (pin "1") (pinfunction "1_1") (pintype "passive"))
    )
    (net (code "107") (name "Net-(L24-Pad2)") (class "Default")
      (node (ref "L24") (pin "2") (pinfunction "2_2") (pintype "passive"))
      (node (ref "L29") (pin "1") (pinfunction "1_1") (pintype "passive"))
      (node (ref "L34") (pin "1") (pinfunction "1_1") (pintype "passive"))
    )
    (net (code "108") (name "Net-(L25-Pad2)") (class "Default")
      (node (ref "L25") (pin "2") (pinfunction "2_2") (pintype "passive"))
      (node (ref "L30") (pin "1") (pinfunction "1_1") (pintype "passive"))
      (node (ref "L35") (pin "1") (pinfunction "1_1") (pintype "passive"))
    )
    (net (code "109") (name "Net-(L26-Pad2)") (class "Default")
      (node (ref "L26") (pin "2") (pinfunction "2_2") (pintype "passive"))
      (node (ref "L31") (pin "1") (pinfunction "1_1") (pintype "passive"))
      (node (ref "L36") (pin "1") (pinfunction "1_1") (pintype "passive"))
    )
    (net (code "110") (name "Net-(RFCON7-SIGNAL)") (class "Default")
      (node (ref "R41") (pin "1") (pinfunction "1_1") (pintype "passive"))
      (node (ref "RFCON7") (pin "P$3") (pinfunction "SIGNAL_P$3") (pintype "bidirectional"))
    )
    (net (code "111") (name "Net-(RFCON8-SIGNAL)") (class "Default")
      (node (ref "R42") (pin "1") (pinfunction "1_1") (pintype "passive"))
      (node (ref "RFCON8") (pin "P$3") (pinfunction "SIGNAL_P$3") (pintype "bidirectional"))
    )
    (net (code "112") (name "Net-(RFCON9-SIGNAL)") (class "Default")
      (node (ref "R43") (pin "1") (pinfunction "1_1") (pintype "passive"))
      (node (ref "RFCON9") (pin "P$3") (pinfunction "SIGNAL_P$3") (pintype "bidirectional"))
    )
    (net (code "113") (name "Net-(RFCON10-SIGNAL)") (class "Default")
      (node (ref "R44") (pin "1") (pinfunction "1_1") (pintype "passive"))
      (node (ref "RFCON10") (pin "P$3") (pinfunction "SIGNAL_P$3") (pintype "bidirectional"))
    )
    (net (code "114") (name "Net-(RFCON11-SIGNAL)") (class "Default")
      (node (ref "R45") (pin "1") (pinfunction "1_1") (pintype "passive"))
      (node (ref "RFCON11") (pin "P$3") (pinfunction "SIGNAL_P$3") (pintype "bidirectional"))
    )
    (net (code "115") (name "Net-(U9-CLK)") (class "Default")
      (node (ref "R22") (pin "2") (pinfunction "2_2") (pintype "passive"))
      (node (ref "U9") (pin "3") (pinfunction "CLK_3") (pintype "output"))
    )
    (net (code "116") (name "Net-(U11A-Y)") (class "Default")
      (node (ref "R41") (pin "2") (pinfunction "2_2") (pintype "passive"))
      (node (ref "U11") (pin "4") (pinfunction "Y_4") (pintype "output"))
    )
    (net (code "117") (name "Net-(U12A-Y)") (class "Default")
      (node (ref "R42") (pin "2") (pinfunction "2_2") (pintype "passive"))
      (node (ref "U12") (pin "4") (pinfunction "Y_4") (pintype "output"))
    )
    (net (code "118") (name "Net-(U13A-Y)") (class "Default")
      (node (ref "R43") (pin "2") (pinfunction "2_2") (pintype "passive"))
      (node (ref "U13") (pin "4") (pinfunction "Y_4") (pintype "output"))
    )
    (net (code "119") (name "Net-(U14A-Y)") (class "Default")
      (node (ref "R44") (pin "2") (pinfunction "2_2") (pintype "passive"))
      (node (ref "U14") (pin "4") (pinfunction "Y_4") (pintype "output"))
    )
    (net (code "120") (name "Net-(U15A-Y)") (class "Default")
      (node (ref "R45") (pin "2") (pinfunction "2_2") (pintype "passive"))
      (node (ref "U15") (pin "4") (pinfunction "Y_4") (pintype "output"))
    )
    (net (code "121") (name "Net-(U18-FB)") (class "Default")
      (node (ref "R52") (pin "1") (pinfunction "1_1") (pintype "passive"))
      (node (ref "R53") (pin "2") (pinfunction "2_2") (pintype "passive"))
      (node (ref "U18") (pin "4") (pinfunction "FB_4") (pintype "bidirectional"))
    )
    (net (code "122") (name "Net-(U18-SW)") (class "Default")
      (node (ref "L37") (pin "1") (pinfunction "1_1") (pintype "passive"))
      (node (ref "U18") (pin "1") (pinfunction "SW_1") (pintype "bidirectional"))
    )
    (net (code "123") (name "Net-(U19-RT)") (class "Default")
      (node (ref "R51") (pin "2") (pinfunction "2_2") (pintype "passive"))
      (node (ref "U19") (pin "17") (pinfunction "RT_17") (pintype "bidirectional"))
    )
    (net (code "124") (name "OCXO_CLK") (class "Default")
      (node (ref "R20") (pin "2") (pinfunction "2_2") (pintype "passive"))
      (node (ref "U2") (pin "2") (pinfunction "A_2") (pintype "input"))
      (node (ref "U8") (pin "1") (pinfunction "CLK_1") (pintype "output"))
    )
    (net (code "125") (name "OCXO_CLK_BUF") (class "Default")
      (node (ref "U1") (pin "A8") (pinfunction "PF12_A8") (pintype "bidirectional"))
      (node (ref "U2") (pin "4") (pinfunction "Y_4") (pintype "output"))
    )
    (net (code "126") (name "OCXO_EN") (class "Default")
      (node (ref "R48") (pin "2") (pinfunction "2_2") (pintype "passive"))
      (node (ref "U1") (pin "B3") (pinfunction "PE11_B3") (pintype "bidirectional"))
      (node (ref "U17") (pin "5") (pinfunction "EN_5") (pintype "bidirectional"))
    )
    (net (code "127") (name "OCXO_VCONT") (class "Default")
      (node (ref "C29") (pin "1") (pinfunction "C1_1") (pintype "passive"))
      (node (ref "C32") (pin "1") (pinfunction "C1_1") (pintype "passive"))
      (node (ref "R13") (pin "2") (pinfunction "2_2") (pintype "passive"))
      (node (ref "U7") (pin "1") (pinfunction "OUT_1") (pintype "output"))
      (node (ref "U7") (pin "4") (pinfunction "-IN_4") (pintype "input"))
      (node (ref "U8") (pin "3") (pinfunction "VCONT_3") (pintype "power_in"))
    )
    (net (code "128") (name "PLL_M3") (class "Default")
      (node (ref "R14") (pin "2") (pinfunction "2_2") (pintype "passive"))
      (node (ref "U10") (pin "36") (pinfunction "M3_36") (pintype "bidirectional"))
    )
    (net (code "129") (name "PLL_M4") (class "Default")
      (node (ref "R15") (pin "1") (pinfunction "1_1") (pintype "passive"))
      (node (ref "U10") (pin "37") (pinfunction "M4_37") (pintype "bidirectional"))
    )
    (net (code "130") (name "PLL_M5") (class "Default")
      (node (ref "R16") (pin "2") (pinfunction "2_2") (pintype "passive"))
      (node (ref "U10") (pin "1") (pinfunction "M5/SDO_1") (pintype "bidirectional"))
    )
    (net (code "131") (name "PLL_M6") (class "Default")
      (node (ref "R17") (pin "2") (pinfunction "2_2") (pintype "passive"))
      (node (ref "U10") (pin "5") (pinfunction "M6/~{CS}_5") (pintype "bidirectional"))
    )
    (net (code "132") (name "PLL_REFA") (class "Default")
      (node (ref "R20") (pin "1") (pinfunction "1_1") (pintype "passive"))
      (node (ref "R21") (pin "2") (pinfunction "2_2") (pintype "passive"))
      (node (ref "U10") (pin "47") (pinfunction "REFA_47") (pintype "bidirectional"))
    )
    (net (code "133") (name "PLL_REFB") (class "Default")
      (node (ref "R18") (pin "1") (pinfunction "1_1") (pintype "passive"))
      (node (ref "R19") (pin "2") (pinfunction "2_2") (pintype "passive"))
      (node (ref "U10") (pin "38") (pinfunction "REFB_38") (pintype "bidirectional"))
    )
    (net (code "134") (name "VIN") (class "Default")
      (node (ref "C117") (pin "1") (pinfunction "C1_1") (pintype "passive"))
      (node (ref "C92") (pin "1") (pinfunction "C1_1") (pintype "passive"))
      (node (ref "C94") (pin "1") (pinfunction "C1_1") (pintype "passive"))
      (node (ref "C95") (pin "1") (pinfunction "C1_1") (pintype "passive"))
      (node (ref "D11") (pin "C") (pinfunction "C_C") (pintype "passive"))
      (node (ref "F1") (pin "1") (pinfunction "1_1") (pintype "passive"))
      (node (ref "R46") (pin "2") (pinfunction "2_2") (pintype "passive"))
      (node (ref "R57") (pin "2") (pinfunction "2_2") (pintype "passive"))
      (node (ref "U19") (pin "11") (pinfunction "VIN_11") (pintype "bidirectional"))
      (node (ref "U19") (pin "6") (pinfunction "VIN_6") (pintype "bidirectional"))
    )
    (net (code "135") (name "VIN_VSENSE") (class "Default")
      (node (ref "C115") (pin "1") (pinfunction "C1_1") (pintype "passive"))
      (node (ref "R57") (pin "1") (pinfunction "1_1") (pintype "passive"))
      (node (ref "R58") (pin "2") (pinfunction "2_2") (pintype "passive"))
      (node (ref "U1") (pin "J11") (pinfunction "PD4_J11") (pintype "bidirectional"))
    )
    (net (code "136") (name "unconnected-(J1-PadDT)") (class "Default")
      (node (ref "J1") (pin "DT") (pinfunction "DT_DT") (pintype "bidirectional"))
    )
    (net (code "137") (name "unconnected-(TC1F-S-Pad5)") (class "Default")
      (node (ref "TC1") (pin "5") (pinfunction "S_5") (pintype "passive"))
    )
    (net (code "138") (name "unconnected-(U1-PA3-PadD1)") (class "Default")
      (node (ref "U1") (pin "D1") (pinfunction "PA3_D1") (pintype "bidirectional"))
    )
    (net (code "139") (name "unconnected-(U1-PA4-PadE3)") (class "Default")
      (node (ref "U1") (pin "E3") (pinfunction "PA4_E3") (pintype "bidirectional"))
    )
    (net (code "140") (name "unconnected-(U1-PA5-PadE2)") (class "Default")
      (node (ref "U1") (pin "E2") (pinfunction "PA5_E2") (pintype "bidirectional"))
    )
    (net (code "141") (name "unconnected-(U1-PA7-PadH4)") (class "Default")
      (node (ref "U1") (pin "H4") (pinfunction "PA7_H4") (pintype "bidirectional"))
    )
    (net (code "142") (name "unconnected-(U1-PA8-PadH5)") (class "Default")
      (node (ref "U1") (pin "H5") (pinfunction "PA8_H5") (pintype "bidirectional"))
    )
    (net (code "143") (name "unconnected-(U1-PA9-PadJ5)") (class "Default")
      (node (ref "U1") (pin "J5") (pinfunction "PA9_J5") (pintype "bidirectional"))
    )
    (net (code "144") (name "unconnected-(U1-PA10-PadJ6)") (class "Default")
      (node (ref "U1") (pin "J6") (pinfunction "PA10_J6") (pintype "bidirectional"))
    )
    (net (code "145") (name "unconnected-(U1-PA11-PadK5)") (class "Default")
      (node (ref "U1") (pin "K5") (pinfunction "PA11_K5") (pintype "bidirectional"))
    )
    (net (code "146") (name "unconnected-(U1-PA12-PadJ4)") (class "Default")
      (node (ref "U1") (pin "J4") (pinfunction "PA12_J4") (pintype "bidirectional"))
    )
    (net (code "147") (name "unconnected-(U1-PA13-PadK3)") (class "Default")
      (node (ref "U1") (pin "K3") (pinfunction "PA13_K3") (pintype "bidirectional"))
    )
    (net (code "148") (name "unconnected-(U1-PA14-PadL3)") (class "Default")
      (node (ref "U1") (pin "L3") (pinfunction "PA14_L3") (pintype "bidirectional"))
    )
    (net (code "149") (name "unconnected-(U1-PA15-PadB1)") (class "Default")
      (node (ref "U1") (pin "B1") (pinfunction "PA15_B1") (pintype "bidirectional"))
    )
    (net (code "150") (name "unconnected-(U1-PB0-PadE4)") (class "Default")
      (node (ref "U1") (pin "E4") (pinfunction "PB0_E4") (pintype "bidirectional"))
    )
    (net (code "151") (name "unconnected-(U1-PB1-PadF1)") (class "Default")
      (node (ref "U1") (pin "F1") (pinfunction "PB1_F1") (pintype "bidirectional"))
    )
    (net (code "152") (name "unconnected-(U1-PB2-PadF2)") (class "Default")
      (node (ref "U1") (pin "F2") (pinfunction "PB2_F2") (pintype "bidirectional"))
    )
    (net (code "153") (name "unconnected-(U1-PB3-PadF3)") (class "Default")
      (node (ref "U1") (pin "F3") (pinfunction "PB3_F3") (pintype "bidirectional"))
    )
    (net (code "154") (name "unconnected-(U1-PB4-PadF4)") (class "Default")
      (node (ref "U1") (pin "F4") (pinfunction "PB4_F4") (pintype "bidirectional"))
    )
    (net (code "155") (name "unconnected-(U1-PB5-PadG1)") (class "Default")
      (node (ref "U1") (pin "G1") (pinfunction "PB5_G1") (pintype "bidirectional"))
    )
    (net (code "156") (name "unconnected-(U1-PB6-PadG2)") (class "Default")
      (node (ref "U1") (pin "G2") (pinfunction "PB6_G2") (pintype "bidirectional"))
    )
    (net (code "157") (name "unconnected-(U1-PB7-PadK1)") (class "Default")
      (node (ref "U1") (pin "K1") (pinfunction "PB7_K1") (pintype "bidirectional"))
    )
    (net (code "158") (name "unconnected-(U1-PB8-PadL1)") (class "Default")
      (node (ref "U1") (pin "L1") (pinfunction "PB8_L1") (pintype "bidirectional"))
    )
    (net (code "159") (name "unconnected-(U1-PB9-PadJ7)") (class "Default")
      (node (ref "U1") (pin "J7") (pinfunction "PB9_J7") (pintype "bidirectional"))
    )
    (net (code "160") (name "unconnected-(U1-PB10-PadJ8)") (class "Default")
      (node (ref "U1") (pin "J8") (pinfunction "PB10_J8") (pintype "bidirectional"))
    )
    (net (code "161") (name "unconnected-(U1-PB14-PadL9)") (class "Default")
      (node (ref "U1") (pin "L9") (pinfunction "PB14_L9") (pintype "bidirectional"))
    )
    (net (code "162") (name "unconnected-(U1-PB15-PadD3)") (class "Default")
      (node (ref "U1") (pin "D3") (pinfunction "PB15_D3") (pintype "bidirectional"))
    )
    (net (code "163") (name "unconnected-(U1-PC0-PadH1)") (class "Default")
      (node (ref "U1") (pin "H1") (pinfunction "PC0_H1") (pintype "bidirectional"))
    )
    (net (code "164") (name "unconnected-(U1-PC1-PadJ1)") (class "Default")
      (node (ref "U1") (pin "J1") (pinfunction "PC1_J1") (pintype "bidirectional"))
    )
    (net (code "165") (name "unconnected-(U1-PC2-PadH2)") (class "Default")
      (node (ref "U1") (pin "H2") (pinfunction "PC2_H2") (pintype "bidirectional"))
    )
    (net (code "166") (name "unconnected-(U1-PC3-PadJ2)") (class "Default")
      (node (ref "U1") (pin "J2") (pinfunction "PC3_J2") (pintype "bidirectional"))
    )
    (net (code "167") (name "unconnected-(U1-PC4-PadK2)") (class "Default")
      (node (ref "U1") (pin "K2") (pinfunction "PC4_K2") (pintype "bidirectional"))
    )
    (net (code "168") (name "unconnected-(U1-PC5-PadL2)") (class "Default")
      (node (ref "U1") (pin "L2") (pinfunction "PC5_L2") (pintype "bidirectional"))
    )
    (net (code "169") (name "unconnected-(U1-PC6-PadG10)") (class "Default")
      (node (ref "U1") (pin "G10") (pinfunction "PC6_G10") (pintype "bidirectional"))
    )
    (net (code "170") (name "unconnected-(U1-PC7-PadG11)") (class "Default")
      (node (ref "U1") (pin "G11") (pinfunction "PC7_G11") (pintype "bidirectional"))
    )
    (net (code "171") (name "unconnected-(U1-PC8-PadD10)") (class "Default")
      (node (ref "U1") (pin "D10") (pinfunction "PC8_D10") (pintype "bidirectional"))
    )
    (net (code "172") (name "unconnected-(U1-PC9-PadD11)") (class "Default")
      (node (ref "U1") (pin "D11") (pinfunction "PC9_D11") (pintype "bidirectional"))
    )
    (net (code "173") (name "unconnected-(U1-PC10-PadC10)") (class "Default")
      (node (ref "U1") (pin "C10") (pinfunction "PC10_C10") (pintype "bidirectional"))
    )
    (net (code "174") (name "unconnected-(U1-PC11-PadC11)") (class "Default")
      (node (ref "U1") (pin "C11") (pinfunction "PC11_C11") (pintype "bidirectional"))
    )
    (net (code "175") (name "unconnected-(U1-PD0-PadL11)") (class "Default")
      (node (ref "U1") (pin "L11") (pinfunction "PD0_L11") (pintype "bidirectional"))
    )
    (net (code "176") (name "unconnected-(U1-PD1-PadK11)") (class "Default")
      (node (ref "U1") (pin "K11") (pinfunction "PD1_K11") (pintype "bidirectional"))
    )
    (net (code "177") (name "unconnected-(U1-PD2-PadJ9)") (class "Default")
      (node (ref "U1") (pin "J9") (pinfunction "PD2_J9") (pintype "bidirectional"))
    )
    (net (code "178") (name "unconnected-(U1-PD3-PadJ10)") (class "Default")
      (node (ref "U1") (pin "J10") (pinfunction "PD3_J10") (pintype "bidirectional"))
    )
    (net (code "179") (name "unconnected-(U1-PD5-PadH9)") (class "Default")
      (node (ref "U1") (pin "H9") (pinfunction "PD5_H9") (pintype "bidirectional"))
    )
    (net (code "180") (name "unconnected-(U1-PD7-PadH11)") (class "Default")
      (node (ref "U1") (pin "H11") (pinfunction "PD7_H11") (pintype "bidirectional"))
    )
    (net (code "181") (name "unconnected-(U1-PD8-PadH8)") (class "Default")
      (node (ref "U1") (pin "H8") (pinfunction "PD8_H8") (pintype "bidirectional"))
    )
    (net (code "182") (name "unconnected-(U1-PD9-PadD6)") (class "Default")
      (node (ref "U1") (pin "D6") (pinfunction "PD9_D6") (pintype "bidirectional"))
    )
    (net (code "183") (name "unconnected-(U1-PD11-PadB5)") (class "Default")
      (node (ref "U1") (pin "B5") (pinfunction "PD11_B5") (pintype "bidirectional"))
    )
    (net (code "184") (name "unconnected-(U1-PD12-PadC5)") (class "Default")
      (node (ref "U1") (pin "C5") (pinfunction "PD12_C5") (pintype "bidirectional"))
    )
    (net (code "185") (name "unconnected-(U1-PD13-PadC4)") (class "Default")
      (node (ref "U1") (pin "C4") (pinfunction "PD13_C4") (pintype "bidirectional"))
    )
    (net (code "186") (name "unconnected-(U1-PD14-PadH3)") (class "Default")
      (node (ref "U1") (pin "H3") (pinfunction "PD14_H3") (pintype "bidirectional"))
    )
    (net (code "187") (name "unconnected-(U1-PD15-PadJ3)") (class "Default")
      (node (ref "U1") (pin "J3") (pinfunction "PD15_J3") (pintype "bidirectional"))
    )
    (net (code "188") (name "unconnected-(U1-PE0-PadE9)") (class "Default")
      (node (ref "U1") (pin "E9") (pinfunction "PE0_E9") (pintype "bidirectional"))
    )
    (net (code "189") (name "unconnected-(U1-PE1-PadE10)") (class "Default")
      (node (ref "U1") (pin "E10") (pinfunction "PE1_E10") (pintype "bidirectional"))
    )
    (net (code "190") (name "unconnected-(U1-PE2-PadF10)") (class "Default")
      (node (ref "U1") (pin "F10") (pinfunction "PE2_F10") (pintype "bidirectional"))
    )
    (net (code "191") (name "unconnected-(U1-PE3-PadE11)") (class "Default")
      (node (ref "U1") (pin "E11") (pinfunction "PE3_E11") (pintype "bidirectional"))
    )
    (net (code "192") (name "unconnected-(U1-PE4-PadA9)") (class "Default")
      (node (ref "U1") (pin "A9") (pinfunction "PE4_A9") (pintype "bidirectional"))
    )
    (net (code "193") (name "unconnected-(U1-PE5-PadB9)") (class "Default")
      (node (ref "U1") (pin "B9") (pinfunction "PE5_B9") (pintype "bidirectional"))
    )
    (net (code "194") (name "unconnected-(U1-PE6-PadC9)") (class "Default")
      (node (ref "U1") (pin "C9") (pinfunction "PE6_C9") (pintype "bidirectional"))
    )
    (net (code "195") (name "unconnected-(U1-PE7-PadD9)") (class "Default")
      (node (ref "U1") (pin "D9") (pinfunction "PE7_D9") (pintype "bidirectional"))
    )
    (net (code "196") (name "unconnected-(U1-PE9-PadA4)") (class "Default")
      (node (ref "U1") (pin "A4") (pinfunction "PE9_A4") (pintype "bidirectional"))
    )
    (net (code "197") (name "unconnected-(U1-PE14-PadA2)") (class "Default")
      (node (ref "U1") (pin "A2") (pinfunction "PE14_A2") (pintype "bidirectional"))
    )
    (net (code "198") (name "unconnected-(U1-PF6-PadB7)") (class "Default")
      (node (ref "U1") (pin "B7") (pinfunction "PF6_B7") (pintype "bidirectional"))
    )
    (net (code "199") (name "unconnected-(U1-PF8-PadB6)") (class "Default")
      (node (ref "U1") (pin "B6") (pinfunction "PF8_B6") (pintype "bidirectional"))
    )
    (net (code "200") (name "unconnected-(U1-PF9-PadC6)") (class "Default")
      (node (ref "U1") (pin "C6") (pinfunction "PF9_C6") (pintype "bidirectional"))
    )
    (net (code "201") (name "unconnected-(U1-PF10-PadA10)") (class "Default")
      (node (ref "U1") (pin "A10") (pinfunction "PF10_A10") (pintype "bidirectional"))
    )
    (net (code "202") (name "unconnected-(U1-PF11-PadA11)") (class "Default")
      (node (ref "U1") (pin "A11") (pinfunction "PF11_A11") (pintype "bidirectional"))
    )
    (net (code "203") (name "unconnected-(U1-VBUS-PadB8)") (class "Default")
      (node (ref "U1") (pin "B8") (pinfunction "VBUS_B8") (pintype "bidirectional"))
    )
    (net (code "204") (name "unconnected-(U4-EXTINT-Pad5)") (class "Default")
      (node (ref "U4") (pin "5") (pinfunction "EXTINT_5") (pintype "bidirectional"))
    )
    (net (code "205") (name "unconnected-(U4-LNA_EN-Pad13)") (class "Default")
      (node (ref "U4") (pin "13") (pinfunction "LNA_EN_13") (pintype "bidirectional"))
    )
    (net (code "206") (name "unconnected-(U4-~{SAFEBOOT}-Pad18)") (class "Default")
      (node (ref "U4") (pin "18") (pinfunction "~{SAFEBOOT}_18") (pintype "bidirectional"))
    )
    (net (code "207") (name "unconnected-(U10-M1-Pad33)") (class "Default")
      (node (ref "U10") (pin "33") (pinfunction "M1_33") (pintype "bidirectional"))
    )
    (net (code "208") (name "unconnected-(U10-M2-Pad35)") (class "Default")
      (node (ref "U10") (pin "35") (pinfunction "M2_35") (pintype "bidirectional"))
    )
    (net (code "209") (name "unconnected-(U10-REFAA-Pad46)") (class "Default")
      (node (ref "U10") (pin "46") (pinfunction "REFAA_46") (pintype "bidirectional"))
    )
    (net (code "210") (name "unconnected-(U10-REFBB-Pad39)") (class "Default")
      (node (ref "U10") (pin "39") (pinfunction "REFBB_39") (pintype "bidirectional"))
    )
    (net (code "211") (name "unconnected-(U19-CLKOUT-Pad16)") (class "Default")
      (node (ref "U19") (pin "16") (pinfunction "CLKOUT_16") (pintype "bidirectional"))
    )
    (net (code "212") (name "~{CLK0}") (class "Default")
      (node (ref "L2") (pin "1") (pinfunction "1_1") (pintype "passive"))
      (node (ref "R26") (pin "2") (pinfunction "2_2") (pintype "passive"))
      (node (ref "U10") (pin "12") (pinfunction "~{OUT0A}_12") (pintype "bidirectional"))
    )
    (net (code "213") (name "~{CLK1}") (class "Default")
      (node (ref "L3") (pin "1") (pinfunction "1_1") (pintype "passive"))
      (node (ref "R28") (pin "2") (pinfunction "2_2") (pintype "passive"))
      (node (ref "U10") (pin "15") (pinfunction "~{OUT0B}_15") (pintype "bidirectional"))
    )
    (net (code "214") (name "~{CLK2}") (class "Default")
      (node (ref "L4") (pin "1") (pinfunction "1_1") (pintype "passive"))
      (node (ref "R30") (pin "2") (pinfunction "2_2") (pintype "passive"))
      (node (ref "U10") (pin "18") (pinfunction "~{OUT0C}_18") (pintype "bidirectional"))
    )
    (net (code "215") (name "~{CLK3}") (class "Default")
      (node (ref "L5") (pin "1") (pinfunction "1_1") (pintype "passive"))
      (node (ref "R32") (pin "2") (pinfunction "2_2") (pintype "passive"))
      (node (ref "U10") (pin "23") (pinfunction "~{OUT1B}_23") (pintype "bidirectional"))
    )
    (net (code "216") (name "~{CLK4}") (class "Default")
      (node (ref "L6") (pin "1") (pinfunction "1_1") (pintype "passive"))
      (node (ref "R34") (pin "2") (pinfunction "2_2") (pintype "passive"))
      (node (ref "U10") (pin "26") (pinfunction "~{OUT1A}_26") (pintype "bidirectional"))
    )
    (net (code "217") (name "~{DAC_CS}") (class "Default")
      (node (ref "U1") (pin "B2") (pinfunction "PE13_B2") (pintype "bidirectional"))
      (node (ref "U6") (pin "5") (pinfunction "~{CS}_5") (pintype "bidirectional"))
    )
    (net (code "218") (name "~{GPS_RESET}") (class "Default")
      (node (ref "R9") (pin "1") (pinfunction "1_1") (pintype "passive"))
      (node (ref "U1") (pin "D2") (pinfunction "PA2_D2") (pintype "bidirectional"))
      (node (ref "U4") (pin "9") (pinfunction "~{RESET}_9") (pintype "bidirectional"))
    )
    (net (code "219") (name "~{MCU_RESET}") (class "Default")
      (node (ref "R7") (pin "1") (pinfunction "1_1") (pintype "passive"))
      (node (ref "TC1") (pin "10") (pinfunction "S_10") (pintype "passive"))
      (node (ref "U1") (pin "K6") (pinfunction "~{RESET}_K6") (pintype "bidirectional"))
    )
    (net (code "220") (name "~{PLL_IRQ}") (class "Default")
      (node (ref "R25") (pin "1") (pinfunction "1_1") (pintype "passive"))
      (node (ref "U1") (pin "A5") (pinfunction "PD10_A5") (pintype "bidirectional"))
      (node (ref "U10") (pin "32") (pinfunction "M0_32") (pintype "bidirectional"))
    )
    (net (code "221") (name "~{PLL_RESET}") (class "Default")
      (node (ref "R23") (pin "1") (pinfunction "1_1") (pintype "passive"))
      (node (ref "U1") (pin "A6") (pinfunction "PF7_A6") (pintype "bidirectional"))
      (node (ref "U10") (pin "48") (pinfunction "~{RESET}_48") (pintype "bidirectional"))
    )
  )
)
